# UFBmod_2V1.net
KiCad netlist of a schematic drawn in EAGLE
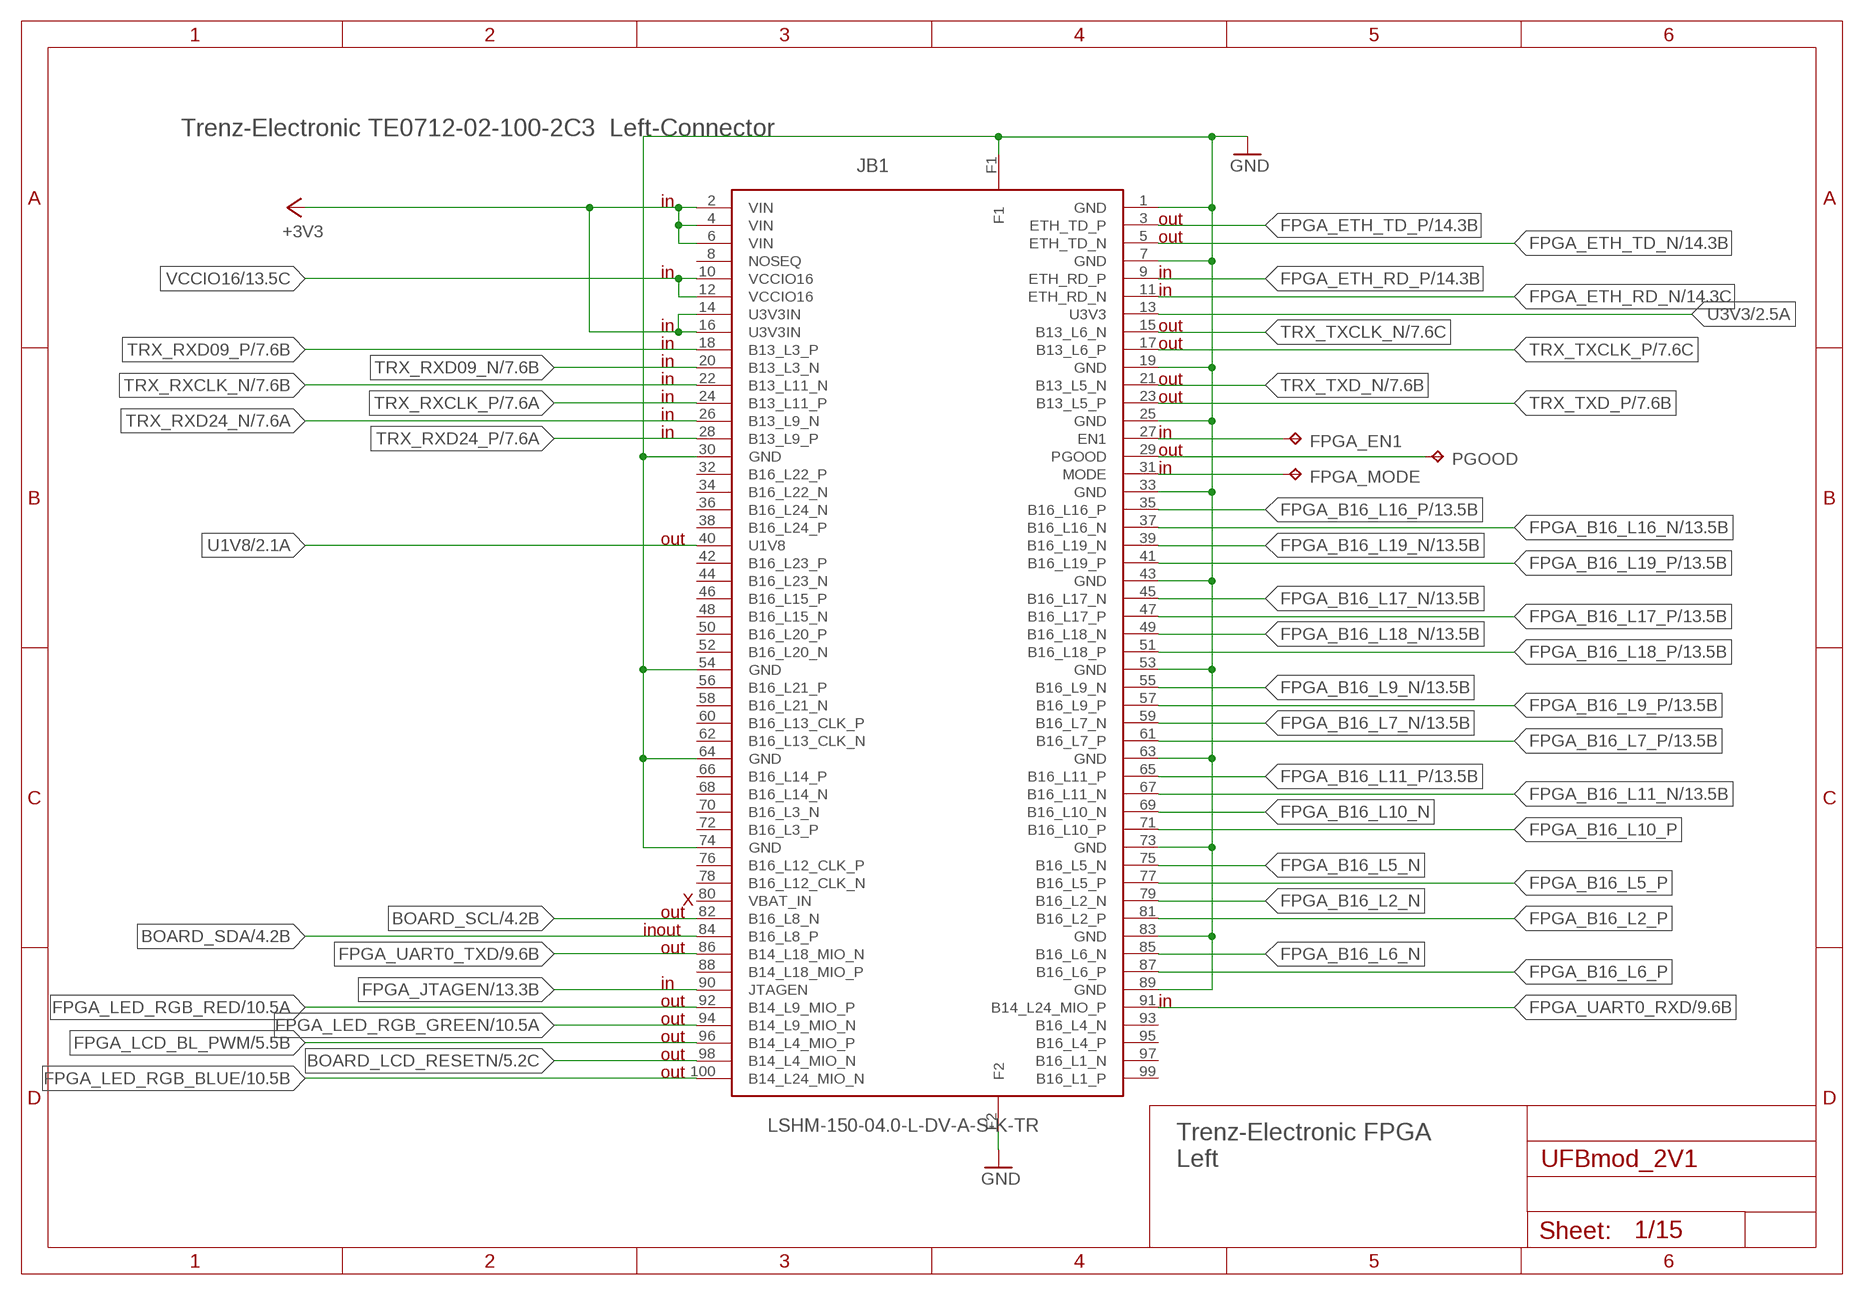
[diagram p0: schematic, sheet 1]
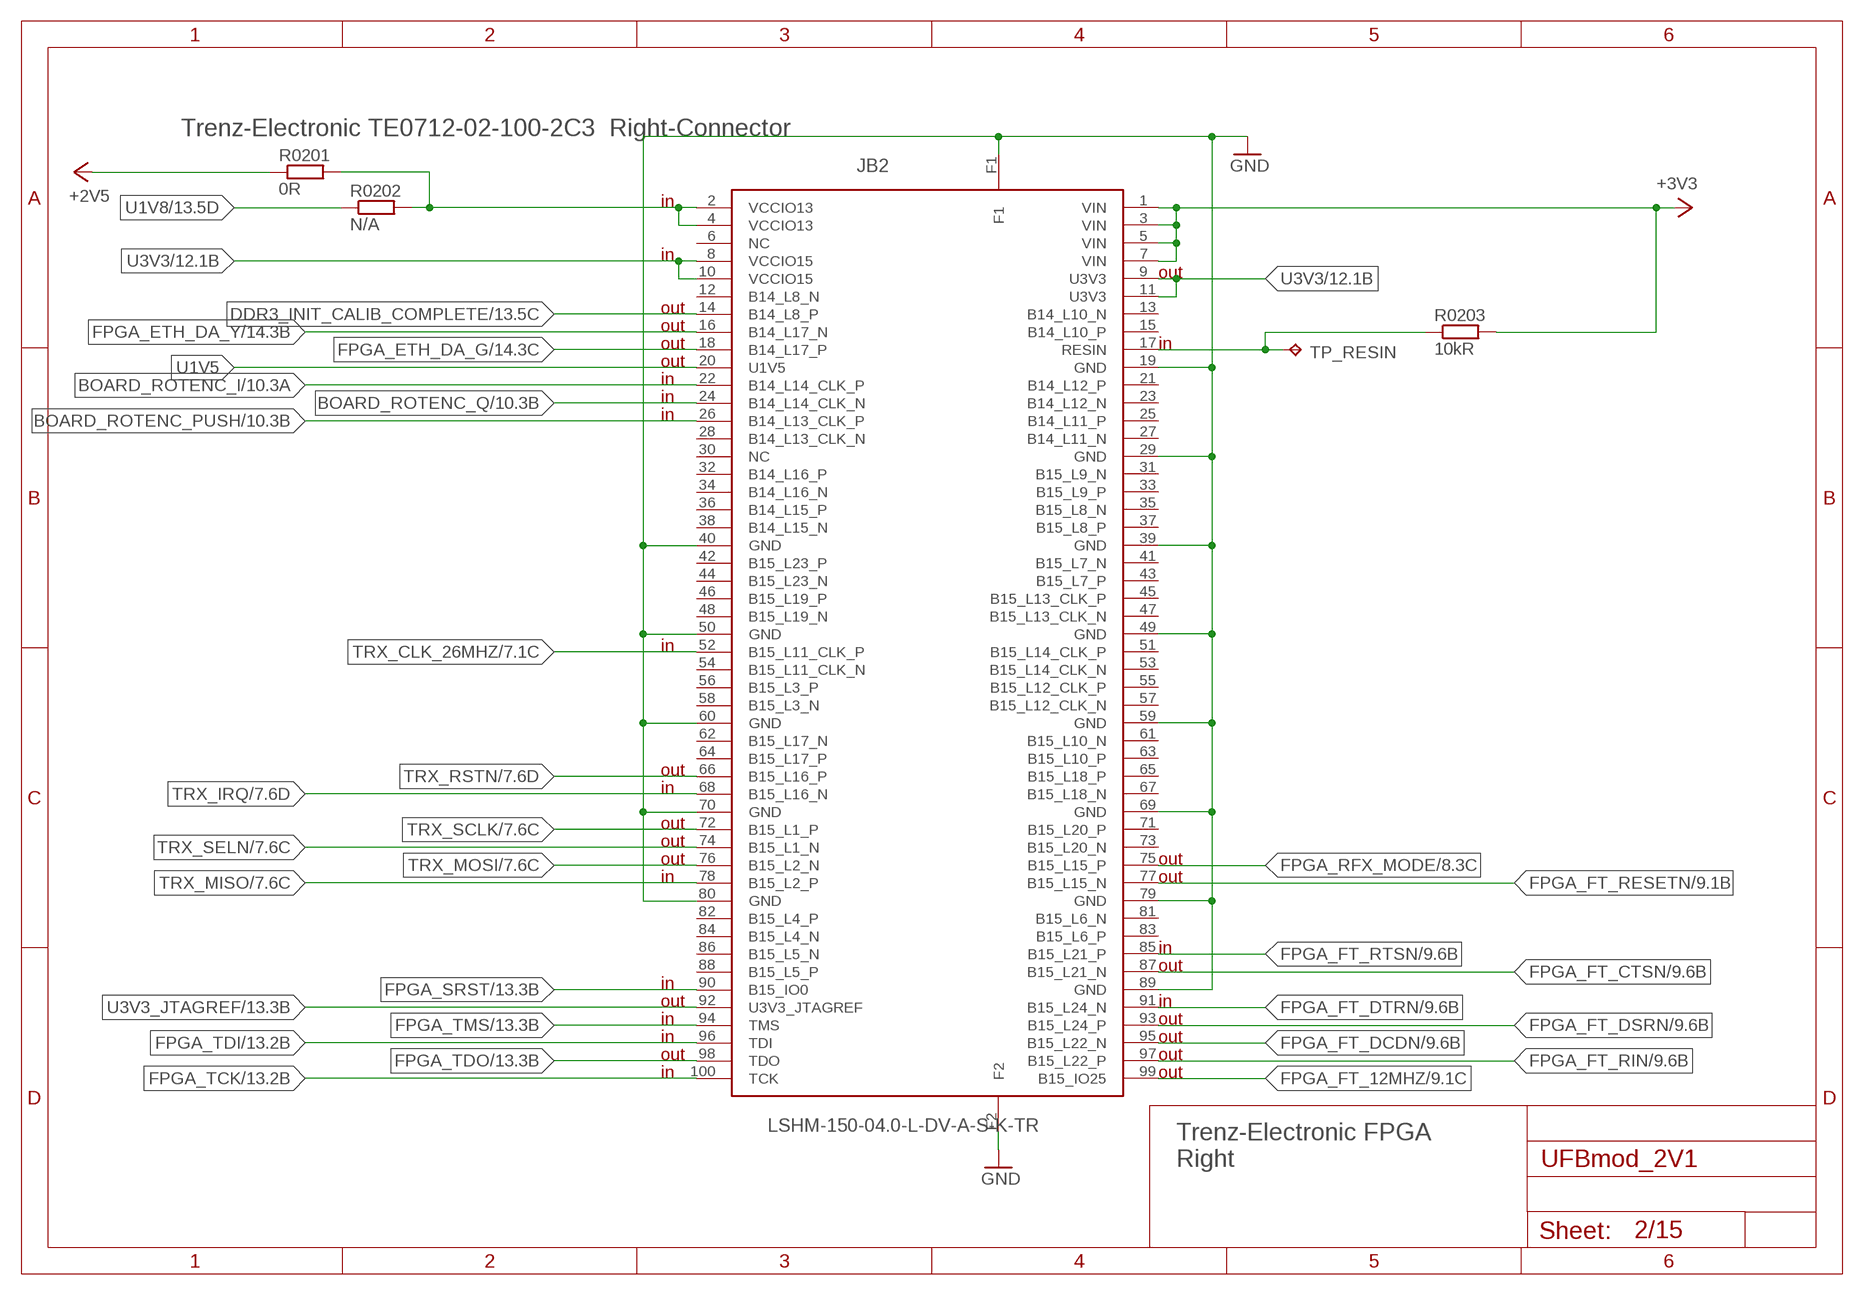
[diagram p1: schematic, sheet 2]
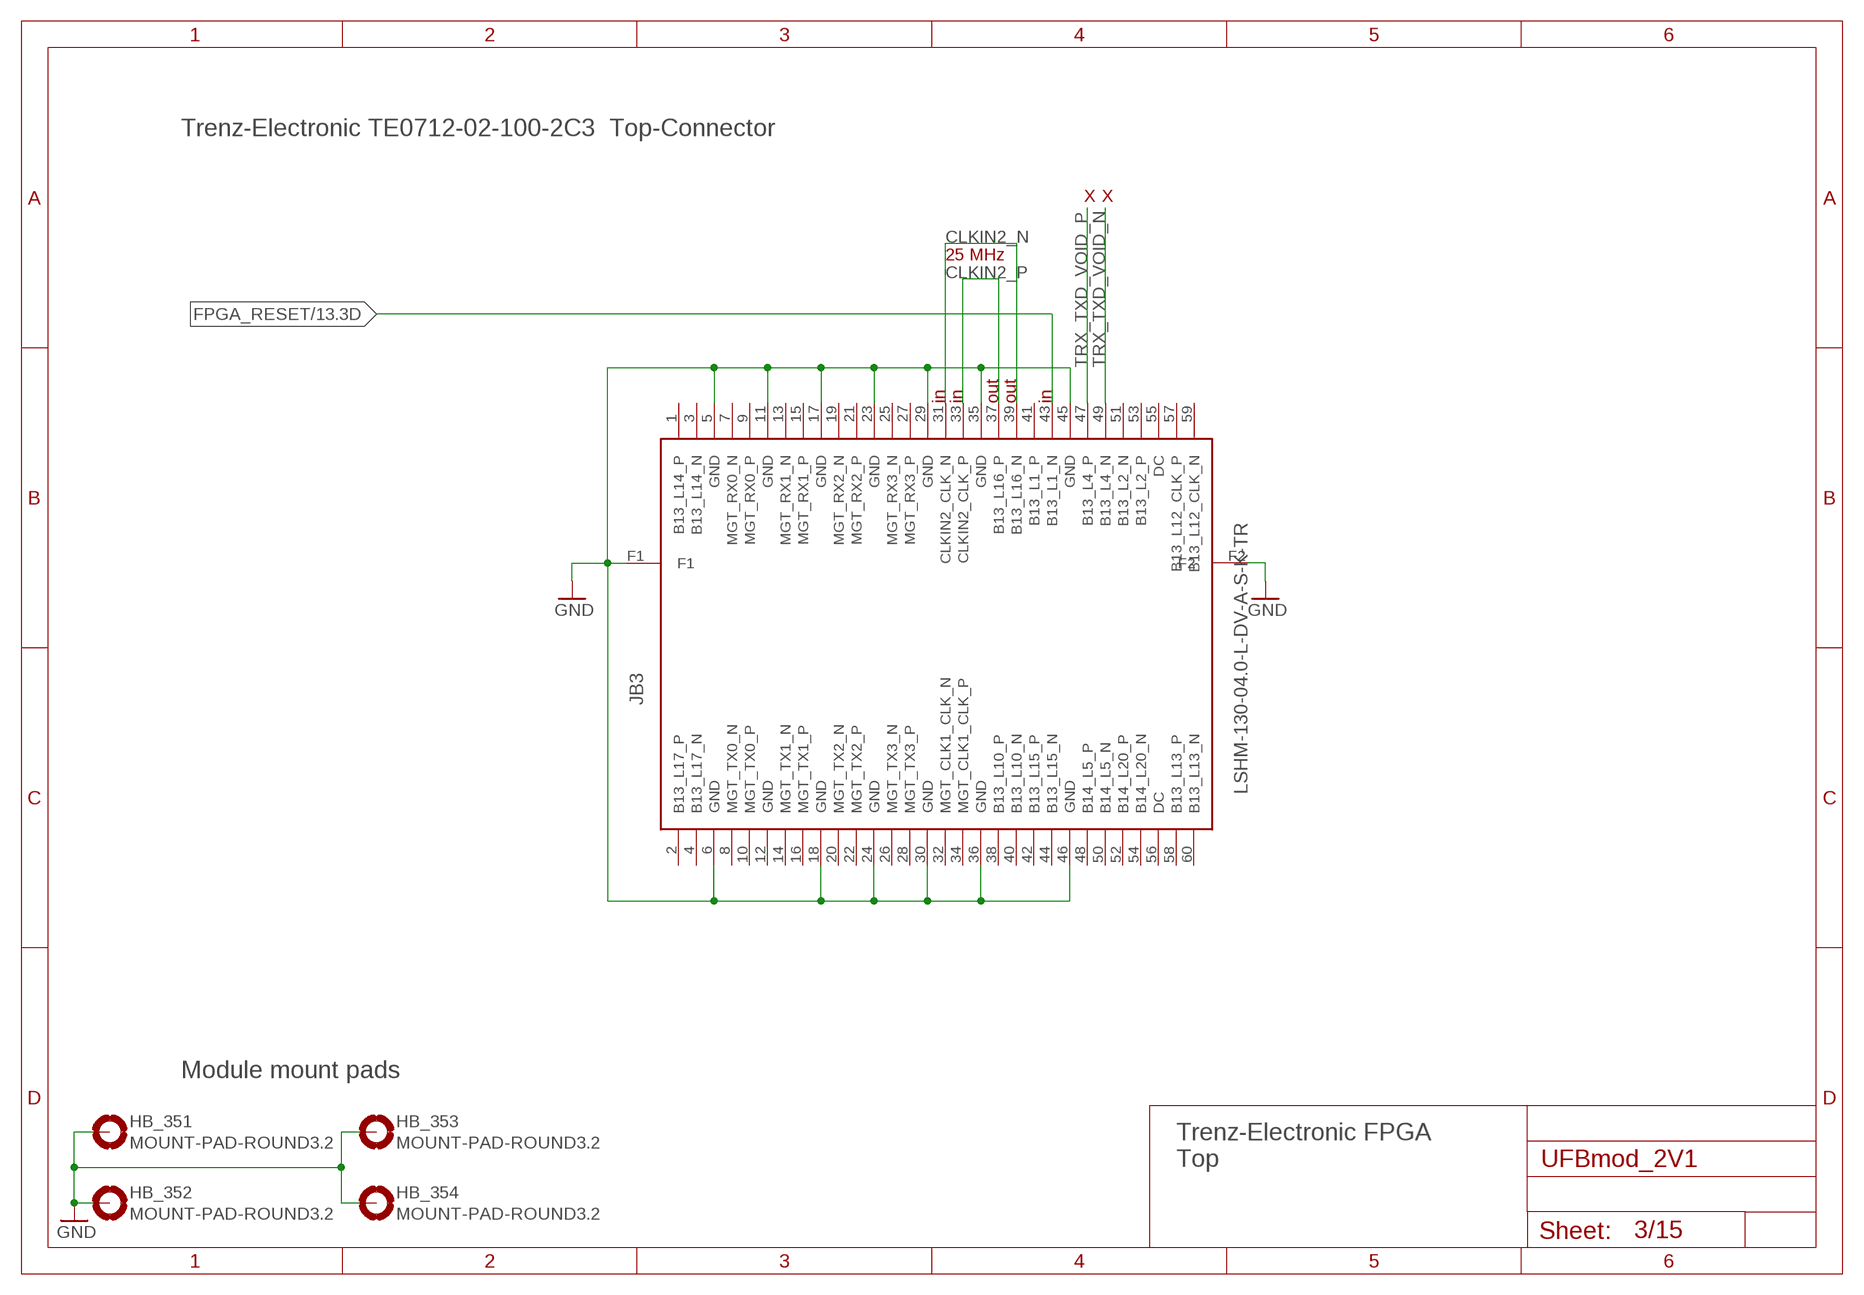
[diagram p2: schematic, sheet 3]
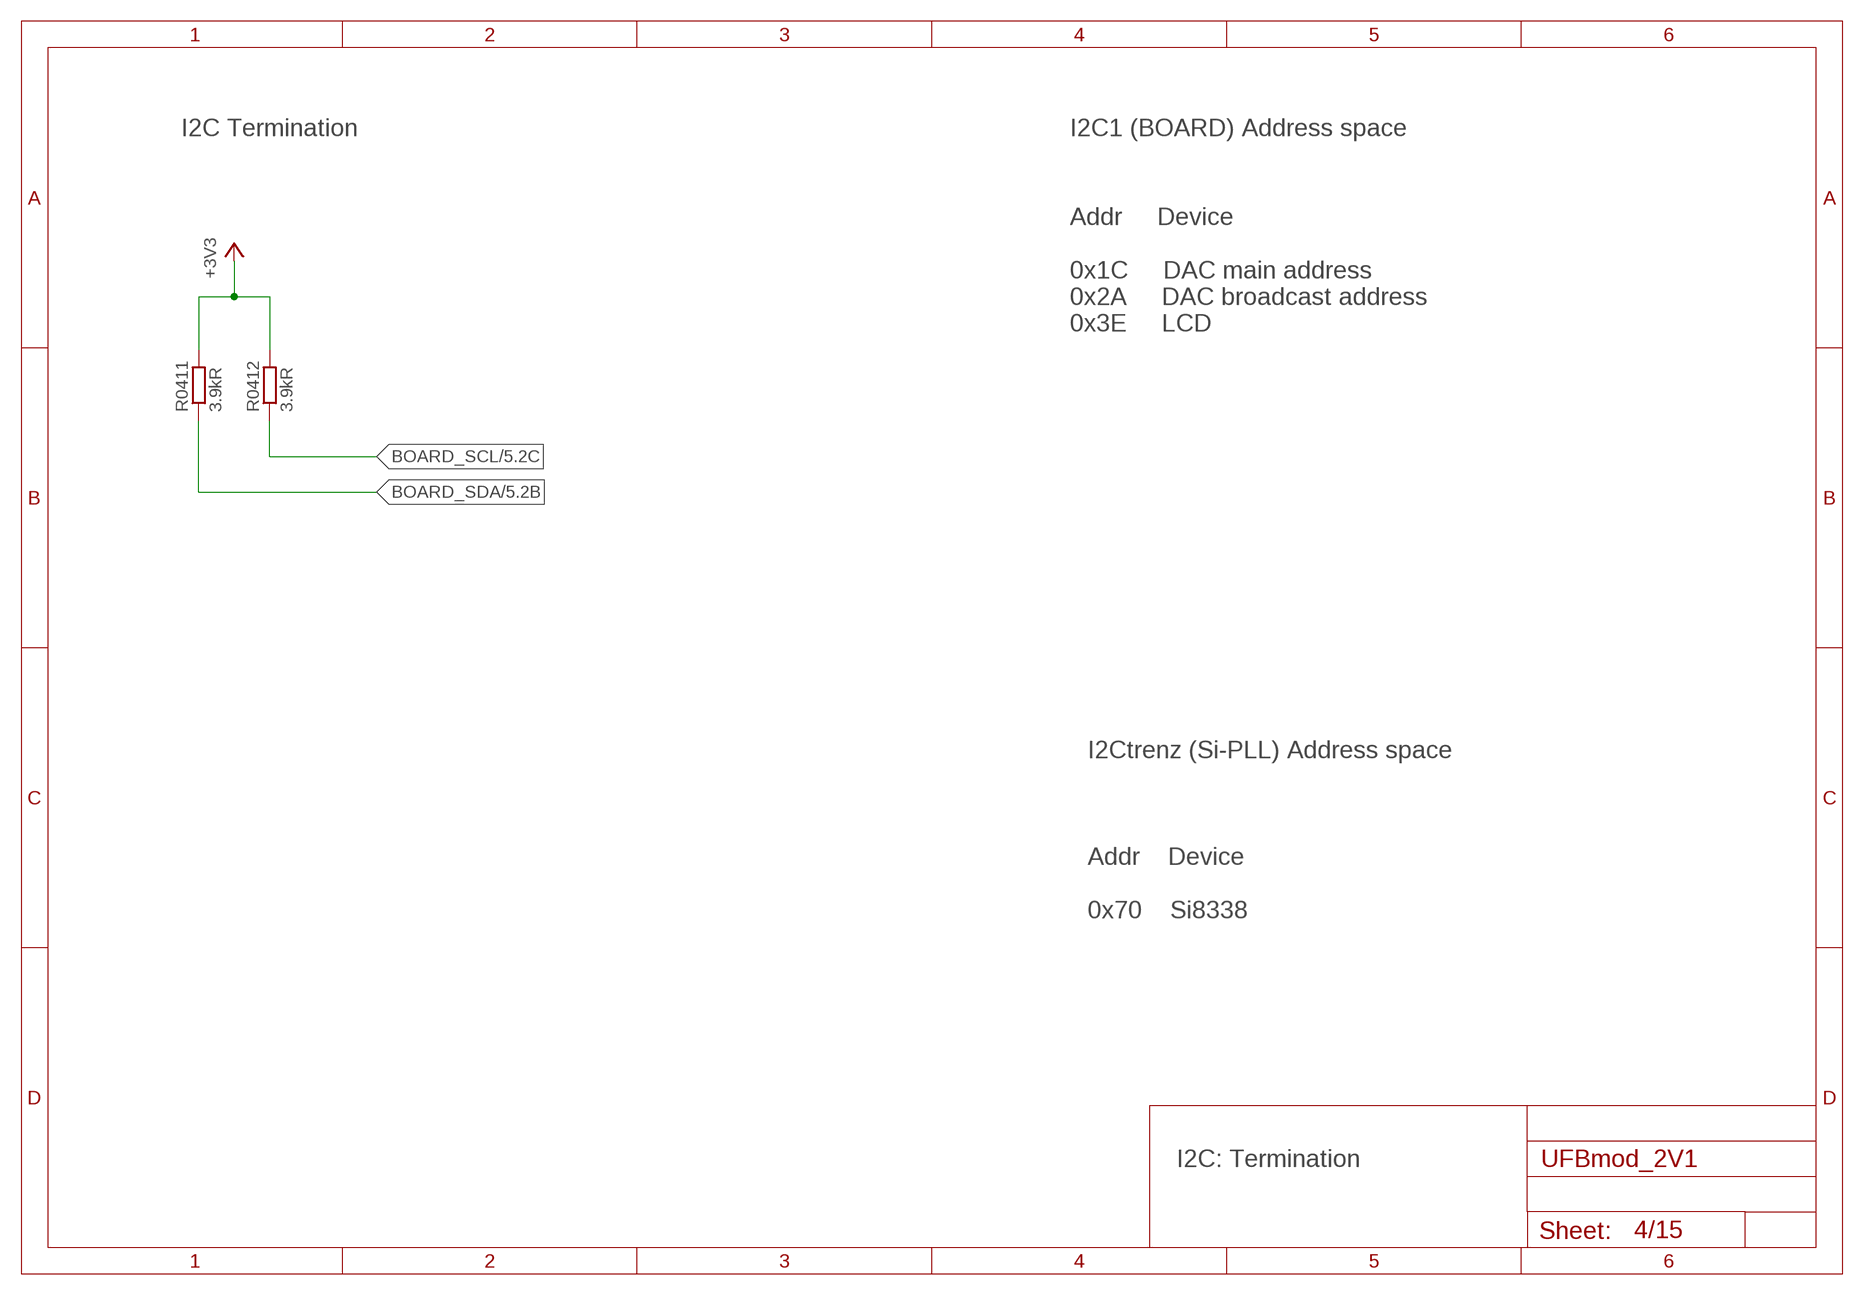
[diagram p3: schematic, sheet 4]
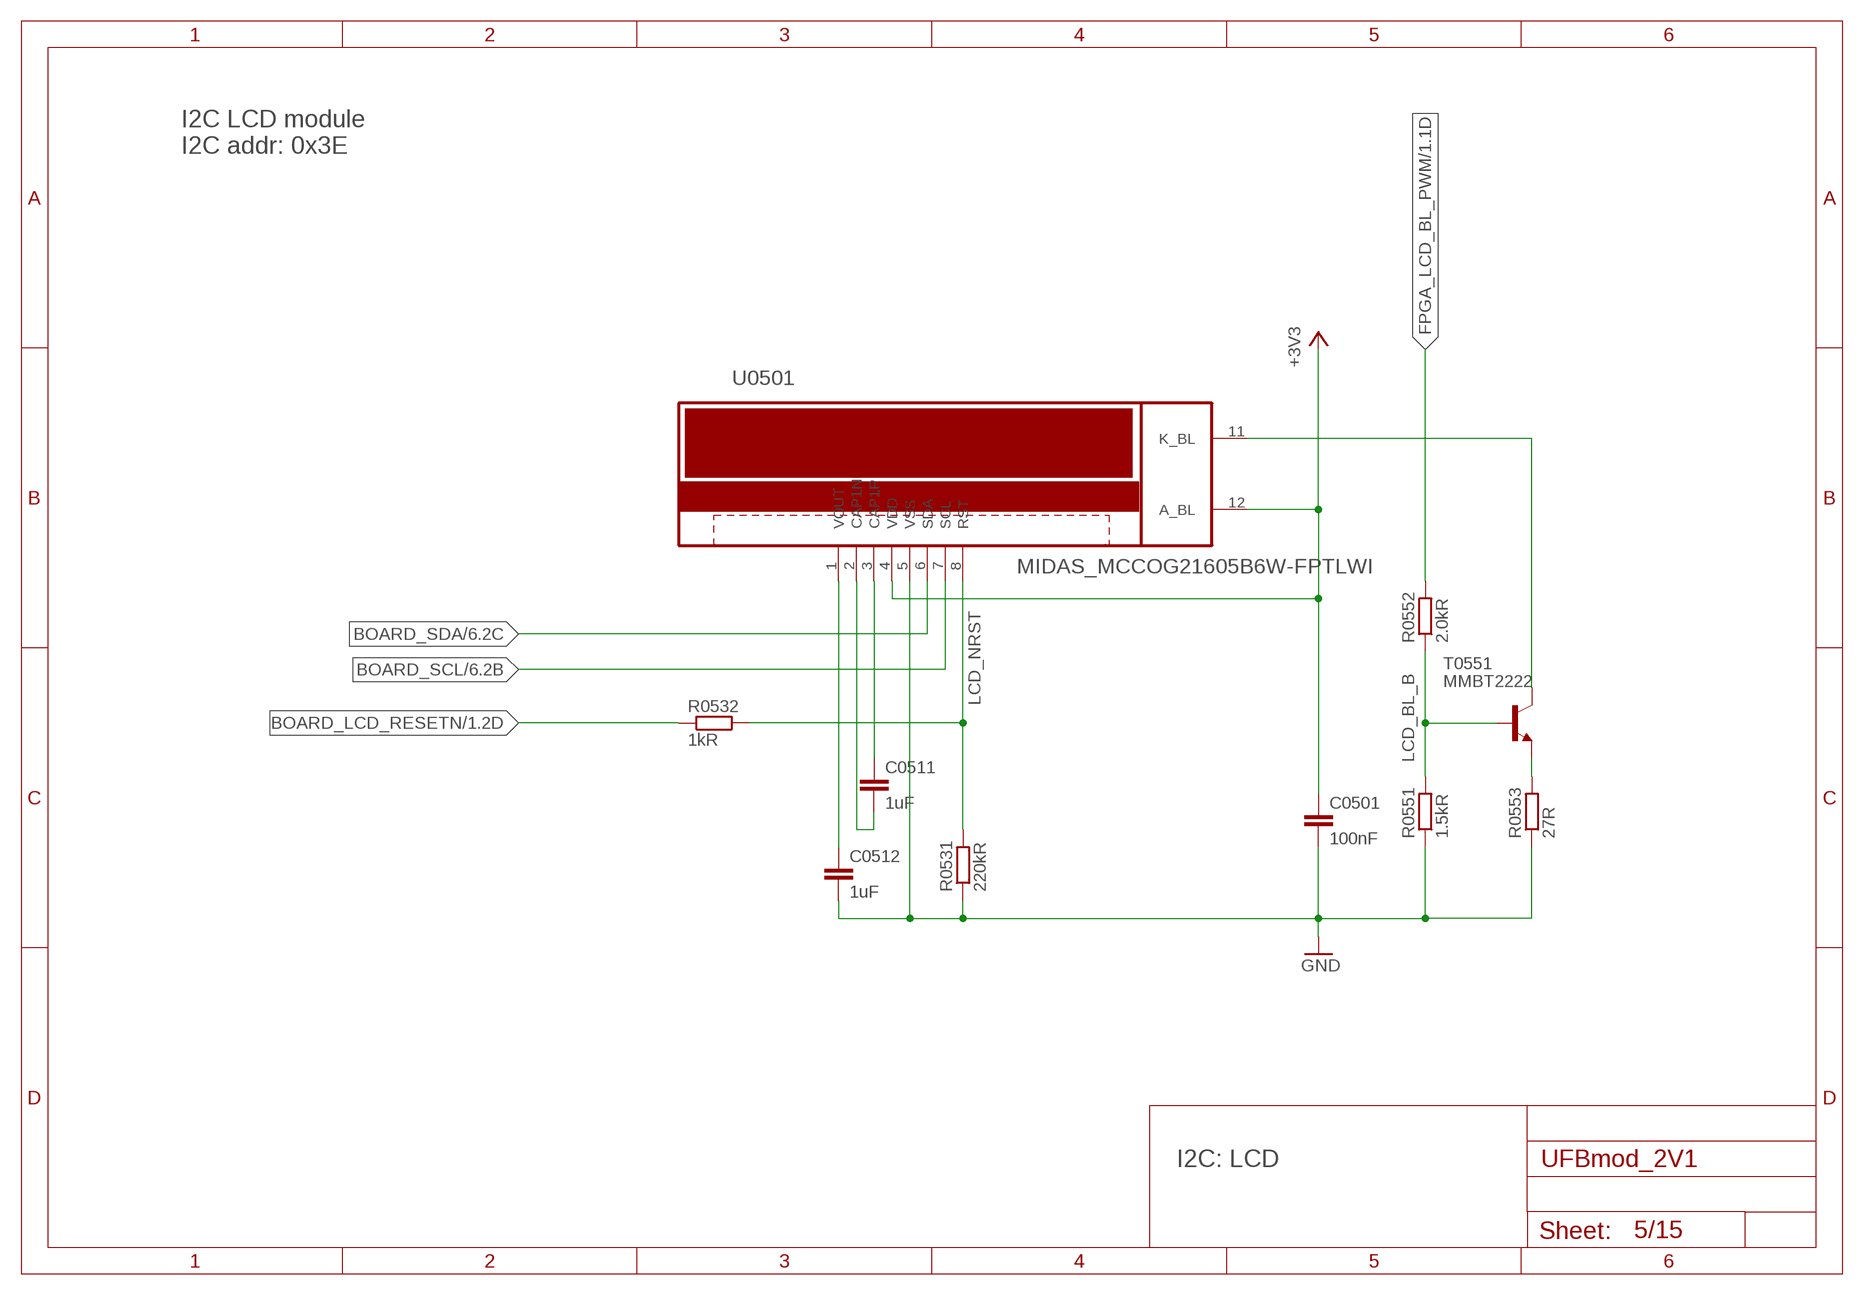
[diagram p4: schematic, sheet 5]
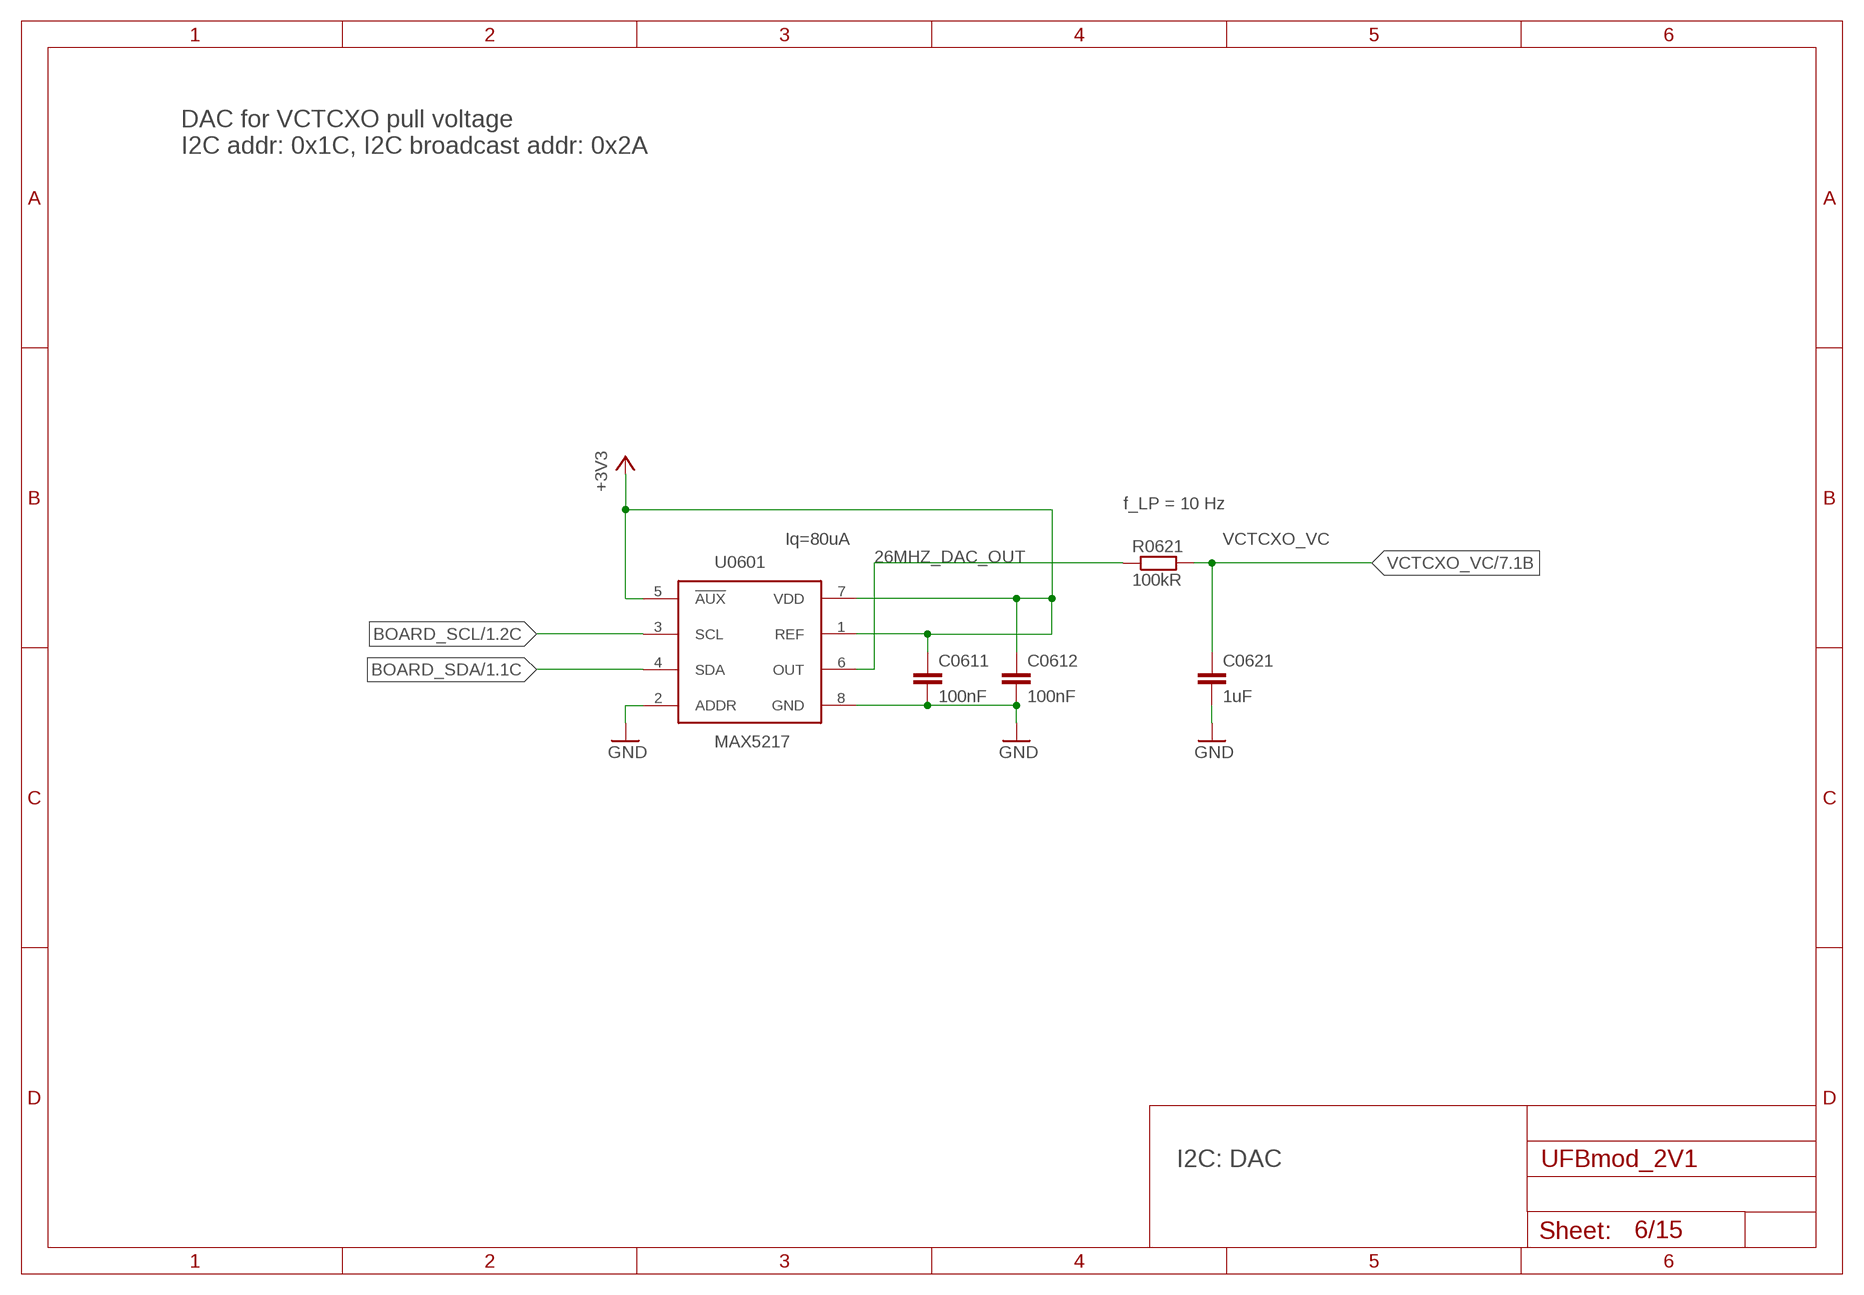
[diagram p5: schematic, sheet 6]
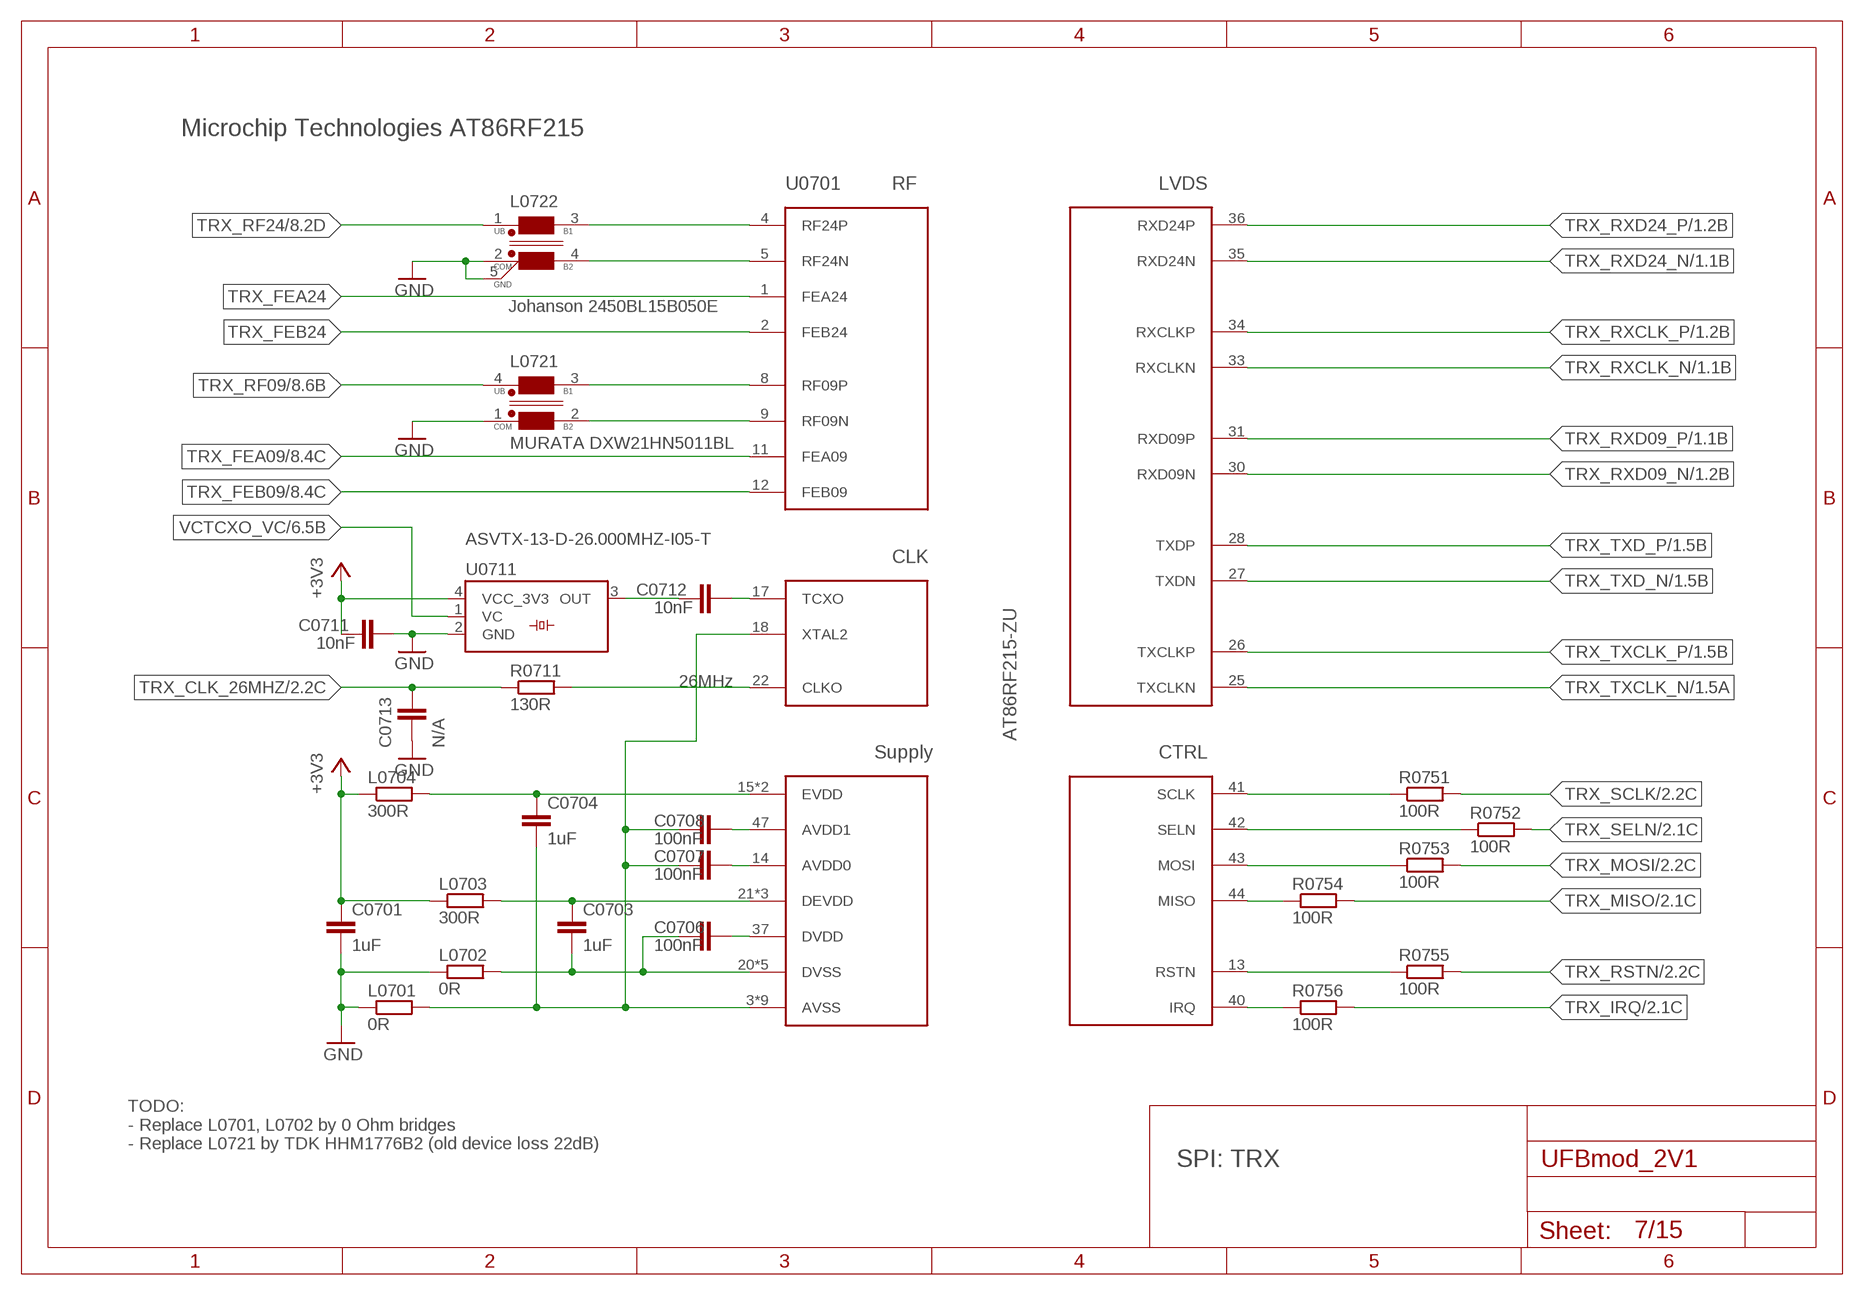
[diagram p6: schematic, sheet 7]
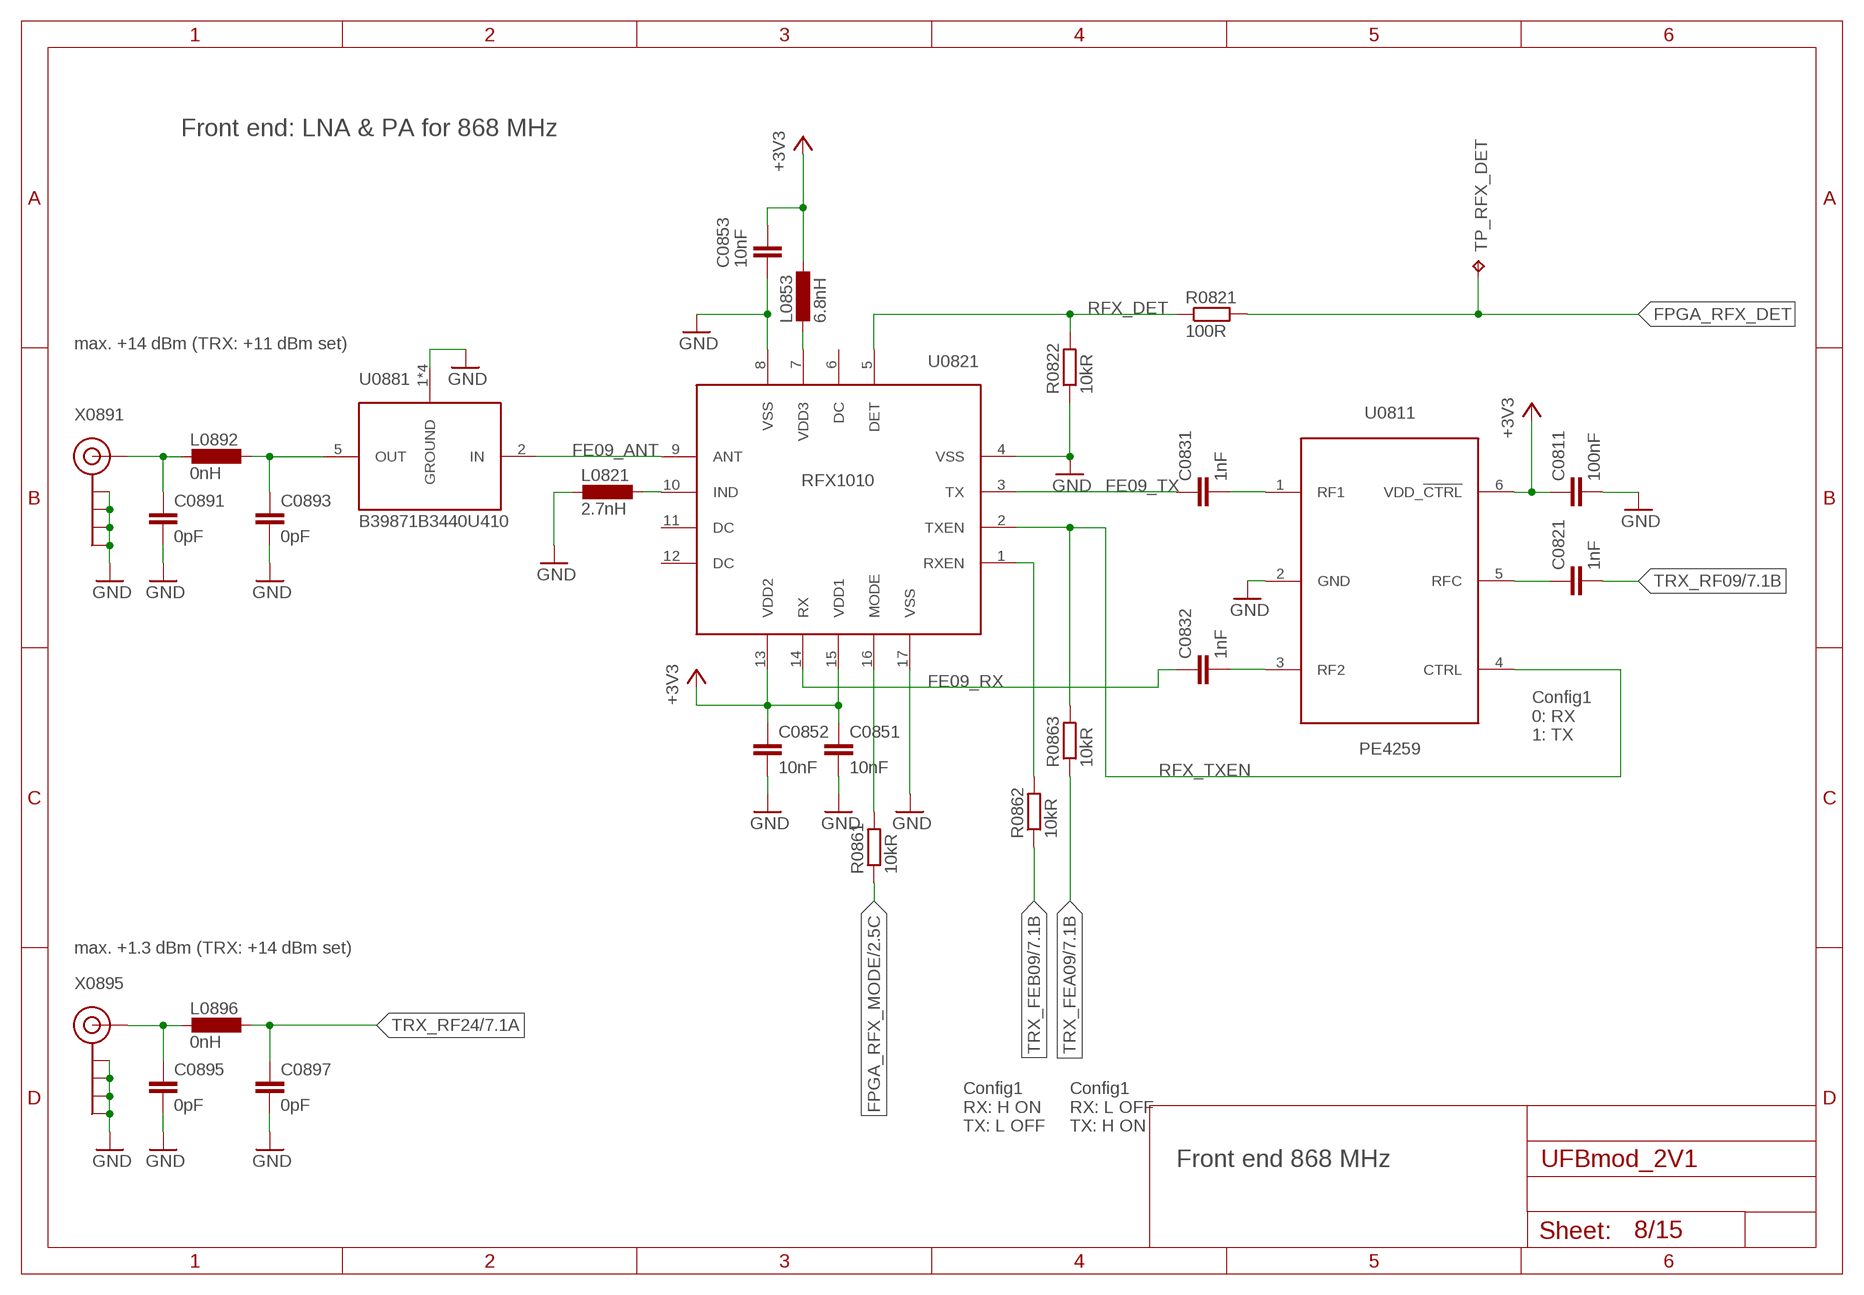
[diagram p7: schematic, sheet 8]
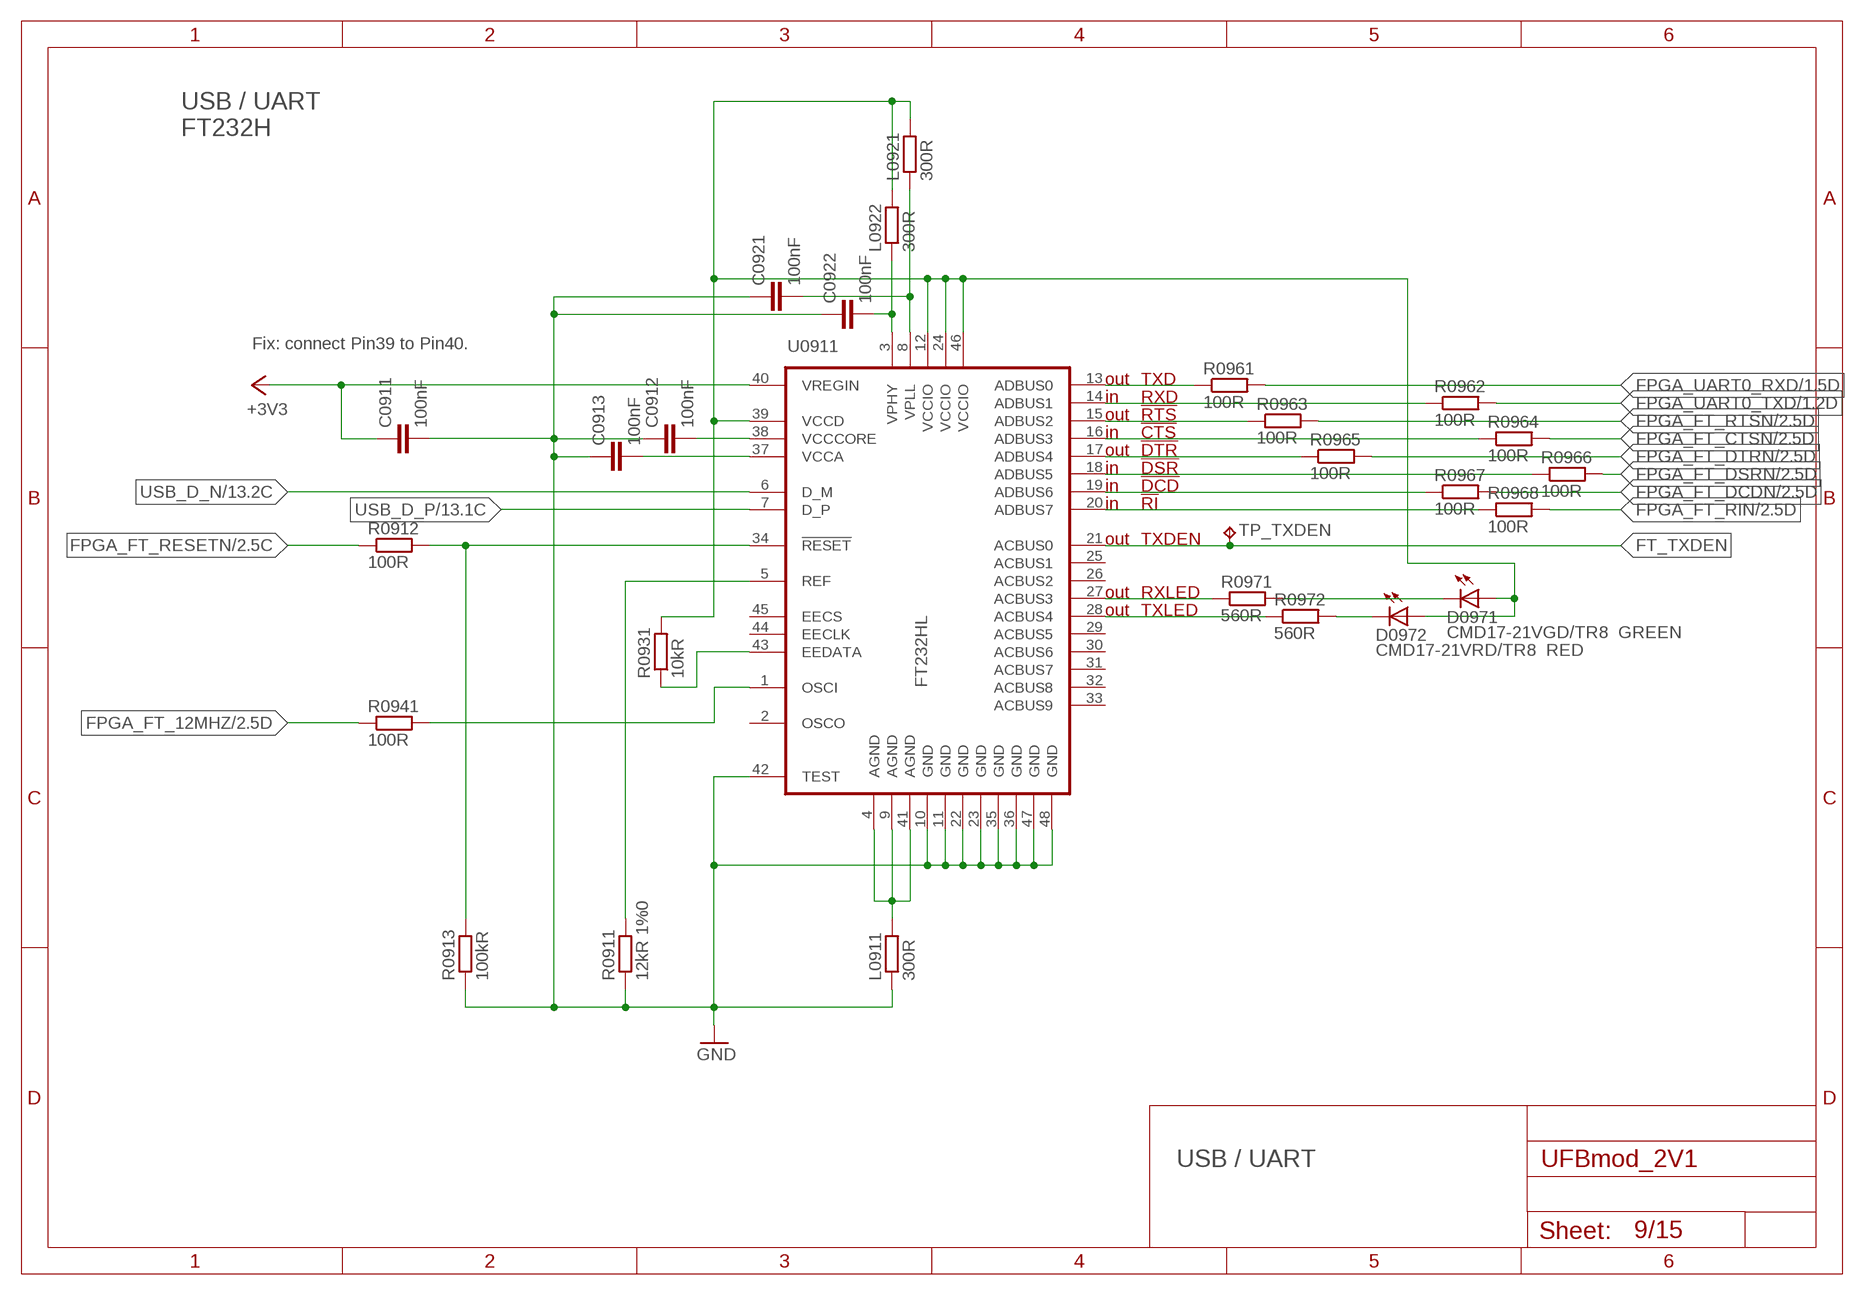
[diagram p8: schematic, sheet 9]
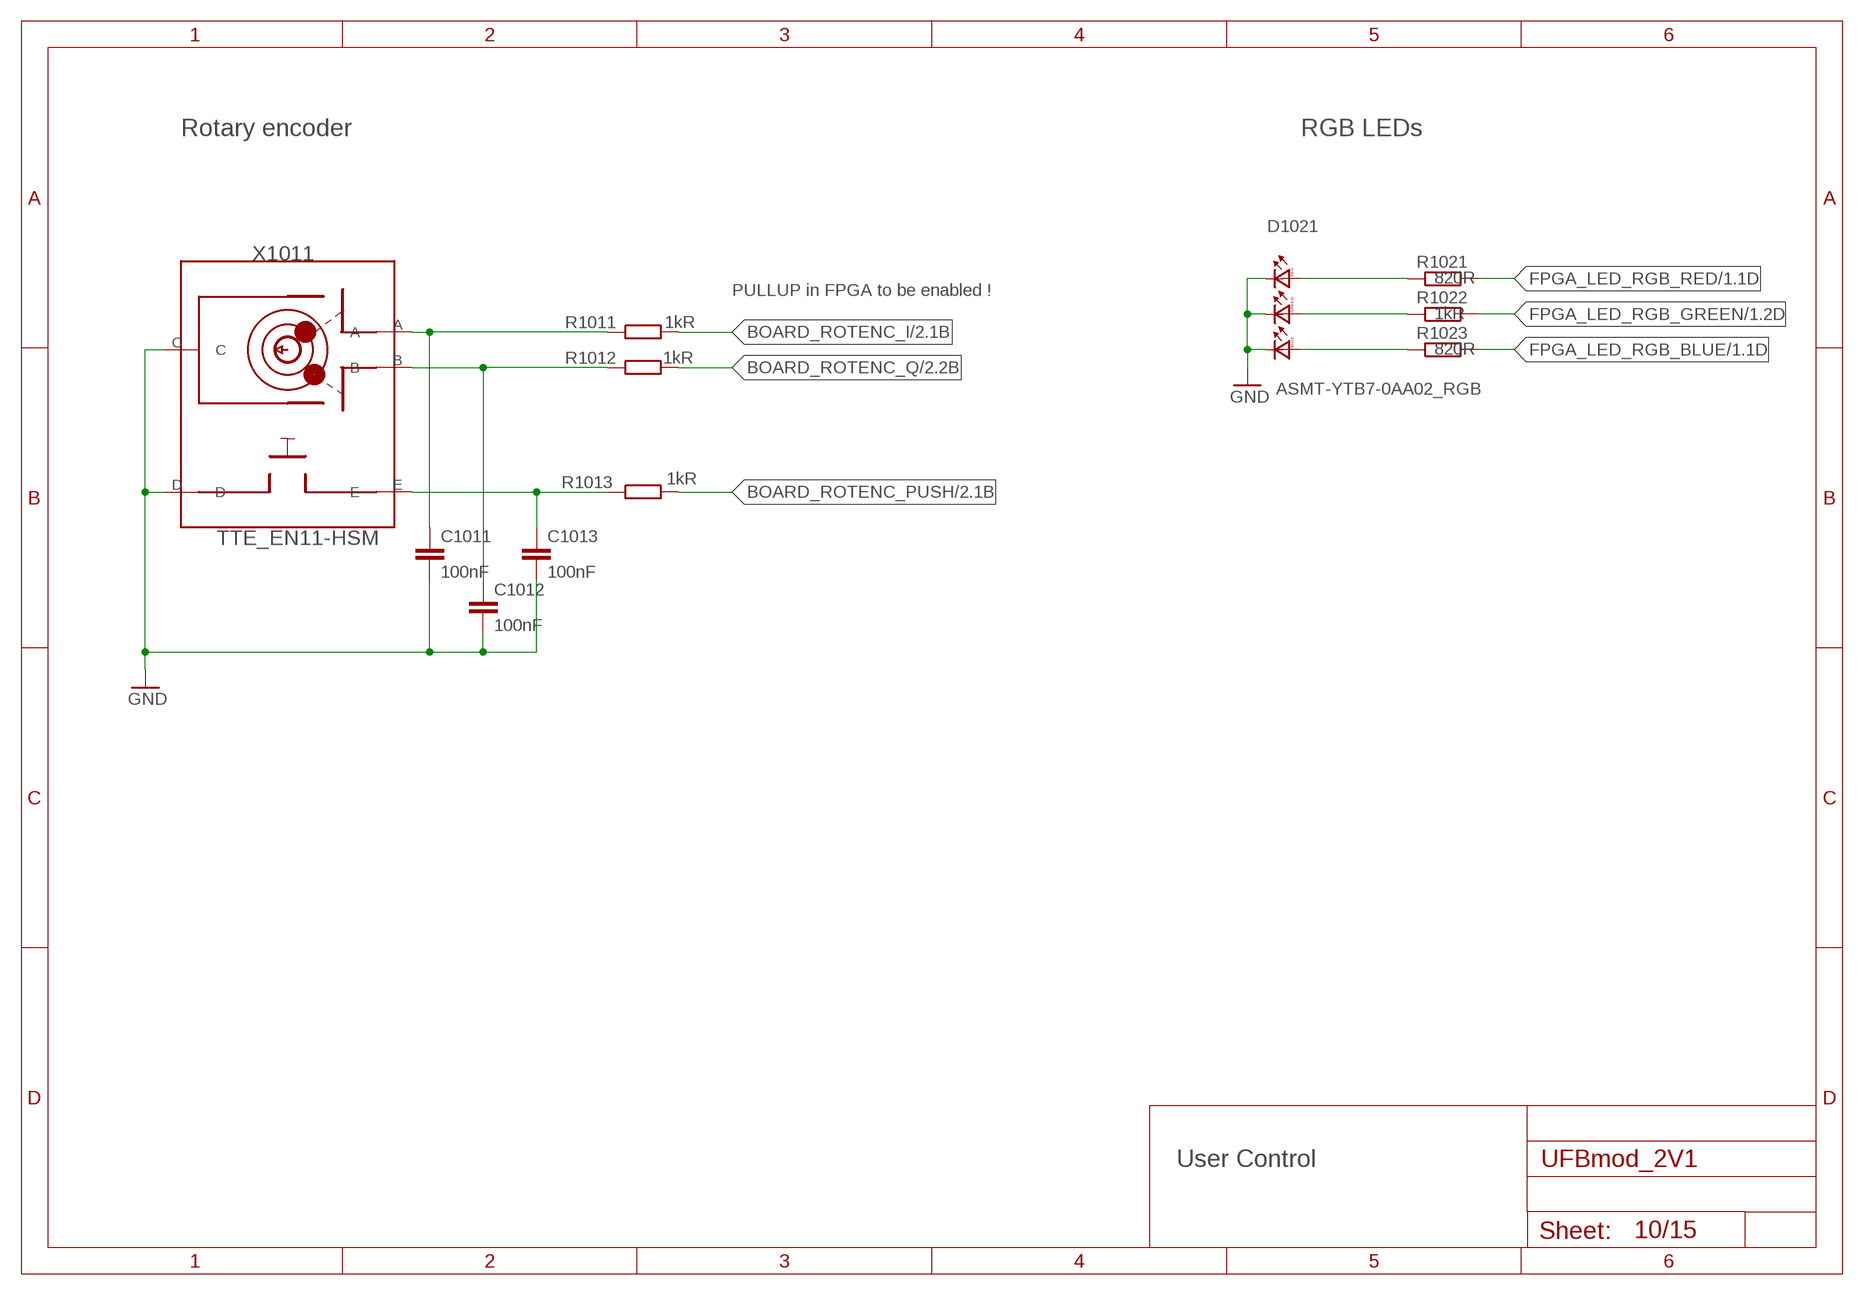
[diagram p9: schematic, sheet 10]
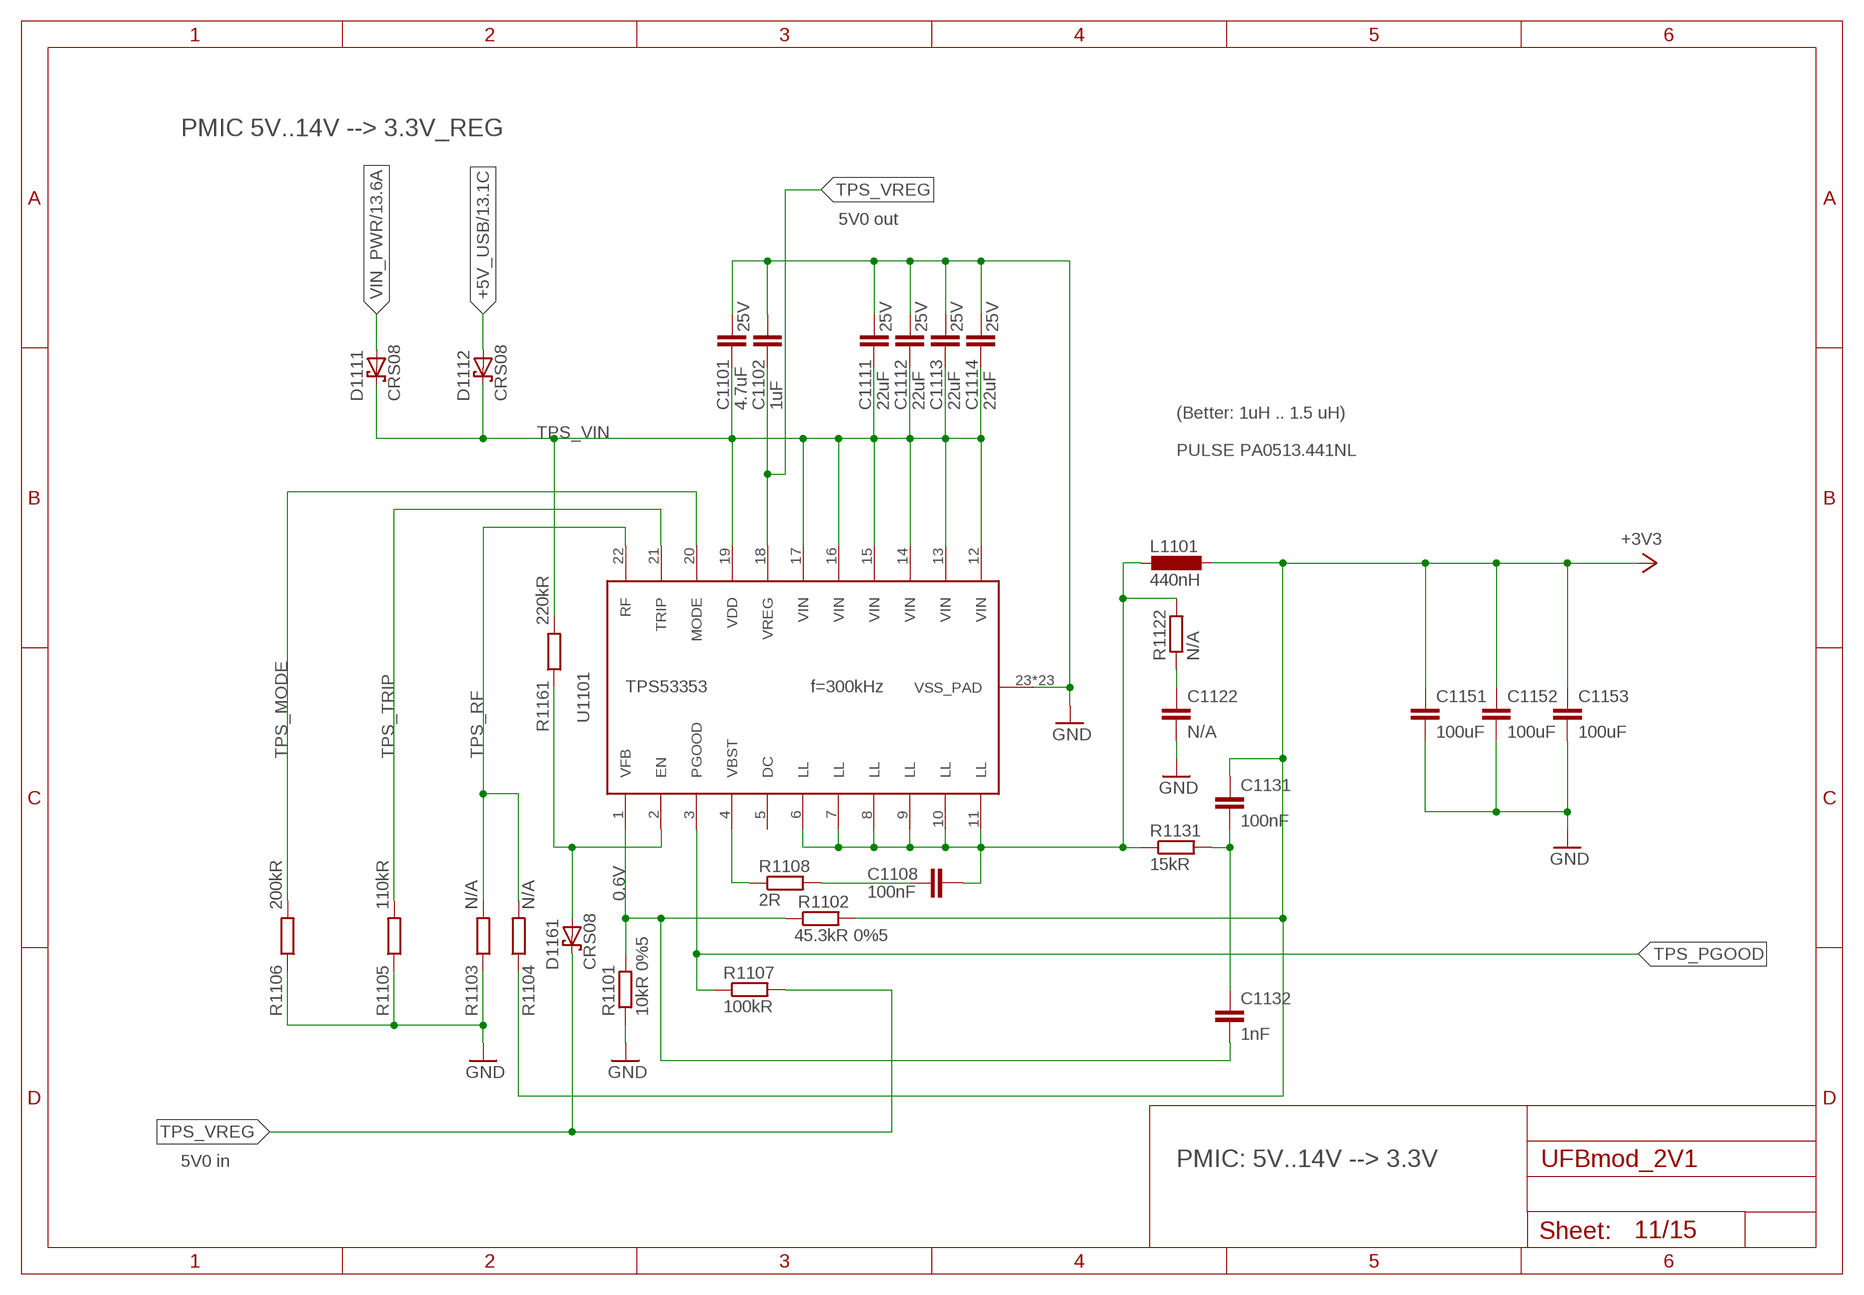
[diagram p10: schematic, sheet 11]
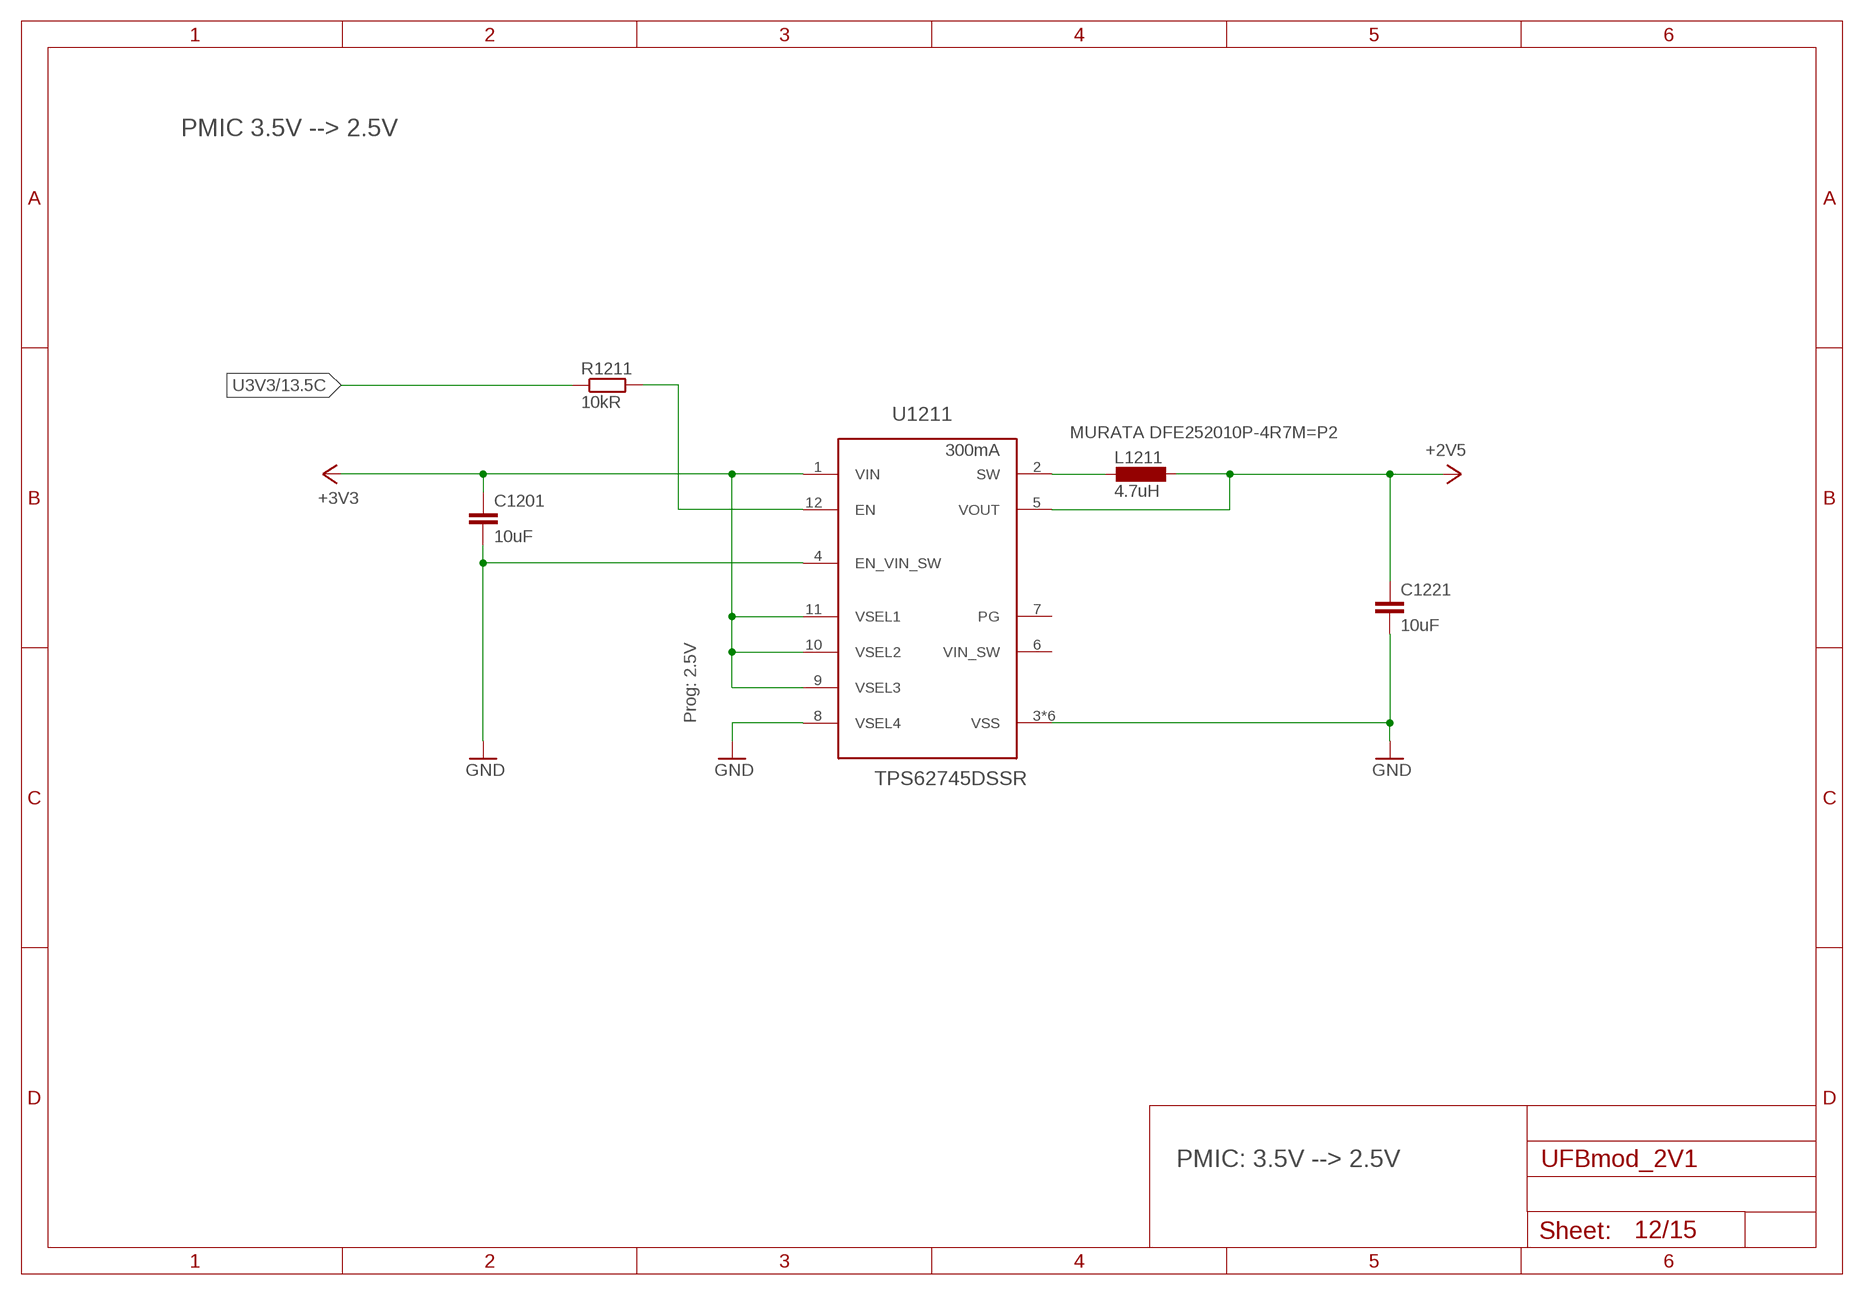
[diagram p11: schematic, sheet 12]
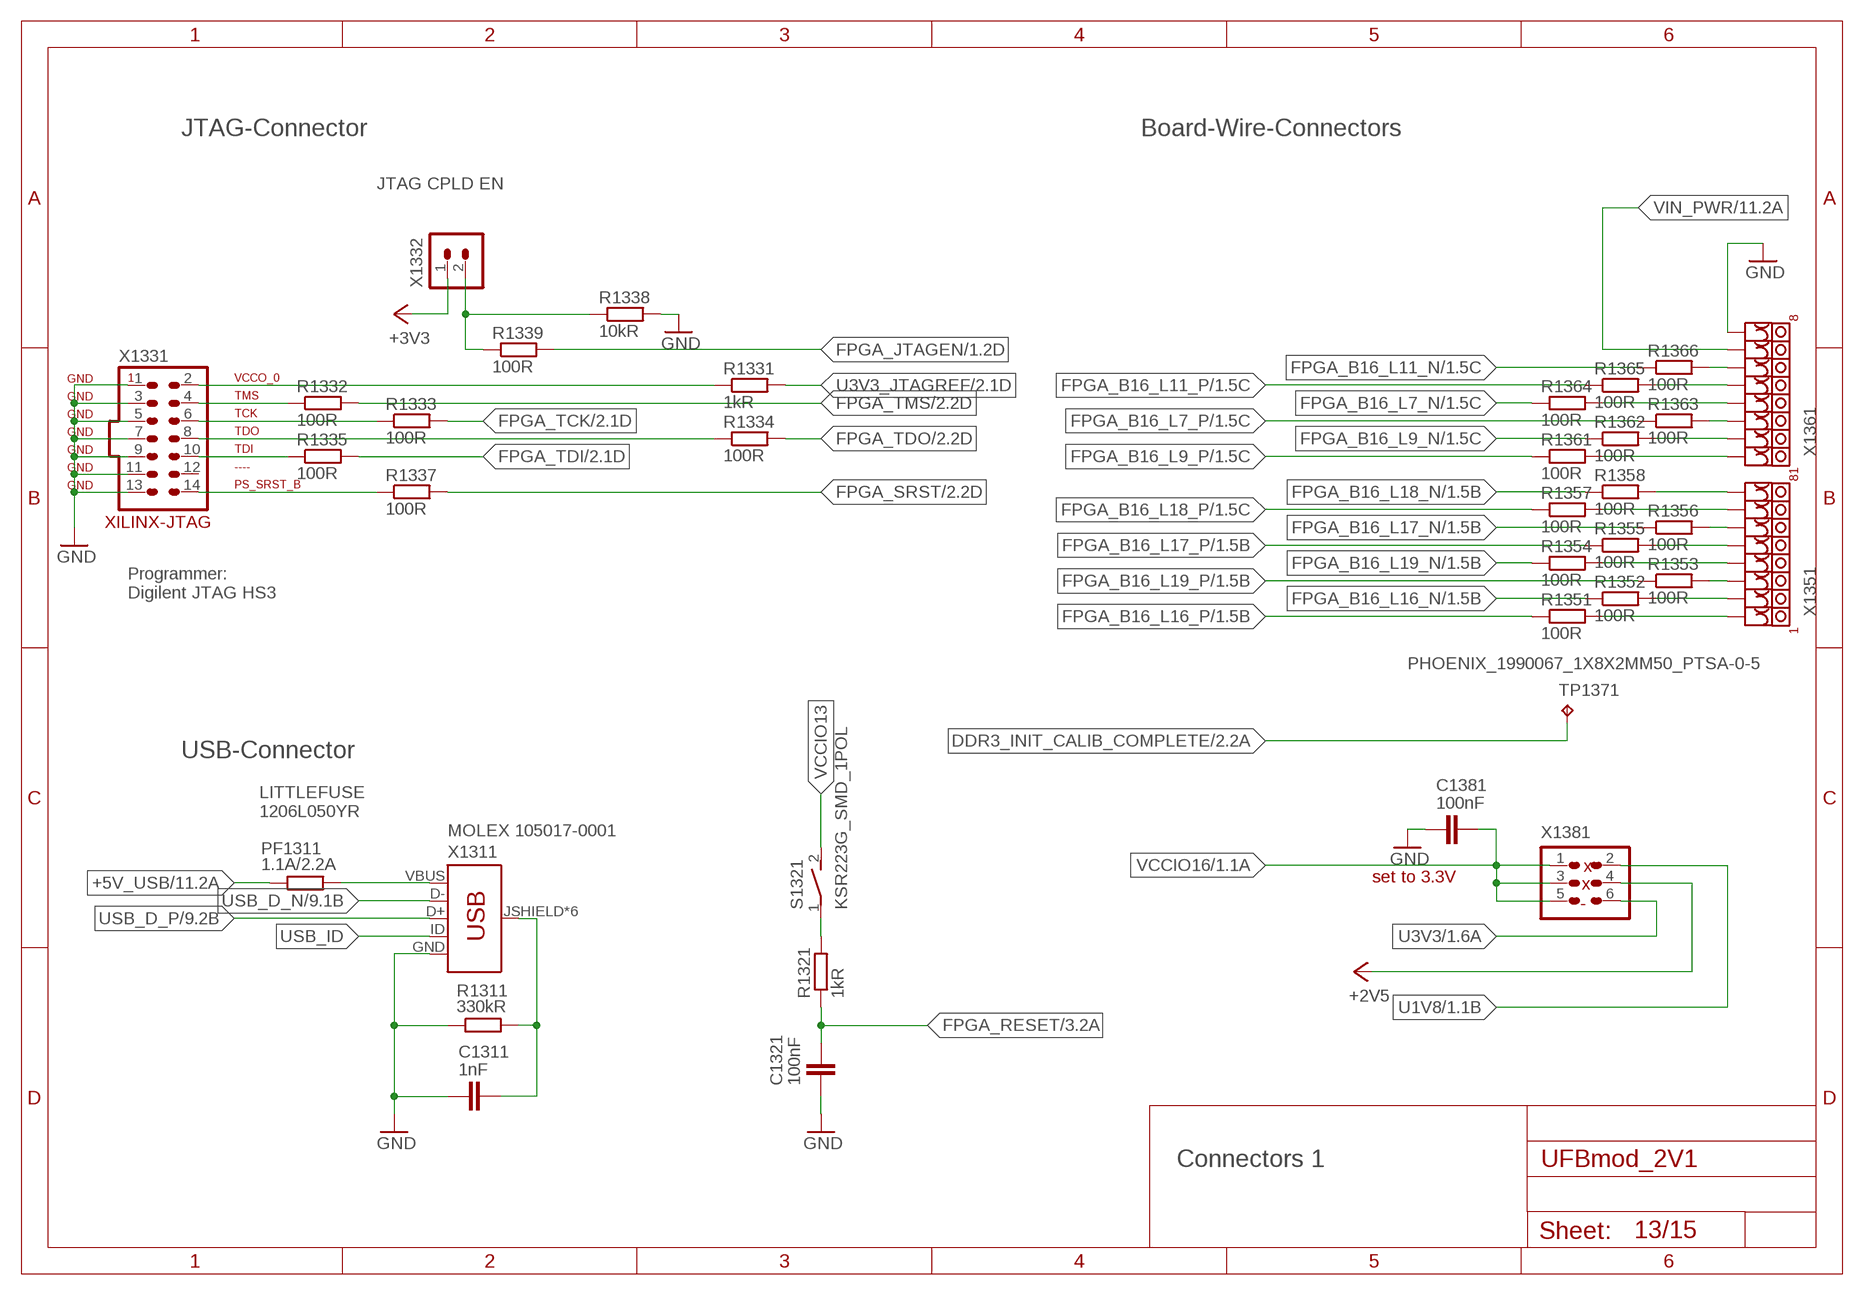
[diagram p12: schematic, sheet 13]
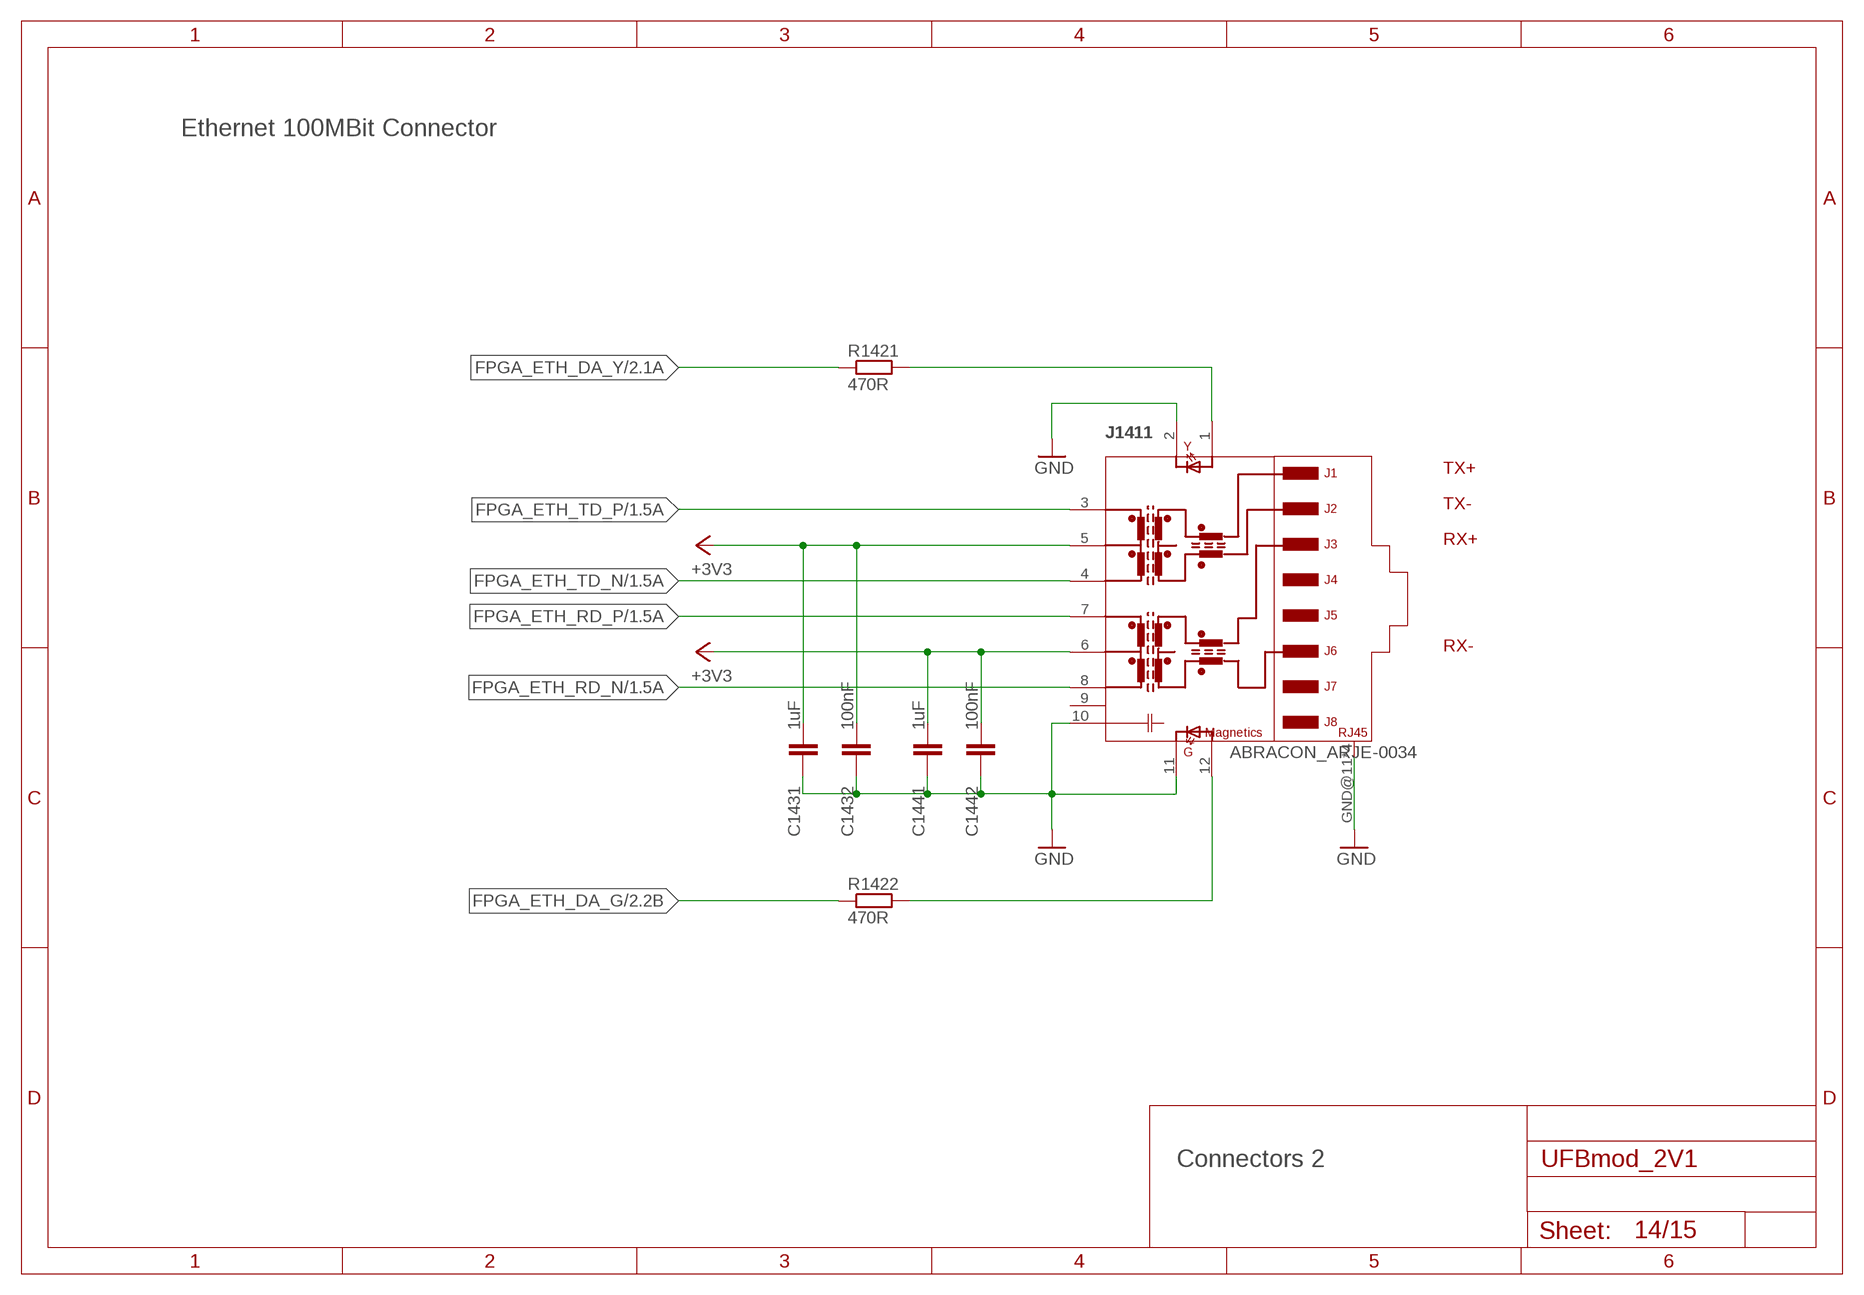
[diagram p13: schematic, sheet 14]
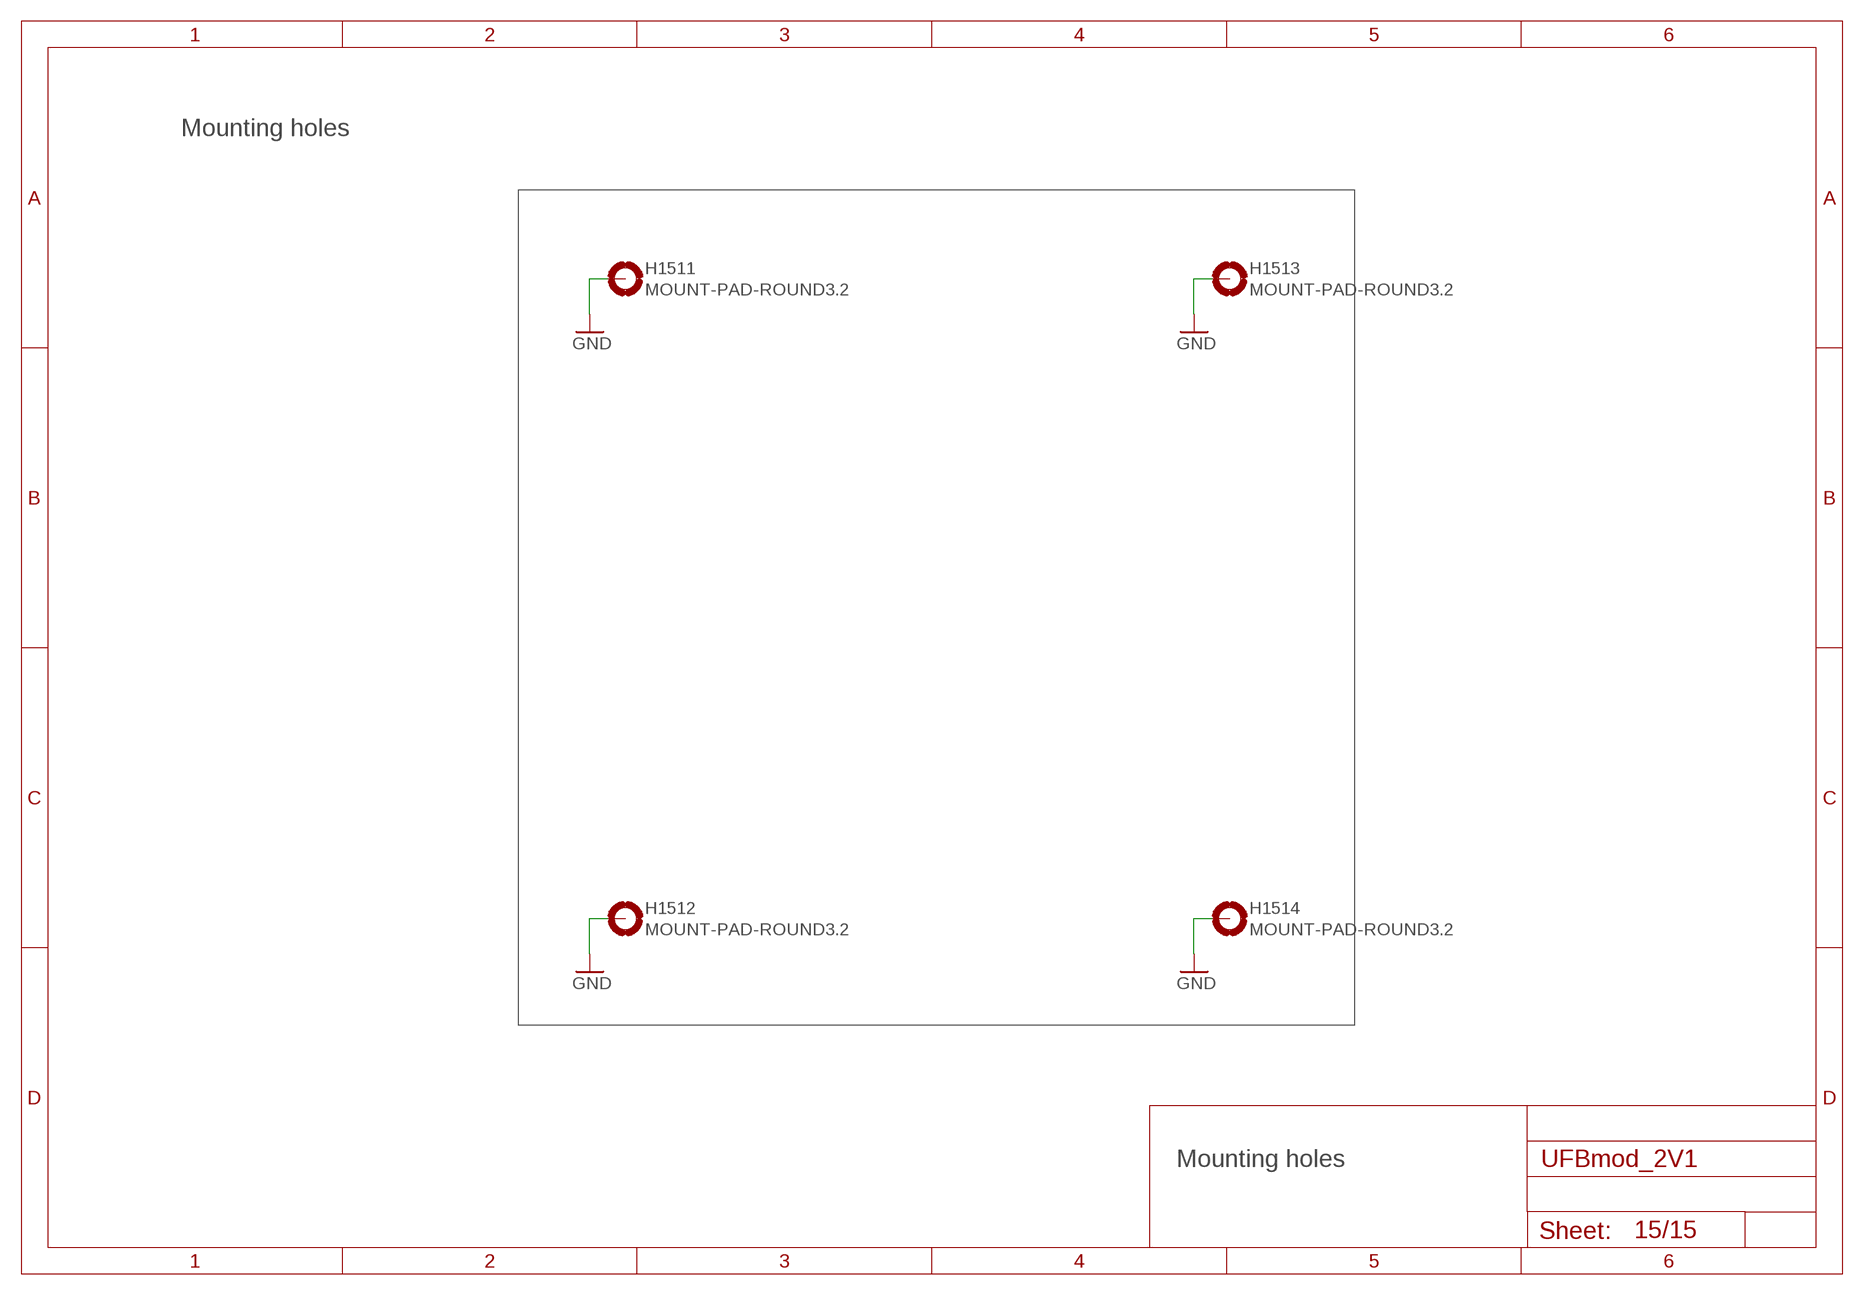
[diagram p14: schematic, sheet 15]

(export (version "E")
  (design (tool "Eeschema 10.0.6"))
  (components
    (comp (ref "JB2")
      (value "LSHM-150-04.0-L-DV-A-S-K-TR")
      (footprint "eagle-import:SAMTEC_LSHM-150-DV")
      (libsource (lib "eagle-import") (part "SAMTEC_LSHM-150-DV_JB2"))
    )
    (comp (ref "R0201")
      (value "0R")
      (footprint "eagle-import:R0402")
      (libsource (lib "eagle-import") (part "R-EU_R0402"))
    )
    (comp (ref "R0202")
      (value "N/A")
      (footprint "eagle-import:R0402")
      (libsource (lib "eagle-import") (part "R-EU_R0402"))
    )
    (comp (ref "R0203")
      (value "10kR")
      (footprint "eagle-import:R0402")
      (libsource (lib "eagle-import") (part "R-EU_R0402"))
    )
    (comp (ref "TP_RESIN")
      (value "TPB1,27")
      (footprint "eagle-import:B1,27")
      (libsource (lib "eagle-import") (part "TPB1,27"))
    )
    (comp (ref "H1511")
      (value "MOUNT-PAD-ROUND3.2")
      (footprint "eagle-import:3,2-PAD")
      (libsource (lib "eagle-import") (part "MOUNT-PAD-ROUND3.2"))
    )
    (comp (ref "H1512")
      (value "MOUNT-PAD-ROUND3.2")
      (footprint "eagle-import:3,2-PAD")
      (libsource (lib "eagle-import") (part "MOUNT-PAD-ROUND3.2"))
    )
    (comp (ref "H1513")
      (value "MOUNT-PAD-ROUND3.2")
      (footprint "eagle-import:3,2-PAD")
      (libsource (lib "eagle-import") (part "MOUNT-PAD-ROUND3.2"))
    )
    (comp (ref "H1514")
      (value "MOUNT-PAD-ROUND3.2")
      (footprint "eagle-import:3,2-PAD")
      (libsource (lib "eagle-import") (part "MOUNT-PAD-ROUND3.2"))
    )
    (comp (ref "R0411")
      (value "3.9kR")
      (footprint "eagle-import:R0402")
      (libsource (lib "eagle-import") (part "R-EU_R0402"))
    )
    (comp (ref "R0412")
      (value "3.9kR")
      (footprint "eagle-import:R0402")
      (libsource (lib "eagle-import") (part "R-EU_R0402"))
    )
    (comp (ref "C1311")
      (value "1nF")
      (footprint "eagle-import:C0402")
      (libsource (lib "eagle-import") (part "C-EUC0402"))
    )
    (comp (ref "C1321")
      (value "100nF")
      (footprint "eagle-import:C0402")
      (libsource (lib "eagle-import") (part "C-EUC0402"))
    )
    (comp (ref "C1381")
      (value "100nF")
      (footprint "eagle-import:C0402")
      (libsource (lib "eagle-import") (part "C-EUC0402"))
    )
    (comp (ref "PF1311")
      (value "1.1A/2.2A")
      (footprint "eagle-import:M1206")
      (libsource (lib "eagle-import") (part "rcl_R-EU_M1206"))
    )
    (comp (ref "R1311")
      (value "330kR")
      (footprint "eagle-import:R0402")
      (libsource (lib "eagle-import") (part "R-EU_R0402"))
    )
    (comp (ref "R1321")
      (value "1kR")
      (footprint "eagle-import:R0402")
      (libsource (lib "eagle-import") (part "R-EU_R0402"))
    )
    (comp (ref "R1331")
      (value "1kR")
      (footprint "eagle-import:R0402")
      (libsource (lib "eagle-import") (part "R-EU_R0402"))
    )
    (comp (ref "R1332")
      (value "100R")
      (footprint "eagle-import:R0402")
      (libsource (lib "eagle-import") (part "R-EU_R0402"))
    )
    (comp (ref "R1333")
      (value "100R")
      (footprint "eagle-import:R0402")
      (libsource (lib "eagle-import") (part "R-EU_R0402"))
    )
    (comp (ref "R1334")
      (value "100R")
      (footprint "eagle-import:R0402")
      (libsource (lib "eagle-import") (part "R-EU_R0402"))
    )
    (comp (ref "R1335")
      (value "100R")
      (footprint "eagle-import:R0402")
      (libsource (lib "eagle-import") (part "R-EU_R0402"))
    )
    (comp (ref "R1337")
      (value "100R")
      (footprint "eagle-import:R0402")
      (libsource (lib "eagle-import") (part "R-EU_R0402"))
    )
    (comp (ref "R1338")
      (value "10kR")
      (footprint "eagle-import:R0402")
      (libsource (lib "eagle-import") (part "R-EU_R0402"))
    )
    (comp (ref "R1339")
      (value "100R")
      (footprint "eagle-import:R0402")
      (libsource (lib "eagle-import") (part "R-EU_R0402"))
    )
    (comp (ref "R1351")
      (value "100R")
      (footprint "eagle-import:R0402")
      (libsource (lib "eagle-import") (part "R-EU_R0402"))
    )
    (comp (ref "R1352")
      (value "100R")
      (footprint "eagle-import:R0402")
      (libsource (lib "eagle-import") (part "R-EU_R0402"))
    )
    (comp (ref "R1353")
      (value "100R")
      (footprint "eagle-import:R0402")
      (libsource (lib "eagle-import") (part "R-EU_R0402"))
    )
    (comp (ref "R1354")
      (value "100R")
      (footprint "eagle-import:R0402")
      (libsource (lib "eagle-import") (part "R-EU_R0402"))
    )
    (comp (ref "R1355")
      (value "100R")
      (footprint "eagle-import:R0402")
      (libsource (lib "eagle-import") (part "R-EU_R0402"))
    )
    (comp (ref "R1356")
      (value "100R")
      (footprint "eagle-import:R0402")
      (libsource (lib "eagle-import") (part "R-EU_R0402"))
    )
    (comp (ref "R1357")
      (value "100R")
      (footprint "eagle-import:R0402")
      (libsource (lib "eagle-import") (part "R-EU_R0402"))
    )
    (comp (ref "R1358")
      (value "100R")
      (footprint "eagle-import:R0402")
      (libsource (lib "eagle-import") (part "R-EU_R0402"))
    )
    (comp (ref "R1361")
      (value "100R")
      (footprint "eagle-import:R0402")
      (libsource (lib "eagle-import") (part "R-EU_R0402"))
    )
    (comp (ref "R1362")
      (value "100R")
      (footprint "eagle-import:R0402")
      (libsource (lib "eagle-import") (part "R-EU_R0402"))
    )
    (comp (ref "R1363")
      (value "100R")
      (footprint "eagle-import:R0402")
      (libsource (lib "eagle-import") (part "R-EU_R0402"))
    )
    (comp (ref "R1364")
      (value "100R")
      (footprint "eagle-import:R0402")
      (libsource (lib "eagle-import") (part "R-EU_R0402"))
    )
    (comp (ref "R1365")
      (value "100R")
      (footprint "eagle-import:R0402")
      (libsource (lib "eagle-import") (part "R-EU_R0402"))
    )
    (comp (ref "R1366")
      (value "100R")
      (footprint "eagle-import:R0402")
      (libsource (lib "eagle-import") (part "R-EU_R0402"))
    )
    (comp (ref "S1321")
      (value "KSR223G_SMD_1POL")
      (footprint "eagle-import:KSR223G_SMD_1POL")
      (libsource (lib "eagle-import") (part "KSR223G_SMD_1POL"))
    )
    (comp (ref "TP1371")
      (value "TPB1,27")
      (footprint "eagle-import:B1,27")
      (libsource (lib "eagle-import") (part "TPB1,27"))
    )
    (comp (ref "X1311")
      (value "MOLEX 105017-0001")
      (footprint "eagle-import:USB-B-MICRO-SMD_MOLEX-105017-0001")
      (libsource (lib "eagle-import") (part "USB_MICRO-B_MOLEX"))
    )
    (comp (ref "X1331")
      (value "XILINX-JTAG-14")
      (footprint "eagle-import:2X07_2MM00_SHROUDED_XILINX_JTAG")
      (libsource (lib "eagle-import") (part "XILINX-JTAG-14"))
    )
    (comp (ref "X1332")
      (value "HEADER-1X2")
      (footprint "eagle-import:1X02")
      (libsource (lib "eagle-import") (part "HEADER-1X2"))
    )
    (comp (ref "X1351")
      (value "PHOENIX_1990067_1X8X2MM50_PTSA-0-5")
      (footprint "eagle-import:PHOENIX_1990067_1X8X2MM50_PTSA-0-5")
      (libsource (lib "eagle-import") (part "PHOENIX_1990067_1X8X2MM50_PTSA-0-5"))
    )
    (comp (ref "X1361")
      (value "PHOENIX_1990067_1X8X2MM50_PTSA-0-5")
      (footprint "eagle-import:PHOENIX_1990067_1X8X2MM50_PTSA-0-5")
      (libsource (lib "eagle-import") (part "PHOENIX_1990067_1X8X2MM50_PTSA-0-5"))
    )
    (comp (ref "X1381")
      (value "HEADER-2X3")
      (footprint "eagle-import:2X03")
      (libsource (lib "eagle-import") (part "HEADER-2X3"))
    )
    (comp (ref "C1101")
      (value "4.7uF")
      (footprint "eagle-import:C0805")
      (libsource (lib "eagle-import") (part "C-EUC0805"))
    )
    (comp (ref "C1102")
      (value "1uF")
      (footprint "eagle-import:C0402")
      (libsource (lib "eagle-import") (part "C-EUC0402"))
    )
    (comp (ref "C1108")
      (value "100nF")
      (footprint "eagle-import:C0805")
      (libsource (lib "eagle-import") (part "C-EUC0805"))
    )
    (comp (ref "C1111")
      (value "22uF")
      (footprint "eagle-import:C0805")
      (libsource (lib "eagle-import") (part "C-EUC0805"))
    )
    (comp (ref "C1112")
      (value "22uF")
      (footprint "eagle-import:C0805")
      (libsource (lib "eagle-import") (part "C-EUC0805"))
    )
    (comp (ref "C1113")
      (value "22uF")
      (footprint "eagle-import:C0805")
      (libsource (lib "eagle-import") (part "C-EUC0805"))
    )
    (comp (ref "C1114")
      (value "22uF")
      (footprint "eagle-import:C0805")
      (libsource (lib "eagle-import") (part "C-EUC0805"))
    )
    (comp (ref "C1122")
      (value "N/A")
      (footprint "eagle-import:C0805")
      (libsource (lib "eagle-import") (part "C-EUC0805"))
    )
    (comp (ref "C1131")
      (value "100nF")
      (footprint "eagle-import:C0402")
      (libsource (lib "eagle-import") (part "C-EUC0402"))
    )
    (comp (ref "C1132")
      (value "1nF")
      (footprint "eagle-import:C0402")
      (libsource (lib "eagle-import") (part "C-EUC0402"))
    )
    (comp (ref "C1151")
      (value "100uF")
      (footprint "eagle-import:C0805")
      (libsource (lib "eagle-import") (part "C-EUC0805"))
    )
    (comp (ref "C1152")
      (value "100uF")
      (footprint "eagle-import:C0805")
      (libsource (lib "eagle-import") (part "C-EUC0805"))
    )
    (comp (ref "C1153")
      (value "100uF")
      (footprint "eagle-import:C0805")
      (libsource (lib "eagle-import") (part "C-EUC0805"))
    )
    (comp (ref "D1111")
      (value "CRS08")
      (footprint "eagle-import:SOD80C")
      (libsource (lib "eagle-import") (part "CRS08"))
    )
    (comp (ref "D1112")
      (value "CRS08")
      (footprint "eagle-import:SOD80C")
      (libsource (lib "eagle-import") (part "CRS08"))
    )
    (comp (ref "D1161")
      (value "CRS08")
      (footprint "eagle-import:SOD80C")
      (libsource (lib "eagle-import") (part "CRS08"))
    )
    (comp (ref "L1101")
      (value "440nH")
      (footprint "eagle-import:L1812")
      (libsource (lib "eagle-import") (part "L-EUL1812"))
    )
    (comp (ref "R1101")
      (value "10kR 0%5")
      (footprint "eagle-import:R0402")
      (libsource (lib "eagle-import") (part "R-EU_R0402"))
    )
    (comp (ref "R1102")
      (value "45.3kR 0%5")
      (footprint "eagle-import:R0402")
      (libsource (lib "eagle-import") (part "R-EU_R0402"))
    )
    (comp (ref "R1103")
      (value "N/A")
      (footprint "eagle-import:R0402")
      (libsource (lib "eagle-import") (part "R-EU_R0402"))
    )
    (comp (ref "R1104")
      (value "N/A")
      (footprint "eagle-import:R0402")
      (libsource (lib "eagle-import") (part "R-EU_R0402"))
    )
    (comp (ref "R1105")
      (value "110kR")
      (footprint "eagle-import:R0402")
      (libsource (lib "eagle-import") (part "R-EU_R0402"))
    )
    (comp (ref "R1106")
      (value "200kR")
      (footprint "eagle-import:R0402")
      (libsource (lib "eagle-import") (part "R-EU_R0402"))
    )
    (comp (ref "R1107")
      (value "100kR")
      (footprint "eagle-import:R0402")
      (libsource (lib "eagle-import") (part "R-EU_R0402"))
    )
    (comp (ref "R1108")
      (value "2R")
      (footprint "eagle-import:R0805")
      (libsource (lib "eagle-import") (part "R-EU_R0805"))
    )
    (comp (ref "R1122")
      (value "N/A")
      (footprint "eagle-import:R0805")
      (libsource (lib "eagle-import") (part "R-EU_R0805"))
    )
    (comp (ref "R1131")
      (value "15kR")
      (footprint "eagle-import:R0402")
      (libsource (lib "eagle-import") (part "R-EU_R0402"))
    )
    (comp (ref "R1161")
      (value "220kR")
      (footprint "eagle-import:R0402")
      (libsource (lib "eagle-import") (part "R-EU_R0402"))
    )
    (comp (ref "U1101")
      (value "TPS53353")
      (footprint "eagle-import:DQP-22")
      (libsource (lib "eagle-import") (part "TPS53353"))
    )
    (comp (ref "C1011")
      (value "100nF")
      (footprint "eagle-import:C0402")
      (libsource (lib "eagle-import") (part "C-EUC0402"))
    )
    (comp (ref "C1012")
      (value "100nF")
      (footprint "eagle-import:C0402")
      (libsource (lib "eagle-import") (part "C-EUC0402"))
    )
    (comp (ref "C1013")
      (value "100nF")
      (footprint "eagle-import:C0402")
      (libsource (lib "eagle-import") (part "C-EUC0402"))
    )
    (comp (ref "D1021")
      (value "ASMT-YTB7-0AA02_RGB")
      (footprint "eagle-import:ASMT-YTB7_0AA02_RGB")
      (libsource (lib "eagle-import") (part "ASMT-YTB7-0AA02_RGB"))
    )
    (comp (ref "R1011")
      (value "1kR")
      (footprint "eagle-import:R0402")
      (libsource (lib "eagle-import") (part "R-EU_R0402"))
    )
    (comp (ref "R1012")
      (value "1kR")
      (footprint "eagle-import:R0402")
      (libsource (lib "eagle-import") (part "R-EU_R0402"))
    )
    (comp (ref "R1013")
      (value "1kR")
      (footprint "eagle-import:R0402")
      (libsource (lib "eagle-import") (part "R-EU_R0402"))
    )
    (comp (ref "R1021")
      (value "820R")
      (footprint "eagle-import:R0402")
      (libsource (lib "eagle-import") (part "R-EU_R0402"))
    )
    (comp (ref "R1022")
      (value "1kR")
      (footprint "eagle-import:R0402")
      (libsource (lib "eagle-import") (part "R-EU_R0402"))
    )
    (comp (ref "R1023")
      (value "820R")
      (footprint "eagle-import:R0402")
      (libsource (lib "eagle-import") (part "R-EU_R0402"))
    )
    (comp (ref "X1011")
      (value "TTE_EN11-HSM")
      (footprint "eagle-import:TTE_EN11-HSM")
      (libsource (lib "eagle-import") (part "TTE_EN11-HSM"))
    )
    (comp (ref "C0811")
      (value "100nF")
      (footprint "eagle-import:C0402")
      (libsource (lib "eagle-import") (part "C-EUC0402"))
    )
    (comp (ref "C0821")
      (value "1nF")
      (footprint "eagle-import:C0402")
      (libsource (lib "eagle-import") (part "C-EUC0402"))
    )
    (comp (ref "C0831")
      (value "1nF")
      (footprint "eagle-import:C0402")
      (libsource (lib "eagle-import") (part "C-EUC0402"))
    )
    (comp (ref "C0832")
      (value "1nF")
      (footprint "eagle-import:C0402")
      (libsource (lib "eagle-import") (part "C-EUC0402"))
    )
    (comp (ref "C0851")
      (value "10nF")
      (footprint "eagle-import:C0402")
      (libsource (lib "eagle-import") (part "C-EUC0402"))
    )
    (comp (ref "C0852")
      (value "10nF")
      (footprint "eagle-import:C0402")
      (libsource (lib "eagle-import") (part "C-EUC0402"))
    )
    (comp (ref "C0853")
      (value "10nF")
      (footprint "eagle-import:C0402")
      (libsource (lib "eagle-import") (part "C-EUC0402"))
    )
    (comp (ref "C0891")
      (value "0pF")
      (footprint "eagle-import:C0402")
      (libsource (lib "eagle-import") (part "C-EUC0402"))
    )
    (comp (ref "C0893")
      (value "0pF")
      (footprint "eagle-import:C0402")
      (libsource (lib "eagle-import") (part "C-EUC0402"))
    )
    (comp (ref "C0895")
      (value "0pF")
      (footprint "eagle-import:C0402")
      (libsource (lib "eagle-import") (part "C-EUC0402"))
    )
    (comp (ref "C0897")
      (value "0pF")
      (footprint "eagle-import:C0402")
      (libsource (lib "eagle-import") (part "C-EUC0402"))
    )
    (comp (ref "L0821")
      (value "2.7nH")
      (footprint "eagle-import:L0603")
      (libsource (lib "eagle-import") (part "L-EUL0603"))
    )
    (comp (ref "L0853")
      (value "6.8nH")
      (footprint "eagle-import:L0603")
      (libsource (lib "eagle-import") (part "L-EUL0603"))
    )
    (comp (ref "L0892")
      (value "0nH")
      (footprint "eagle-import:L0603")
      (libsource (lib "eagle-import") (part "L-EUL0603"))
    )
    (comp (ref "L0896")
      (value "0nH")
      (footprint "eagle-import:L0603")
      (libsource (lib "eagle-import") (part "L-EUL0603"))
    )
    (comp (ref "R0821")
      (value "100R")
      (footprint "eagle-import:R0402")
      (libsource (lib "eagle-import") (part "R-EU_R0402"))
    )
    (comp (ref "R0822")
      (value "10kR")
      (footprint "eagle-import:R0402")
      (libsource (lib "eagle-import") (part "R-EU_R0402"))
    )
    (comp (ref "R0861")
      (value "10kR")
      (footprint "eagle-import:R0402")
      (libsource (lib "eagle-import") (part "R-EU_R0402"))
    )
    (comp (ref "R0862")
      (value "10kR")
      (footprint "eagle-import:R0402")
      (libsource (lib "eagle-import") (part "R-EU_R0402"))
    )
    (comp (ref "R0863")
      (value "10kR")
      (footprint "eagle-import:R0402")
      (libsource (lib "eagle-import") (part "R-EU_R0402"))
    )
    (comp (ref "TP_RFX_DET")
      (value "TPB1,27")
      (footprint "eagle-import:B1,27")
      (libsource (lib "eagle-import") (part "TPB1,27"))
    )
    (comp (ref "U0811")
      (value "PE4259")
      (footprint "eagle-import:SC-70_6-LEAD_2X1MM25_0P65")
      (libsource (lib "eagle-import") (part "PE4259"))
    )
    (comp (ref "U0821")
      (value "RFX1010")
      (footprint "eagle-import:QFN16-3X3-0P5-PAD")
      (libsource (lib "eagle-import") (part "RFX1010"))
    )
    (comp (ref "U0881")
      (value "B39871B3440U410")
      (footprint "eagle-import:B3440_3MM-X-3MM")
      (libsource (lib "eagle-import") (part "B3440"))
    )
    (comp (ref "X0891")
      (value "ANTENNATINY")
      (footprint "eagle-import:SMA_UFL_PAD_TINY")
      (libsource (lib "eagle-import") (part "ANTENNATINY"))
    )
    (comp (ref "X0895")
      (value "ANTENNATINY")
      (footprint "eagle-import:SMA_UFL_PAD_TINY")
      (libsource (lib "eagle-import") (part "ANTENNATINY"))
    )
    (comp (ref "C1201")
      (value "10uF")
      (footprint "eagle-import:C0603")
      (libsource (lib "eagle-import") (part "C-EUC0603"))
    )
    (comp (ref "C1221")
      (value "10uF")
      (footprint "eagle-import:C0603")
      (libsource (lib "eagle-import") (part "C-EUC0603"))
    )
    (comp (ref "L1211")
      (value "4.7uH")
      (footprint "eagle-import:L2520")
      (libsource (lib "eagle-import") (part "L-EUL2520"))
    )
    (comp (ref "R1211")
      (value "10kR")
      (footprint "eagle-import:R0402")
      (libsource (lib "eagle-import") (part "R-EU_R0402"))
    )
    (comp (ref "U1211")
      (value "TPS62745DSSR")
      (footprint "eagle-import:WSON-12")
      (libsource (lib "eagle-import") (part "TPS62745"))
    )
    (comp (ref "C0611")
      (value "100nF")
      (footprint "eagle-import:C0402")
      (libsource (lib "eagle-import") (part "C-EUC0402"))
    )
    (comp (ref "C0612")
      (value "100nF")
      (footprint "eagle-import:C0402")
      (libsource (lib "eagle-import") (part "C-EUC0402"))
    )
    (comp (ref "C0621")
      (value "1uF")
      (footprint "eagle-import:C0402")
      (libsource (lib "eagle-import") (part "C-EUC0402"))
    )
    (comp (ref "R0621")
      (value "100kR")
      (footprint "eagle-import:R0402")
      (libsource (lib "eagle-import") (part "R-EU_R0402"))
    )
    (comp (ref "U0601")
      (value "MAX5217")
      (footprint "eagle-import:µMAX8")
      (libsource (lib "eagle-import") (part "MAX5217"))
    )
    (comp (ref "HB_351")
      (value "MOUNT-PAD-ROUND3.2")
      (footprint "eagle-import:3,2-PAD")
      (libsource (lib "eagle-import") (part "MOUNT-PAD-ROUND3.2"))
    )
    (comp (ref "HB_352")
      (value "MOUNT-PAD-ROUND3.2")
      (footprint "eagle-import:3,2-PAD")
      (libsource (lib "eagle-import") (part "MOUNT-PAD-ROUND3.2"))
    )
    (comp (ref "HB_353")
      (value "MOUNT-PAD-ROUND3.2")
      (footprint "eagle-import:3,2-PAD")
      (libsource (lib "eagle-import") (part "MOUNT-PAD-ROUND3.2"))
    )
    (comp (ref "HB_354")
      (value "MOUNT-PAD-ROUND3.2")
      (footprint "eagle-import:3,2-PAD")
      (libsource (lib "eagle-import") (part "MOUNT-PAD-ROUND3.2"))
    )
    (comp (ref "JB3")
      (value "LSHM-130-04.0-L-DV-A-S-K-TR")
      (footprint "eagle-import:SAMTEC_LSHM-130-DV")
      (libsource (lib "eagle-import") (part "SAMTEC_LSHM-130-DV_JB3"))
    )
    (comp (ref "C0701")
      (value "1uF")
      (footprint "eagle-import:C0402")
      (libsource (lib "eagle-import") (part "C-EUC0402"))
    )
    (comp (ref "C0703")
      (value "1uF")
      (footprint "eagle-import:C0402")
      (libsource (lib "eagle-import") (part "C-EUC0402"))
    )
    (comp (ref "C0704")
      (value "1uF")
      (footprint "eagle-import:C0402")
      (libsource (lib "eagle-import") (part "C-EUC0402"))
    )
    (comp (ref "C0706")
      (value "100nF")
      (footprint "eagle-import:C0402")
      (libsource (lib "eagle-import") (part "C-EUC0402"))
    )
    (comp (ref "C0707")
      (value "100nF")
      (footprint "eagle-import:C0402")
      (libsource (lib "eagle-import") (part "C-EUC0402"))
    )
    (comp (ref "C0708")
      (value "100nF")
      (footprint "eagle-import:C0402")
      (libsource (lib "eagle-import") (part "C-EUC0402"))
    )
    (comp (ref "C0711")
      (value "10nF")
      (footprint "eagle-import:C0402")
      (libsource (lib "eagle-import") (part "C-EUC0402"))
    )
    (comp (ref "C0712")
      (value "10nF")
      (footprint "eagle-import:C0402")
      (libsource (lib "eagle-import") (part "C-EUC0402"))
    )
    (comp (ref "C0713")
      (value "N/A")
      (footprint "eagle-import:C0402")
      (libsource (lib "eagle-import") (part "C-EUC0402"))
    )
    (comp (ref "L0701")
      (value "0R")
      (footprint "eagle-import:R1206")
      (libsource (lib "eagle-import") (part "R-EU_R1206"))
    )
    (comp (ref "L0702")
      (value "0R")
      (footprint "eagle-import:R1206")
      (libsource (lib "eagle-import") (part "R-EU_R1206"))
    )
    (comp (ref "L0703")
      (value "300R")
      (footprint "eagle-import:R1206")
      (libsource (lib "eagle-import") (part "R-EU_R1206"))
    )
    (comp (ref "L0704")
      (value "300R")
      (footprint "eagle-import:R1206")
      (libsource (lib "eagle-import") (part "R-EU_R1206"))
    )
    (comp (ref "L0721")
      (value "MURATA DXW21HN5011BL")
      (footprint "eagle-import:DXW21HN5011BL")
      (libsource (lib "eagle-import") (part "DXW21HN5011BL"))
    )
    (comp (ref "L0722")
      (value "Johanson 2450BL15B050E")
      (footprint "eagle-import:2450BL15B050")
      (libsource (lib "eagle-import") (part "2450BL15B050"))
    )
    (comp (ref "R0711")
      (value "130R")
      (footprint "eagle-import:R0402")
      (libsource (lib "eagle-import") (part "R-EU_R0402"))
    )
    (comp (ref "R0751")
      (value "100R")
      (footprint "eagle-import:R0402")
      (libsource (lib "eagle-import") (part "R-EU_R0402"))
    )
    (comp (ref "R0752")
      (value "100R")
      (footprint "eagle-import:R0402")
      (libsource (lib "eagle-import") (part "R-EU_R0402"))
    )
    (comp (ref "R0753")
      (value "100R")
      (footprint "eagle-import:R0402")
      (libsource (lib "eagle-import") (part "R-EU_R0402"))
    )
    (comp (ref "R0754")
      (value "100R")
      (footprint "eagle-import:R0402")
      (libsource (lib "eagle-import") (part "R-EU_R0402"))
    )
    (comp (ref "R0755")
      (value "100R")
      (footprint "eagle-import:R0402")
      (libsource (lib "eagle-import") (part "R-EU_R0402"))
    )
    (comp (ref "R0756")
      (value "100R")
      (footprint "eagle-import:R0402")
      (libsource (lib "eagle-import") (part "R-EU_R0402"))
    )
    (comp (ref "U0701")
      (value "AT86RF215-ZU")
      (footprint "eagle-import:QFN48_7X7-0P5-PAD")
      (libsource (lib "eagle-import") (part "AT86RF215"))
    )
    (comp (ref "U0711")
      (value "ASVTX-13-D-26.000MHZ-I05-T")
      (footprint "eagle-import:ASVTX-13")
      (libsource (lib "eagle-import") (part "ASVTX-13-D"))
    )
    (comp (ref "C0501")
      (value "100nF")
      (footprint "eagle-import:C0402")
      (libsource (lib "eagle-import") (part "C-EUC0402"))
    )
    (comp (ref "C0511")
      (value "1uF")
      (footprint "eagle-import:C0402")
      (libsource (lib "eagle-import") (part "C-EUC0402"))
    )
    (comp (ref "C0512")
      (value "1uF")
      (footprint "eagle-import:C0402")
      (libsource (lib "eagle-import") (part "C-EUC0402"))
    )
    (comp (ref "R0531")
      (value "220kR")
      (footprint "eagle-import:R0402")
      (libsource (lib "eagle-import") (part "R-EU_R0402"))
    )
    (comp (ref "R0532")
      (value "1kR")
      (footprint "eagle-import:R0402")
      (libsource (lib "eagle-import") (part "R-EU_R0402"))
    )
    (comp (ref "R0551")
      (value "1.5kR")
      (footprint "eagle-import:R0402")
      (libsource (lib "eagle-import") (part "R-EU_R0402"))
    )
    (comp (ref "R0552")
      (value "2.0kR")
      (footprint "eagle-import:R0402")
      (libsource (lib "eagle-import") (part "R-EU_R0402"))
    )
    (comp (ref "R0553")
      (value "27R")
      (footprint "eagle-import:R0603")
      (libsource (lib "eagle-import") (part "R-EU_R0603"))
    )
    (comp (ref "T0551")
      (value "MMBT2222")
      (footprint "eagle-import:SOT23")
      (libsource (lib "eagle-import") (part "BC846"))
    )
    (comp (ref "U0501")
      (value "MIDAS_MCCOG21605B6W-FPTLWI")
      (footprint "eagle-import:MIDAS_MCCOG21605B6W-FPTLWI")
      (libsource (lib "eagle-import") (part "MIDAS_MCCOG21605B6W-FPTLWI"))
    )
    (comp (ref "C0911")
      (value "100nF")
      (footprint "eagle-import:C0402")
      (libsource (lib "eagle-import") (part "C-EUC0402"))
    )
    (comp (ref "C0912")
      (value "100nF")
      (footprint "eagle-import:C0402")
      (libsource (lib "eagle-import") (part "C-EUC0402"))
    )
    (comp (ref "C0913")
      (value "100nF")
      (footprint "eagle-import:C0402")
      (libsource (lib "eagle-import") (part "C-EUC0402"))
    )
    (comp (ref "C0921")
      (value "100nF")
      (footprint "eagle-import:C0402")
      (libsource (lib "eagle-import") (part "C-EUC0402"))
    )
    (comp (ref "C0922")
      (value "100nF")
      (footprint "eagle-import:C0402")
      (libsource (lib "eagle-import") (part "C-EUC0402"))
    )
    (comp (ref "D0971")
      (value "CMD17-21VGD/TR8 GREEN")
      (footprint "eagle-import:CHIP-LED0805")
      (libsource (lib "eagle-import") (part "LEDCHIP-LED0805"))
    )
    (comp (ref "D0972")
      (value "CMD17-21VRD/TR8 RED")
      (footprint "eagle-import:CHIP-LED0805")
      (libsource (lib "eagle-import") (part "LEDCHIP-LED0805"))
    )
    (comp (ref "L0911")
      (value "300R")
      (footprint "eagle-import:R1206")
      (libsource (lib "eagle-import") (part "R-EU_R1206"))
    )
    (comp (ref "L0921")
      (value "300R")
      (footprint "eagle-import:R1206")
      (libsource (lib "eagle-import") (part "R-EU_R1206"))
    )
    (comp (ref "L0922")
      (value "300R")
      (footprint "eagle-import:R1206")
      (libsource (lib "eagle-import") (part "R-EU_R1206"))
    )
    (comp (ref "R0911")
      (value "12kR 1%0")
      (footprint "eagle-import:R0402")
      (libsource (lib "eagle-import") (part "R-EU_R0402"))
    )
    (comp (ref "R0912")
      (value "100R")
      (footprint "eagle-import:R0402")
      (libsource (lib "eagle-import") (part "R-EU_R0402"))
    )
    (comp (ref "R0913")
      (value "100kR")
      (footprint "eagle-import:R0402")
      (libsource (lib "eagle-import") (part "R-EU_R0402"))
    )
    (comp (ref "R0931")
      (value "10kR")
      (footprint "eagle-import:R0402")
      (libsource (lib "eagle-import") (part "R-EU_R0402"))
    )
    (comp (ref "R0941")
      (value "100R")
      (footprint "eagle-import:R0402")
      (libsource (lib "eagle-import") (part "R-EU_R0402"))
    )
    (comp (ref "R0961")
      (value "100R")
      (footprint "eagle-import:R0402")
      (libsource (lib "eagle-import") (part "R-EU_R0402"))
    )
    (comp (ref "R0962")
      (value "100R")
      (footprint "eagle-import:R0402")
      (libsource (lib "eagle-import") (part "R-EU_R0402"))
    )
    (comp (ref "R0963")
      (value "100R")
      (footprint "eagle-import:R0402")
      (libsource (lib "eagle-import") (part "R-EU_R0402"))
    )
    (comp (ref "R0964")
      (value "100R")
      (footprint "eagle-import:R0402")
      (libsource (lib "eagle-import") (part "R-EU_R0402"))
    )
    (comp (ref "R0965")
      (value "100R")
      (footprint "eagle-import:R0402")
      (libsource (lib "eagle-import") (part "R-EU_R0402"))
    )
    (comp (ref "R0966")
      (value "100R")
      (footprint "eagle-import:R0402")
      (libsource (lib "eagle-import") (part "R-EU_R0402"))
    )
    (comp (ref "R0967")
      (value "100R")
      (footprint "eagle-import:R0402")
      (libsource (lib "eagle-import") (part "R-EU_R0402"))
    )
    (comp (ref "R0968")
      (value "100R")
      (footprint "eagle-import:R0402")
      (libsource (lib "eagle-import") (part "R-EU_R0402"))
    )
    (comp (ref "R0971")
      (value "560R")
      (footprint "eagle-import:R0402")
      (libsource (lib "eagle-import") (part "R-EU_R0402"))
    )
    (comp (ref "R0972")
      (value "560R")
      (footprint "eagle-import:R0402")
      (libsource (lib "eagle-import") (part "R-EU_R0402"))
    )
    (comp (ref "TP_TXDEN")
      (value "TPB1,27")
      (footprint "eagle-import:B1,27")
      (libsource (lib "eagle-import") (part "TPB1,27"))
    )
    (comp (ref "U0911")
      (value "FT232HL")
      (footprint "eagle-import:LQFP48")
      (libsource (lib "eagle-import") (part "FTDI232HL"))
    )
    (comp (ref "FPGA_EN1")
      (value "TPB1,27")
      (footprint "eagle-import:B1,27")
      (libsource (lib "eagle-import") (part "TPB1,27"))
    )
    (comp (ref "FPGA_MODE")
      (value "TPB1,27")
      (footprint "eagle-import:B1,27")
      (libsource (lib "eagle-import") (part "TPB1,27"))
    )
    (comp (ref "JB1")
      (value "LSHM-150-04.0-L-DV-A-S-K-TR")
      (footprint "eagle-import:SAMTEC_LSHM-150-DV")
      (libsource (lib "eagle-import") (part "SAMTEC_LSHM-150-DV_JB1"))
    )
    (comp (ref "PGOOD")
      (value "TPB1,27")
      (footprint "eagle-import:B1,27")
      (libsource (lib "eagle-import") (part "TPB1,27"))
    )
    (comp (ref "C1431")
      (value "1uF")
      (footprint "eagle-import:C0402")
      (libsource (lib "eagle-import") (part "C-EUC0402"))
    )
    (comp (ref "C1432")
      (value "100nF")
      (footprint "eagle-import:C0402")
      (libsource (lib "eagle-import") (part "C-EUC0402"))
    )
    (comp (ref "C1441")
      (value "1uF")
      (footprint "eagle-import:C0402")
      (libsource (lib "eagle-import") (part "C-EUC0402"))
    )
    (comp (ref "C1442")
      (value "100nF")
      (footprint "eagle-import:C0402")
      (libsource (lib "eagle-import") (part "C-EUC0402"))
    )
    (comp (ref "J1411")
      (value "ABRACON_ARJE-0034")
      (footprint "eagle-import:ARJE-0034_RJ45_WITH_MAGNETICS")
      (libsource (lib "eagle-import") (part "ARJE-0034_RJ45_WITH_MAGNETICS"))
    )
    (comp (ref "R1421")
      (value "470R")
      (footprint "eagle-import:R0402")
      (libsource (lib "eagle-import") (part "R-EU_R0402"))
    )
    (comp (ref "R1422")
      (value "470R")
      (footprint "eagle-import:R0402")
      (libsource (lib "eagle-import") (part "R-EU_R0402"))
    )
  )
  (nets
    (net (code "1") (name "+2V5") (class "Default")
      (node (ref "C1221") (pin "1") (pinfunction "1_1") (pintype "passive"))
      (node (ref "L1211") (pin "1") (pinfunction "1_1") (pintype "passive"))
      (node (ref "R0201") (pin "1") (pinfunction "1_1") (pintype "passive"))
      (node (ref "U1211") (pin "5") (pinfunction "VOUT_5") (pintype "passive"))
      (node (ref "X1381") (pin "4") (pinfunction "4_4") (pintype "passive"))
    )
    (net (code "2") (name "+3V3") (class "Default")
      (node (ref "C0501") (pin "1") (pinfunction "1_1") (pintype "passive"))
      (node (ref "C0611") (pin "1") (pinfunction "1_1") (pintype "passive"))
      (node (ref "C0612") (pin "1") (pinfunction "1_1") (pintype "passive"))
      (node (ref "C0701") (pin "1") (pinfunction "1_1") (pintype "passive"))
      (node (ref "C0711") (pin "1") (pinfunction "1_1") (pintype "passive"))
      (node (ref "C0811") (pin "1") (pinfunction "1_1") (pintype "passive"))
      (node (ref "C0851") (pin "1") (pinfunction "1_1") (pintype "passive"))
      (node (ref "C0852") (pin "1") (pinfunction "1_1") (pintype "passive"))
      (node (ref "C0853") (pin "1") (pinfunction "1_1") (pintype "passive"))
      (node (ref "C0911") (pin "1") (pinfunction "1_1") (pintype "passive"))
      (node (ref "C1131") (pin "1") (pinfunction "1_1") (pintype "passive"))
      (node (ref "C1151") (pin "1") (pinfunction "1_1") (pintype "passive"))
      (node (ref "C1152") (pin "1") (pinfunction "1_1") (pintype "passive"))
      (node (ref "C1153") (pin "1") (pinfunction "1_1") (pintype "passive"))
      (node (ref "C1201") (pin "1") (pinfunction "1_1") (pintype "passive"))
      (node (ref "C1431") (pin "1") (pinfunction "1_1") (pintype "passive"))
      (node (ref "C1432") (pin "1") (pinfunction "1_1") (pintype "passive"))
      (node (ref "C1441") (pin "1") (pinfunction "1_1") (pintype "passive"))
      (node (ref "C1442") (pin "1") (pinfunction "1_1") (pintype "passive"))
      (node (ref "J1411") (pin "5") (pinfunction "5_5") (pintype "passive"))
      (node (ref "J1411") (pin "6") (pinfunction "6_6") (pintype "passive"))
      (node (ref "JB1") (pin "14") (pinfunction "U3V3IN_14") (pintype "power_in"))
      (node (ref "JB1") (pin "16") (pinfunction "U3V3IN_16") (pintype "power_in"))
      (node (ref "JB1") (pin "2") (pinfunction "VIN_2") (pintype "power_in"))
      (node (ref "JB1") (pin "4") (pinfunction "VIN_4") (pintype "power_in"))
      (node (ref "JB1") (pin "6") (pinfunction "VIN_6") (pintype "power_in"))
      (node (ref "JB2") (pin "1") (pinfunction "VIN_1") (pintype "power_in"))
      (node (ref "JB2") (pin "3") (pinfunction "VIN_3") (pintype "power_in"))
      (node (ref "JB2") (pin "5") (pinfunction "VIN_5") (pintype "power_in"))
      (node (ref "JB2") (pin "7") (pinfunction "VIN_7") (pintype "power_in"))
      (node (ref "L0703") (pin "1") (pinfunction "1_1") (pintype "passive"))
      (node (ref "L0704") (pin "1") (pinfunction "1_1") (pintype "passive"))
      (node (ref "L0853") (pin "1") (pinfunction "1_1") (pintype "passive"))
      (node (ref "L1101") (pin "1") (pinfunction "1_1") (pintype "passive"))
      (node (ref "R0203") (pin "2") (pinfunction "2_2") (pintype "passive"))
      (node (ref "R0411") (pin "2") (pinfunction "2_2") (pintype "passive"))
      (node (ref "R0412") (pin "2") (pinfunction "2_2") (pintype "passive"))
      (node (ref "R1102") (pin "2") (pinfunction "2_2") (pintype "passive"))
      (node (ref "R1104") (pin "1") (pinfunction "1_1") (pintype "passive"))
      (node (ref "U0501") (pin "12") (pinfunction "A_BL_12") (pintype "passive"))
      (node (ref "U0501") (pin "4") (pinfunction "VDD_4") (pintype "power_in"))
      (node (ref "U0601") (pin "1") (pinfunction "REF_1") (pintype "passive"))
      (node (ref "U0601") (pin "5") (pinfunction "~{AUX}_5") (pintype "input"))
      (node (ref "U0601") (pin "7") (pinfunction "VDD_7") (pintype "power_in"))
      (node (ref "U0711") (pin "4") (pinfunction "VCC_3V3_4") (pintype "power_in"))
      (node (ref "U0811") (pin "6") (pinfunction "VDD_~{CTRL}_6") (pintype "passive"))
      (node (ref "U0821") (pin "13") (pinfunction "VDD2_13") (pintype "power_in"))
      (node (ref "U0821") (pin "15") (pinfunction "VDD1_15") (pintype "power_in"))
      (node (ref "U0911") (pin "40") (pinfunction "VREGIN_40") (pintype "power_in"))
      (node (ref "U1211") (pin "1") (pinfunction "VIN_1") (pintype "power_in"))
      (node (ref "U1211") (pin "10") (pinfunction "VSEL2_10") (pintype "input"))
      (node (ref "U1211") (pin "11") (pinfunction "VSEL1_11") (pintype "input"))
      (node (ref "U1211") (pin "9") (pinfunction "VSEL3_9") (pintype "input"))
      (node (ref "X1332") (pin "1") (pinfunction "1_1") (pintype "passive"))
    )
    (net (code "3") (name "+5V_USB") (class "Default")
      (node (ref "D1112") (pin "A") (pinfunction "A_A") (pintype "passive"))
      (node (ref "PF1311") (pin "1") (pinfunction "1_1") (pintype "passive"))
    )
    (net (code "4") (name "26MHZ_DAC_OUT") (class "Default")
      (node (ref "R0621") (pin "1") (pinfunction "1_1") (pintype "passive"))
      (node (ref "U0601") (pin "6") (pinfunction "OUT_6") (pintype "passive"))
    )
    (net (code "5") (name "BOARD_LCD_RESETN") (class "Default")
      (node (ref "JB1") (pin "98") (pinfunction "B14_L4_MIO_N_98") (pintype "passive"))
      (node (ref "R0532") (pin "1") (pinfunction "1_1") (pintype "passive"))
    )
    (net (code "6") (name "BOARD_ROTENC_I") (class "Default")
      (node (ref "JB2") (pin "22") (pinfunction "B14_L14_CLK_P_22") (pintype "passive"))
      (node (ref "R1011") (pin "2") (pinfunction "2_2") (pintype "passive"))
    )
    (net (code "7") (name "BOARD_ROTENC_PUSH") (class "Default")
      (node (ref "JB2") (pin "26") (pinfunction "B14_L13_CLK_P_26") (pintype "passive"))
      (node (ref "R1013") (pin "2") (pinfunction "2_2") (pintype "passive"))
    )
    (net (code "8") (name "BOARD_ROTENC_Q") (class "Default")
      (node (ref "JB2") (pin "24") (pinfunction "B14_L14_CLK_N_24") (pintype "passive"))
      (node (ref "R1012") (pin "2") (pinfunction "2_2") (pintype "passive"))
    )
    (net (code "9") (name "BOARD_SCL") (class "Default")
      (node (ref "JB1") (pin "82") (pinfunction "B16_L8_N_82") (pintype "passive"))
      (node (ref "R0412") (pin "1") (pinfunction "1_1") (pintype "passive"))
      (node (ref "U0501") (pin "7") (pinfunction "SCL_7") (pintype "input"))
      (node (ref "U0601") (pin "3") (pinfunction "SCL_3") (pintype "input"))
    )
    (net (code "10") (name "BOARD_SDA") (class "Default")
      (node (ref "JB1") (pin "84") (pinfunction "B16_L8_P_84") (pintype "passive"))
      (node (ref "R0411") (pin "1") (pinfunction "1_1") (pintype "passive"))
      (node (ref "U0501") (pin "6") (pinfunction "SDA_6") (pintype "bidirectional"))
      (node (ref "U0601") (pin "4") (pinfunction "SDA_4") (pintype "tri_state"))
    )
    (net (code "11") (name "CLKIN2_N") (class "Default")
      (node (ref "JB3") (pin "31") (pinfunction "CLKIN2_CLK_N_31") (pintype "passive"))
      (node (ref "JB3") (pin "39") (pinfunction "B13_L16_N_39") (pintype "passive"))
    )
    (net (code "12") (name "CLKIN2_P") (class "Default")
      (node (ref "JB3") (pin "33") (pinfunction "CLKIN2_CLK_P_33") (pintype "passive"))
      (node (ref "JB3") (pin "37") (pinfunction "B13_L16_P_37") (pintype "passive"))
    )
    (net (code "13") (name "DDR3_INIT_CALIB_COMPLETE") (class "Default")
      (node (ref "JB2") (pin "14") (pinfunction "B14_L8_P_14") (pintype "passive"))
      (node (ref "TP1371") (pin "TP") (pinfunction "TP_TP") (pintype "input"))
    )
    (net (code "14") (name "FE09_ANT") (class "Default")
      (node (ref "U0821") (pin "9") (pinfunction "ANT_9") (pintype "bidirectional"))
      (node (ref "U0881") (pin "2") (pinfunction "IN_2") (pintype "passive"))
    )
    (net (code "15") (name "FE09_RX") (class "Default")
      (node (ref "C0832") (pin "1") (pinfunction "1_1") (pintype "passive"))
      (node (ref "U0821") (pin "14") (pinfunction "RX_14") (pintype "output"))
    )
    (net (code "16") (name "FE09_TX") (class "Default")
      (node (ref "C0831") (pin "1") (pinfunction "1_1") (pintype "passive"))
      (node (ref "U0821") (pin "3") (pinfunction "TX_3") (pintype "input"))
    )
    (net (code "17") (name "FPGA_B16_L2_N") (class "Default")
      (node (ref "JB1") (pin "79") (pinfunction "B16_L2_N_79") (pintype "passive"))
    )
    (net (code "18") (name "FPGA_B16_L2_P") (class "Default")
      (node (ref "JB1") (pin "81") (pinfunction "B16_L2_P_81") (pintype "passive"))
    )
    (net (code "19") (name "FPGA_B16_L5_N") (class "Default")
      (node (ref "JB1") (pin "75") (pinfunction "B16_L5_N_75") (pintype "passive"))
    )
    (net (code "20") (name "FPGA_B16_L5_P") (class "Default")
      (node (ref "JB1") (pin "77") (pinfunction "B16_L5_P_77") (pintype "passive"))
    )
    (net (code "21") (name "FPGA_B16_L6_N") (class "Default")
      (node (ref "JB1") (pin "85") (pinfunction "B16_L6_N_85") (pintype "passive"))
    )
    (net (code "22") (name "FPGA_B16_L6_P") (class "Default")
      (node (ref "JB1") (pin "87") (pinfunction "B16_L6_P_87") (pintype "passive"))
    )
    (net (code "23") (name "FPGA_B16_L7_N") (class "Default")
      (node (ref "JB1") (pin "59") (pinfunction "B16_L7_N_59") (pintype "passive"))
      (node (ref "R1364") (pin "1") (pinfunction "1_1") (pintype "passive"))
    )
    (net (code "24") (name "FPGA_B16_L7_P") (class "Default")
      (node (ref "JB1") (pin "61") (pinfunction "B16_L7_P_61") (pintype "passive"))
      (node (ref "R1363") (pin "1") (pinfunction "1_1") (pintype "passive"))
    )
    (net (code "25") (name "FPGA_B16_L9_N") (class "Default")
      (node (ref "JB1") (pin "55") (pinfunction "B16_L9_N_55") (pintype "passive"))
      (node (ref "R1362") (pin "1") (pinfunction "1_1") (pintype "passive"))
    )
    (net (code "26") (name "FPGA_B16_L9_P") (class "Default")
      (node (ref "JB1") (pin "57") (pinfunction "B16_L9_P_57") (pintype "passive"))
      (node (ref "R1361") (pin "1") (pinfunction "1_1") (pintype "passive"))
    )
    (net (code "27") (name "FPGA_B16_L10_N") (class "Default")
      (node (ref "JB1") (pin "69") (pinfunction "B16_L10_N_69") (pintype "passive"))
    )
    (net (code "28") (name "FPGA_B16_L10_P") (class "Default")
      (node (ref "JB1") (pin "71") (pinfunction "B16_L10_P_71") (pintype "passive"))
    )
    (net (code "29") (name "FPGA_B16_L11_N") (class "Default")
      (node (ref "JB1") (pin "67") (pinfunction "B16_L11_N_67") (pintype "passive"))
      (node (ref "R1366") (pin "1") (pinfunction "1_1") (pintype "passive"))
    )
    (net (code "30") (name "FPGA_B16_L11_P") (class "Default")
      (node (ref "JB1") (pin "65") (pinfunction "B16_L11_P_65") (pintype "passive"))
      (node (ref "R1365") (pin "1") (pinfunction "1_1") (pintype "passive"))
    )
    (net (code "31") (name "FPGA_B16_L16_N") (class "Default")
      (node (ref "JB1") (pin "37") (pinfunction "B16_L16_N_37") (pintype "passive"))
      (node (ref "R1352") (pin "1") (pinfunction "1_1") (pintype "passive"))
    )
    (net (code "32") (name "FPGA_B16_L16_P") (class "Default")
      (node (ref "JB1") (pin "35") (pinfunction "B16_L16_P_35") (pintype "passive"))
      (node (ref "R1351") (pin "1") (pinfunction "1_1") (pintype "passive"))
    )
    (net (code "33") (name "FPGA_B16_L17_N") (class "Default")
      (node (ref "JB1") (pin "45") (pinfunction "B16_L17_N_45") (pintype "passive"))
      (node (ref "R1356") (pin "1") (pinfunction "1_1") (pintype "passive"))
    )
    (net (code "34") (name "FPGA_B16_L17_P") (class "Default")
      (node (ref "JB1") (pin "47") (pinfunction "B16_L17_P_47") (pintype "passive"))
      (node (ref "R1355") (pin "1") (pinfunction "1_1") (pintype "passive"))
    )
    (net (code "35") (name "FPGA_B16_L18_N") (class "Default")
      (node (ref "JB1") (pin "49") (pinfunction "B16_L18_N_49") (pintype "passive"))
      (node (ref "R1358") (pin "1") (pinfunction "1_1") (pintype "passive"))
    )
    (net (code "36") (name "FPGA_B16_L18_P") (class "Default")
      (node (ref "JB1") (pin "51") (pinfunction "B16_L18_P_51") (pintype "passive"))
      (node (ref "R1357") (pin "1") (pinfunction "1_1") (pintype "passive"))
    )
    (net (code "37") (name "FPGA_B16_L19_N") (class "Default")
      (node (ref "JB1") (pin "39") (pinfunction "B16_L19_N_39") (pintype "passive"))
      (node (ref "R1354") (pin "1") (pinfunction "1_1") (pintype "passive"))
    )
    (net (code "38") (name "FPGA_B16_L19_P") (class "Default")
      (node (ref "JB1") (pin "41") (pinfunction "B16_L19_P_41") (pintype "passive"))
      (node (ref "R1353") (pin "1") (pinfunction "1_1") (pintype "passive"))
    )
    (net (code "39") (name "FPGA_ETH_DA_G") (class "Default")
      (node (ref "JB2") (pin "18") (pinfunction "B14_L17_P_18") (pintype "passive"))
      (node (ref "R1422") (pin "1") (pinfunction "1_1") (pintype "passive"))
    )
    (net (code "40") (name "FPGA_ETH_DA_Y") (class "Default")
      (node (ref "JB2") (pin "16") (pinfunction "B14_L17_N_16") (pintype "passive"))
      (node (ref "R1421") (pin "1") (pinfunction "1_1") (pintype "passive"))
    )
    (net (code "41") (name "FPGA_ETH_RD_N") (class "Default")
      (node (ref "J1411") (pin "8") (pinfunction "8_8") (pintype "passive"))
      (node (ref "JB1") (pin "11") (pinfunction "ETH_RD_N_11") (pintype "input"))
    )
    (net (code "42") (name "FPGA_ETH_RD_P") (class "Default")
      (node (ref "J1411") (pin "7") (pinfunction "7_7") (pintype "passive"))
      (node (ref "JB1") (pin "9") (pinfunction "ETH_RD_P_9") (pintype "input"))
    )
    (net (code "43") (name "FPGA_ETH_TD_N") (class "Default")
      (node (ref "J1411") (pin "4") (pinfunction "4_4") (pintype "passive"))
      (node (ref "JB1") (pin "5") (pinfunction "ETH_TD_N_5") (pintype "output"))
    )
    (net (code "44") (name "FPGA_ETH_TD_P") (class "Default")
      (node (ref "J1411") (pin "3") (pinfunction "3_3") (pintype "passive"))
      (node (ref "JB1") (pin "3") (pinfunction "ETH_TD_P_3") (pintype "output"))
    )
    (net (code "45") (name "FPGA_FT_12MHZ") (class "Default")
      (node (ref "JB2") (pin "99") (pinfunction "B15_IO25_99") (pintype "passive"))
      (node (ref "R0941") (pin "1") (pinfunction "1_1") (pintype "passive"))
    )
    (net (code "46") (name "FPGA_FT_CTSN") (class "Default")
      (node (ref "JB2") (pin "87") (pinfunction "B15_L21_N_87") (pintype "passive"))
      (node (ref "R0964") (pin "2") (pinfunction "2_2") (pintype "passive"))
    )
    (net (code "47") (name "FPGA_FT_DCDN") (class "Default")
      (node (ref "JB2") (pin "95") (pinfunction "B15_L22_N_95") (pintype "passive"))
      (node (ref "R0967") (pin "2") (pinfunction "2_2") (pintype "passive"))
    )
    (net (code "48") (name "FPGA_FT_DSRN") (class "Default")
      (node (ref "JB2") (pin "93") (pinfunction "B15_L24_P_93") (pintype "passive"))
      (node (ref "R0966") (pin "2") (pinfunction "2_2") (pintype "passive"))
    )
    (net (code "49") (name "FPGA_FT_DTRN") (class "Default")
      (node (ref "JB2") (pin "91") (pinfunction "B15_L24_N_91") (pintype "passive"))
      (node (ref "R0965") (pin "2") (pinfunction "2_2") (pintype "passive"))
    )
    (net (code "50") (name "FPGA_FT_RESETN") (class "Default")
      (node (ref "JB2") (pin "77") (pinfunction "B15_L15_N_77") (pintype "passive"))
      (node (ref "R0912") (pin "1") (pinfunction "1_1") (pintype "passive"))
    )
    (net (code "51") (name "FPGA_FT_RIN") (class "Default")
      (node (ref "JB2") (pin "97") (pinfunction "B15_L22_P_97") (pintype "passive"))
      (node (ref "R0968") (pin "2") (pinfunction "2_2") (pintype "passive"))
    )
    (net (code "52") (name "FPGA_FT_RTSN") (class "Default")
      (node (ref "JB2") (pin "85") (pinfunction "B15_L21_P_85") (pintype "passive"))
      (node (ref "R0963") (pin "2") (pinfunction "2_2") (pintype "passive"))
    )
    (net (code "53") (name "FPGA_JTAGEN") (class "Default")
      (node (ref "JB1") (pin "90") (pinfunction "JTAGEN_90") (pintype "input"))
      (node (ref "R1339") (pin "2") (pinfunction "2_2") (pintype "passive"))
    )
    (net (code "54") (name "FPGA_LCD_BL_PWM") (class "Default")
      (node (ref "JB1") (pin "96") (pinfunction "B14_L4_MIO_P_96") (pintype "passive"))
      (node (ref "R0552") (pin "2") (pinfunction "2_2") (pintype "passive"))
    )
    (net (code "55") (name "FPGA_LED_RGB_BLUE") (class "Default")
      (node (ref "JB1") (pin "100") (pinfunction "B14_L24_MIO_N_100") (pintype "passive"))
      (node (ref "R1023") (pin "2") (pinfunction "2_2") (pintype "passive"))
    )
    (net (code "56") (name "FPGA_LED_RGB_GREEN") (class "Default")
      (node (ref "JB1") (pin "94") (pinfunction "B14_L9_MIO_N_94") (pintype "passive"))
      (node (ref "R1022") (pin "2") (pinfunction "2_2") (pintype "passive"))
    )
    (net (code "57") (name "FPGA_LED_RGB_RED") (class "Default")
      (node (ref "JB1") (pin "92") (pinfunction "B14_L9_MIO_P_92") (pintype "passive"))
      (node (ref "R1021") (pin "2") (pinfunction "2_2") (pintype "passive"))
    )
    (net (code "58") (name "FPGA_RESET") (class "Default")
      (node (ref "C1321") (pin "2") (pinfunction "2_2") (pintype "passive"))
      (node (ref "JB3") (pin "43") (pinfunction "B13_L1_N_43") (pintype "passive"))
      (node (ref "R1321") (pin "1") (pinfunction "1_1") (pintype "passive"))
    )
    (net (code "59") (name "FPGA_RFX_DET") (class "Default")
      (node (ref "R0821") (pin "2") (pinfunction "2_2") (pintype "passive"))
      (node (ref "TP_RFX_DET") (pin "TP") (pinfunction "TP_TP") (pintype "input"))
    )
    (net (code "60") (name "FPGA_RFX_MODE") (class "Default")
      (node (ref "JB2") (pin "75") (pinfunction "B15_L15_P_75") (pintype "passive"))
      (node (ref "R0861") (pin "1") (pinfunction "1_1") (pintype "passive"))
    )
    (net (code "61") (name "FPGA_SRST") (class "Default")
      (node (ref "JB2") (pin "90") (pinfunction "B15_IO0_90") (pintype "passive"))
      (node (ref "R1337") (pin "2") (pinfunction "2_2") (pintype "passive"))
    )
    (net (code "62") (name "FPGA_TCK") (class "Default")
      (node (ref "JB2") (pin "100") (pinfunction "TCK_100") (pintype "input"))
      (node (ref "R1333") (pin "2") (pinfunction "2_2") (pintype "passive"))
    )
    (net (code "63") (name "FPGA_TDI") (class "Default")
      (node (ref "JB2") (pin "96") (pinfunction "TDI_96") (pintype "input"))
      (node (ref "R1335") (pin "2") (pinfunction "2_2") (pintype "passive"))
    )
    (net (code "64") (name "FPGA_TDO") (class "Default")
      (node (ref "JB2") (pin "98") (pinfunction "TDO_98") (pintype "output"))
      (node (ref "R1334") (pin "2") (pinfunction "2_2") (pintype "passive"))
    )
    (net (code "65") (name "FPGA_TMS") (class "Default")
      (node (ref "JB2") (pin "94") (pinfunction "TMS_94") (pintype "input"))
      (node (ref "R1332") (pin "2") (pinfunction "2_2") (pintype "passive"))
    )
    (net (code "66") (name "FPGA_UART0_RXD") (class "Default")
      (node (ref "JB1") (pin "91") (pinfunction "B14_L24_MIO_P_91") (pintype "passive"))
      (node (ref "R0961") (pin "2") (pinfunction "2_2") (pintype "passive"))
    )
    (net (code "67") (name "FPGA_UART0_TXD") (class "Default")
      (node (ref "JB1") (pin "86") (pinfunction "B14_L18_MIO_N_86") (pintype "passive"))
      (node (ref "R0962") (pin "2") (pinfunction "2_2") (pintype "passive"))
    )
    (net (code "68") (name "FT_TXDEN") (class "Default")
      (node (ref "TP_TXDEN") (pin "TP") (pinfunction "TP_TP") (pintype "input"))
      (node (ref "U0911") (pin "21") (pinfunction "ACBUS0_21") (pintype "output"))
    )
    (net (code "69") (name "GND") (class "Default")
      (node (ref "C0501") (pin "2") (pinfunction "2_2") (pintype "passive"))
      (node (ref "C0512") (pin "2") (pinfunction "2_2") (pintype "passive"))
      (node (ref "C0611") (pin "2") (pinfunction "2_2") (pintype "passive"))
      (node (ref "C0612") (pin "2") (pinfunction "2_2") (pintype "passive"))
      (node (ref "C0621") (pin "2") (pinfunction "2_2") (pintype "passive"))
      (node (ref "C0701") (pin "2") (pinfunction "2_2") (pintype "passive"))
      (node (ref "C0711") (pin "2") (pinfunction "2_2") (pintype "passive"))
      (node (ref "C0713") (pin "1") (pinfunction "1_1") (pintype "passive"))
      (node (ref "C0811") (pin "2") (pinfunction "2_2") (pintype "passive"))
      (node (ref "C0851") (pin "2") (pinfunction "2_2") (pintype "passive"))
      (node (ref "C0852") (pin "2") (pinfunction "2_2") (pintype "passive"))
      (node (ref "C0853") (pin "2") (pinfunction "2_2") (pintype "passive"))
      (node (ref "C0891") (pin "2") (pinfunction "2_2") (pintype "passive"))
      (node (ref "C0893") (pin "2") (pinfunction "2_2") (pintype "passive"))
      (node (ref "C0895") (pin "2") (pinfunction "2_2") (pintype "passive"))
      (node (ref "C0897") (pin "2") (pinfunction "2_2") (pintype "passive"))
      (node (ref "C0911") (pin "2") (pinfunction "2_2") (pintype "passive"))
      (node (ref "C0912") (pin "1") (pinfunction "1_1") (pintype "passive"))
      (node (ref "C0913") (pin "1") (pinfunction "1_1") (pintype "passive"))
      (node (ref "C0921") (pin "1") (pinfunction "1_1") (pintype "passive"))
      (node (ref "C0922") (pin "1") (pinfunction "1_1") (pintype "passive"))
      (node (ref "C1011") (pin "2") (pinfunction "2_2") (pintype "passive"))
      (node (ref "C1012") (pin "2") (pinfunction "2_2") (pintype "passive"))
      (node (ref "C1013") (pin "2") (pinfunction "2_2") (pintype "passive"))
      (node (ref "C1101") (pin "1") (pinfunction "1_1") (pintype "passive"))
      (node (ref "C1102") (pin "1") (pinfunction "1_1") (pintype "passive"))
      (node (ref "C1111") (pin "1") (pinfunction "1_1") (pintype "passive"))
      (node (ref "C1112") (pin "1") (pinfunction "1_1") (pintype "passive"))
      (node (ref "C1113") (pin "1") (pinfunction "1_1") (pintype "passive"))
      (node (ref "C1114") (pin "1") (pinfunction "1_1") (pintype "passive"))
      (node (ref "C1122") (pin "2") (pinfunction "2_2") (pintype "passive"))
      (node (ref "C1151") (pin "2") (pinfunction "2_2") (pintype "passive"))
      (node (ref "C1152") (pin "2") (pinfunction "2_2") (pintype "passive"))
      (node (ref "C1153") (pin "2") (pinfunction "2_2") (pintype "passive"))
      (node (ref "C1201") (pin "2") (pinfunction "2_2") (pintype "passive"))
      (node (ref "C1221") (pin "2") (pinfunction "2_2") (pintype "passive"))
      (node (ref "C1311") (pin "1") (pinfunction "1_1") (pintype "passive"))
      (node (ref "C1321") (pin "1") (pinfunction "1_1") (pintype "passive"))
      (node (ref "C1381") (pin "1") (pinfunction "1_1") (pintype "passive"))
      (node (ref "C1431") (pin "2") (pinfunction "2_2") (pintype "passive"))
      (node (ref "C1432") (pin "2") (pinfunction "2_2") (pintype "passive"))
      (node (ref "C1441") (pin "2") (pinfunction "2_2") (pintype "passive"))
      (node (ref "C1442") (pin "2") (pinfunction "2_2") (pintype "passive"))
      (node (ref "D1021") (pin "1") (pinfunction "BC_1") (pintype "passive"))
      (node (ref "D1021") (pin "2") (pinfunction "GC_2") (pintype "passive"))
      (node (ref "D1021") (pin "3") (pinfunction "RC_3") (pintype "passive"))
      (node (ref "H1511") (pin "B3,2") (pinfunction "MOUNT_B3,2") (pintype "passive"))
      (node (ref "H1512") (pin "B3,2") (pinfunction "MOUNT_B3,2") (pintype "passive"))
      (node (ref "H1513") (pin "B3,2") (pinfunction "MOUNT_B3,2") (pintype "passive"))
      (node (ref "H1514") (pin "B3,2") (pinfunction "MOUNT_B3,2") (pintype "passive"))
      (node (ref "HB_351") (pin "B3,2") (pinfunction "MOUNT_B3,2") (pintype "passive"))
      (node (ref "HB_352") (pin "B3,2") (pinfunction "MOUNT_B3,2") (pintype "passive"))
      (node (ref "HB_353") (pin "B3,2") (pinfunction "MOUNT_B3,2") (pintype "passive"))
      (node (ref "HB_354") (pin "B3,2") (pinfunction "MOUNT_B3,2") (pintype "passive"))
      (node (ref "J1411") (pin "10") (pinfunction "10_10") (pintype "passive"))
      (node (ref "J1411") (pin "11") (pinfunction "11_11") (pintype "passive"))
      (node (ref "J1411") (pin "2") (pinfunction "2_2") (pintype "passive"))
      (node (ref "J1411") (pin "GND@11") (pinfunction "13_GND@11") (pintype "passive"))
      (node (ref "J1411") (pin "GND@12") (pinfunction "13_GND@12") (pintype "passive"))
      (node (ref "J1411") (pin "GND@21") (pinfunction "13_GND@21") (pintype "passive"))
      (node (ref "J1411") (pin "GND@22") (pinfunction "13_GND@22") (pintype "passive"))
      (node (ref "JB1") (pin "1") (pinfunction "GND_1") (pintype "passive"))
      (node (ref "JB1") (pin "19") (pinfunction "GND_19") (pintype "passive"))
      (node (ref "JB1") (pin "25") (pinfunction "GND_25") (pintype "passive"))
      (node (ref "JB1") (pin "30") (pinfunction "GND_30") (pintype "passive"))
      (node (ref "JB1") (pin "33") (pinfunction "GND_33") (pintype "passive"))
      (node (ref "JB1") (pin "43") (pinfunction "GND_43") (pintype "passive"))
      (node (ref "JB1") (pin "53") (pinfunction "GND_53") (pintype "passive"))
      (node (ref "JB1") (pin "54") (pinfunction "GND_54") (pintype "passive"))
      (node (ref "JB1") (pin "63") (pinfunction "GND_63") (pintype "passive"))
      (node (ref "JB1") (pin "64") (pinfunction "GND_64") (pintype "passive"))
      (node (ref "JB1") (pin "7") (pinfunction "GND_7") (pintype "passive"))
      (node (ref "JB1") (pin "73") (pinfunction "GND_73") (pintype "passive"))
      (node (ref "JB1") (pin "74") (pinfunction "GND_74") (pintype "passive"))
      (node (ref "JB1") (pin "83") (pinfunction "GND_83") (pintype "passive"))
      (node (ref "JB1") (pin "89") (pinfunction "GND_89") (pintype "passive"))
      (node (ref "JB1") (pin "F1") (pinfunction "F1_F1") (pintype "passive"))
      (node (ref "JB1") (pin "F2") (pinfunction "F2_F2") (pintype "passive"))
      (node (ref "JB2") (pin "19") (pinfunction "GND_19") (pintype "passive"))
      (node (ref "JB2") (pin "29") (pinfunction "GND_29") (pintype "passive"))
      (node (ref "JB2") (pin "39") (pinfunction "GND_39") (pintype "passive"))
      (node (ref "JB2") (pin "40") (pinfunction "GND_40") (pintype "passive"))
      (node (ref "JB2") (pin "49") (pinfunction "GND_49") (pintype "passive"))
      (node (ref "JB2") (pin "50") (pinfunction "GND_50") (pintype "passive"))
      (node (ref "JB2") (pin "59") (pinfunction "GND_59") (pintype "passive"))
      (node (ref "JB2") (pin "60") (pinfunction "GND_60") (pintype "passive"))
      (node (ref "JB2") (pin "69") (pinfunction "GND_69") (pintype "passive"))
      (node (ref "JB2") (pin "70") (pinfunction "GND_70") (pintype "passive"))
      (node (ref "JB2") (pin "79") (pinfunction "GND_79") (pintype "passive"))
      (node (ref "JB2") (pin "80") (pinfunction "GND_80") (pintype "passive"))
      (node (ref "JB2") (pin "89") (pinfunction "GND_89") (pintype "passive"))
      (node (ref "JB2") (pin "F1") (pinfunction "F1_F1") (pintype "passive"))
      (node (ref "JB2") (pin "F2") (pinfunction "F2_F2") (pintype "passive"))
      (node (ref "JB3") (pin "11") (pinfunction "GND_11") (pintype "passive"))
      (node (ref "JB3") (pin "17") (pinfunction "GND_17") (pintype "passive"))
      (node (ref "JB3") (pin "18") (pinfunction "GND_18") (pintype "passive"))
      (node (ref "JB3") (pin "23") (pinfunction "GND_23") (pintype "passive"))
      (node (ref "JB3") (pin "24") (pinfunction "GND_24") (pintype "passive"))
      (node (ref "JB3") (pin "29") (pinfunction "GND_29") (pintype "passive"))
      (node (ref "JB3") (pin "30") (pinfunction "GND_30") (pintype "passive"))
      (node (ref "JB3") (pin "35") (pinfunction "GND_35") (pintype "passive"))
      (node (ref "JB3") (pin "36") (pinfunction "GND_36") (pintype "passive"))
      (node (ref "JB3") (pin "45") (pinfunction "GND_45") (pintype "passive"))
      (node (ref "JB3") (pin "46") (pinfunction "GND_46") (pintype "passive"))
      (node (ref "JB3") (pin "5") (pinfunction "GND_5") (pintype "passive"))
      (node (ref "JB3") (pin "6") (pinfunction "GND_6") (pintype "passive"))
      (node (ref "JB3") (pin "F1") (pinfunction "F1_F1") (pintype "passive"))
      (node (ref "JB3") (pin "F2") (pinfunction "F2_F2") (pintype "passive"))
      (node (ref "L0701") (pin "1") (pinfunction "1_1") (pintype "passive"))
      (node (ref "L0702") (pin "1") (pinfunction "1_1") (pintype "passive"))
      (node (ref "L0721") (pin "1") (pinfunction "COM_1") (pintype "passive"))
      (node (ref "L0722") (pin "2") (pinfunction "COM_2") (pintype "passive"))
      (node (ref "L0722") (pin "5") (pinfunction "G_N_D_5") (pintype "passive"))
      (node (ref "L0821") (pin "2") (pinfunction "2_2") (pintype "passive"))
      (node (ref "L0911") (pin "1") (pinfunction "1_1") (pintype "passive"))
      (node (ref "R0531") (pin "1") (pinfunction "1_1") (pintype "passive"))
      (node (ref "R0551") (pin "1") (pinfunction "1_1") (pintype "passive"))
      (node (ref "R0553") (pin "1") (pinfunction "1_1") (pintype "passive"))
      (node (ref "R0822") (pin "1") (pinfunction "1_1") (pintype "passive"))
      (node (ref "R0911") (pin "1") (pinfunction "1_1") (pintype "passive"))
      (node (ref "R0913") (pin "1") (pinfunction "1_1") (pintype "passive"))
      (node (ref "R1101") (pin "1") (pinfunction "1_1") (pintype "passive"))
      (node (ref "R1103") (pin "1") (pinfunction "1_1") (pintype "passive"))
      (node (ref "R1105") (pin "1") (pinfunction "1_1") (pintype "passive"))
      (node (ref "R1106") (pin "1") (pinfunction "1_1") (pintype "passive"))
      (node (ref "R1311") (pin "1") (pinfunction "1_1") (pintype "passive"))
      (node (ref "R1338") (pin "2") (pinfunction "2_2") (pintype "passive"))
      (node (ref "U0501") (pin "5") (pinfunction "VSS_5") (pintype "power_in"))
      (node (ref "U0601") (pin "2") (pinfunction "ADDR_2") (pintype "input"))
      (node (ref "U0601") (pin "8") (pinfunction "GND_8") (pintype "passive"))
      (node (ref "U0711") (pin "2") (pinfunction "GND_2") (pintype "power_in"))
      (node (ref "U0811") (pin "2") (pinfunction "GND_2") (pintype "power_in"))
      (node (ref "U0821") (pin "17") (pinfunction "VSS_17") (pintype "passive"))
      (node (ref "U0821") (pin "4") (pinfunction "VSS_4") (pintype "passive"))
      (node (ref "U0821") (pin "8") (pinfunction "VSS_8") (pintype "passive"))
      (node (ref "U0881") (pin "1") (pinfunction "GROUND_1") (pintype "passive"))
      (node (ref "U0881") (pin "3") (pinfunction "GROUND_3") (pintype "passive"))
      (node (ref "U0881") (pin "4") (pinfunction "GROUND_4") (pintype "passive"))
      (node (ref "U0881") (pin "6") (pinfunction "GROUND_6") (pintype "passive"))
      (node (ref "U0911") (pin "10") (pinfunction "GND_10") (pintype "passive"))
      (node (ref "U0911") (pin "11") (pinfunction "GND_11") (pintype "passive"))
      (node (ref "U0911") (pin "22") (pinfunction "GND_22") (pintype "passive"))
      (node (ref "U0911") (pin "23") (pinfunction "GND_23") (pintype "passive"))
      (node (ref "U0911") (pin "35") (pinfunction "GND_35") (pintype "passive"))
      (node (ref "U0911") (pin "36") (pinfunction "GND_36") (pintype "passive"))
      (node (ref "U0911") (pin "42") (pinfunction "TEST_42") (pintype "input"))
      (node (ref "U0911") (pin "47") (pinfunction "GND_47") (pintype "passive"))
      (node (ref "U0911") (pin "48") (pinfunction "GND_48") (pintype "passive"))
      (node (ref "U1101") (pin "23") (pinfunction "VSS_PAD_23") (pintype "passive"))
      (node (ref "U1101") (pin "24") (pinfunction "VSS_PAD_24") (pintype "passive"))
      (node (ref "U1101") (pin "P$1") (pinfunction "VSS_PAD_P$1") (pintype "passive"))
      (node (ref "U1101") (pin "P$10") (pinfunction "VSS_PAD_P$10") (pintype "passive"))
      (node (ref "U1101") (pin "P$11") (pinfunction "VSS_PAD_P$11") (pintype "passive"))
      (node (ref "U1101") (pin "P$12") (pinfunction "VSS_PAD_P$12") (pintype "passive"))
      (node (ref "U1101") (pin "P$13") (pinfunction "VSS_PAD_P$13") (pintype "passive"))
      (node (ref "U1101") (pin "P$14") (pinfunction "VSS_PAD_P$14") (pintype "passive"))
      (node (ref "U1101") (pin "P$15") (pinfunction "VSS_PAD_P$15") (pintype "passive"))
      (node (ref "U1101") (pin "P$16") (pinfunction "VSS_PAD_P$16") (pintype "passive"))
      (node (ref "U1101") (pin "P$17") (pinfunction "VSS_PAD_P$17") (pintype "passive"))
      (node (ref "U1101") (pin "P$18") (pinfunction "VSS_PAD_P$18") (pintype "passive"))
      (node (ref "U1101") (pin "P$19") (pinfunction "VSS_PAD_P$19") (pintype "passive"))
      (node (ref "U1101") (pin "P$2") (pinfunction "VSS_PAD_P$2") (pintype "passive"))
      (node (ref "U1101") (pin "P$20") (pinfunction "VSS_PAD_P$20") (pintype "passive"))
      (node (ref "U1101") (pin "P$21") (pinfunction "VSS_PAD_P$21") (pintype "passive"))
      (node (ref "U1101") (pin "P$3") (pinfunction "VSS_PAD_P$3") (pintype "passive"))
      (node (ref "U1101") (pin "P$4") (pinfunction "VSS_PAD_P$4") (pintype "passive"))
      (node (ref "U1101") (pin "P$5") (pinfunction "VSS_PAD_P$5") (pintype "passive"))
      (node (ref "U1101") (pin "P$6") (pinfunction "VSS_PAD_P$6") (pintype "passive"))
      (node (ref "U1101") (pin "P$7") (pinfunction "VSS_PAD_P$7") (pintype "passive"))
      (node (ref "U1101") (pin "P$8") (pinfunction "VSS_PAD_P$8") (pintype "passive"))
      (node (ref "U1101") (pin "P$9") (pinfunction "VSS_PAD_P$9") (pintype "passive"))
      (node (ref "U1211") (pin "13") (pinfunction "VSS_13") (pintype "passive"))
      (node (ref "U1211") (pin "14") (pinfunction "VSS_14") (pintype "passive"))
      (node (ref "U1211") (pin "3") (pinfunction "VSS_3") (pintype "passive"))
      (node (ref "U1211") (pin "4") (pinfunction "EN_VIN_SW_4") (pintype "input"))
      (node (ref "U1211") (pin "8") (pinfunction "VSEL4_8") (pintype "input"))
      (node (ref "U1211") (pin "G1") (pinfunction "VSS_G1") (pintype "passive"))
      (node (ref "U1211") (pin "G2") (pinfunction "VSS_G2") (pintype "passive"))
      (node (ref "U1211") (pin "G3") (pinfunction "VSS_G3") (pintype "passive"))
      (node (ref "X0891") (pin "GND1") (pinfunction "GND_GND1") (pintype "bidirectional"))
      (node (ref "X0891") (pin "GND2") (pinfunction "GND_GND2") (pintype "bidirectional"))
      (node (ref "X0891") (pin "GND3") (pinfunction "GND_GND3") (pintype "bidirectional"))
      (node (ref "X0891") (pin "GND4") (pinfunction "GND_GND4") (pintype "bidirectional"))
      (node (ref "X0895") (pin "GND1") (pinfunction "GND_GND1") (pintype "bidirectional"))
      (node (ref "X0895") (pin "GND2") (pinfunction "GND_GND2") (pintype "bidirectional"))
      (node (ref "X0895") (pin "GND3") (pinfunction "GND_GND3") (pintype "bidirectional"))
      (node (ref "X0895") (pin "GND4") (pinfunction "GND_GND4") (pintype "bidirectional"))
      (node (ref "X1011") (pin "C") (pinfunction "C_C") (pintype "passive"))
      (node (ref "X1011") (pin "D") (pinfunction "D_D") (pintype "passive"))
      (node (ref "X1311") (pin "GND") (pinfunction "GND_GND") (pintype "passive"))
      (node (ref "X1331") (pin "1") (pinfunction "1_1") (pintype "passive"))
      (node (ref "X1331") (pin "11") (pinfunction "11_11") (pintype "passive"))
      (node (ref "X1331") (pin "13") (pinfunction "13_13") (pintype "passive"))
      (node (ref "X1331") (pin "3") (pinfunction "3_3") (pintype "passive"))
      (node (ref "X1331") (pin "5") (pinfunction "5_5") (pintype "passive"))
      (node (ref "X1331") (pin "7") (pinfunction "7_7") (pintype "passive"))
      (node (ref "X1331") (pin "9") (pinfunction "9_9") (pintype "passive"))
      (node (ref "X1361") (pin "8") (pinfunction "8_8") (pintype "passive"))
    )
    (net (code "70") (name "LCD_BL_B") (class "Default")
      (node (ref "R0551") (pin "2") (pinfunction "2_2") (pintype "passive"))
      (node (ref "R0552") (pin "1") (pinfunction "1_1") (pintype "passive"))
      (node (ref "T0551") (pin "1") (pinfunction "B_1") (pintype "passive"))
    )
    (net (code "71") (name "LCD_NRST") (class "Default")
      (node (ref "R0531") (pin "2") (pinfunction "2_2") (pintype "passive"))
      (node (ref "R0532") (pin "2") (pinfunction "2_2") (pintype "passive"))
      (node (ref "U0501") (pin "8") (pinfunction "RST_8") (pintype "input"))
    )
    (net (code "72") (name "Net-(C0703-Pad1)") (class "Default")
      (node (ref "C0703") (pin "1") (pinfunction "1_1") (pintype "passive"))
      (node (ref "L0703") (pin "2") (pinfunction "2_2") (pintype "passive"))
      (node (ref "U0701") (pin "21") (pinfunction "DEVDD_21") (pintype "power_in"))
      (node (ref "U0701") (pin "29") (pinfunction "DEVDD_29") (pintype "power_in"))
      (node (ref "U0701") (pin "39") (pinfunction "DEVDD_39") (pintype "power_in"))
    )
    (net (code "73") (name "Net-(C0703-Pad2)") (class "Default")
      (node (ref "C0703") (pin "2") (pinfunction "2_2") (pintype "passive"))
      (node (ref "C0706") (pin "1") (pinfunction "1_1") (pintype "passive"))
      (node (ref "L0702") (pin "2") (pinfunction "2_2") (pintype "passive"))
      (node (ref "U0701") (pin "20") (pinfunction "DVSS_20") (pintype "passive"))
      (node (ref "U0701") (pin "23") (pinfunction "DVSS_23") (pintype "passive"))
      (node (ref "U0701") (pin "24") (pinfunction "DVSS_24") (pintype "passive"))
      (node (ref "U0701") (pin "32") (pinfunction "DVSS_32") (pintype "passive"))
      (node (ref "U0701") (pin "38") (pinfunction "DVSS_38") (pintype "passive"))
    )
    (net (code "74") (name "Net-(C0704-Pad1)") (class "Default")
      (node (ref "C0704") (pin "1") (pinfunction "1_1") (pintype "passive"))
      (node (ref "L0704") (pin "2") (pinfunction "2_2") (pintype "passive"))
      (node (ref "U0701") (pin "15") (pinfunction "EVDD_15") (pintype "power_in"))
      (node (ref "U0701") (pin "46") (pinfunction "EVDD_46") (pintype "power_in"))
    )
    (net (code "75") (name "Net-(C0891-Pad1)") (class "Default")
      (node (ref "C0891") (pin "1") (pinfunction "1_1") (pintype "passive"))
      (node (ref "L0892") (pin "2") (pinfunction "2_2") (pintype "passive"))
      (node (ref "X0891") (pin "ANT1") (pinfunction "SIGNAL_ANT1") (pintype "bidirectional"))
      (node (ref "X0891") (pin "ANT2") (pinfunction "SIGNAL_ANT2") (pintype "bidirectional"))
      (node (ref "X0891") (pin "ANT3") (pinfunction "SIGNAL_ANT3") (pintype "bidirectional"))
    )
    (net (code "76") (name "Net-(C0895-Pad1)") (class "Default")
      (node (ref "C0895") (pin "1") (pinfunction "1_1") (pintype "passive"))
      (node (ref "L0896") (pin "2") (pinfunction "2_2") (pintype "passive"))
      (node (ref "X0895") (pin "ANT1") (pinfunction "SIGNAL_ANT1") (pintype "bidirectional"))
      (node (ref "X0895") (pin "ANT2") (pinfunction "SIGNAL_ANT2") (pintype "bidirectional"))
      (node (ref "X0895") (pin "ANT3") (pinfunction "SIGNAL_ANT3") (pintype "bidirectional"))
    )
    (net (code "77") (name "Net-(C1011-Pad1)") (class "Default")
      (node (ref "C1011") (pin "1") (pinfunction "1_1") (pintype "passive"))
      (node (ref "R1011") (pin "1") (pinfunction "1_1") (pintype "passive"))
      (node (ref "X1011") (pin "A") (pinfunction "A_A") (pintype "passive"))
    )
    (net (code "78") (name "Net-(C1012-Pad1)") (class "Default")
      (node (ref "C1012") (pin "1") (pinfunction "1_1") (pintype "passive"))
      (node (ref "R1012") (pin "1") (pinfunction "1_1") (pintype "passive"))
      (node (ref "X1011") (pin "B") (pinfunction "B_B") (pintype "passive"))
    )
    (net (code "79") (name "Net-(C1013-Pad1)") (class "Default")
      (node (ref "C1013") (pin "1") (pinfunction "1_1") (pintype "passive"))
      (node (ref "R1013") (pin "1") (pinfunction "1_1") (pintype "passive"))
      (node (ref "X1011") (pin "E") (pinfunction "E_E") (pintype "passive"))
    )
    (net (code "80") (name "Net-(C1108-Pad1)") (class "Default")
      (node (ref "C1108") (pin "1") (pinfunction "1_1") (pintype "passive"))
      (node (ref "L1101") (pin "2") (pinfunction "2_2") (pintype "passive"))
      (node (ref "R1122") (pin "2") (pinfunction "2_2") (pintype "passive"))
      (node (ref "R1131") (pin "1") (pinfunction "1_1") (pintype "passive"))
      (node (ref "U1101") (pin "10") (pinfunction "LL_10") (pintype "passive"))
      (node (ref "U1101") (pin "11") (pinfunction "LL_11") (pintype "passive"))
      (node (ref "U1101") (pin "6") (pinfunction "LL_6") (pintype "passive"))
      (node (ref "U1101") (pin "7") (pinfunction "LL_7") (pintype "passive"))
      (node (ref "U1101") (pin "8") (pinfunction "LL_8") (pintype "passive"))
      (node (ref "U1101") (pin "9") (pinfunction "LL_9") (pintype "passive"))
    )
    (net (code "81") (name "Net-(C1108-Pad2)") (class "Default")
      (node (ref "C1108") (pin "2") (pinfunction "2_2") (pintype "passive"))
      (node (ref "R1108") (pin "2") (pinfunction "2_2") (pintype "passive"))
    )
    (net (code "82") (name "Net-(C1122-Pad1)") (class "Default")
      (node (ref "C1122") (pin "1") (pinfunction "1_1") (pintype "passive"))
      (node (ref "R1122") (pin "1") (pinfunction "1_1") (pintype "passive"))
    )
    (net (code "83") (name "Net-(C1131-Pad2)") (class "Default")
      (node (ref "C1131") (pin "2") (pinfunction "2_2") (pintype "passive"))
      (node (ref "C1132") (pin "1") (pinfunction "1_1") (pintype "passive"))
      (node (ref "R1131") (pin "2") (pinfunction "2_2") (pintype "passive"))
    )
    (net (code "84") (name "Net-(C1311-Pad2)") (class "Default")
      (node (ref "C1311") (pin "2") (pinfunction "2_2") (pintype "passive"))
      (node (ref "R1311") (pin "2") (pinfunction "2_2") (pintype "passive"))
      (node (ref "X1311") (pin "JSHIELD") (pinfunction "SHIELD_JSHIELD") (pintype "passive"))
      (node (ref "X1311") (pin "JSHIELD@2") (pinfunction "SHIELD_JSHIELD@2") (pintype "passive"))
      (node (ref "X1311") (pin "JSHIELD@3") (pinfunction "SHIELD_JSHIELD@3") (pintype "passive"))
      (node (ref "X1311") (pin "JSHIELD@4") (pinfunction "SHIELD_JSHIELD@4") (pintype "passive"))
      (node (ref "X1311") (pin "JSHIELD@5") (pinfunction "SHIELD_JSHIELD@5") (pintype "passive"))
      (node (ref "X1311") (pin "JSHIELD@6") (pinfunction "SHIELD_JSHIELD@6") (pintype "passive"))
    )
    (net (code "85") (name "Net-(D0971-PadC)") (class "Default")
      (node (ref "D0971") (pin "C") (pinfunction "C_C") (pintype "passive"))
      (node (ref "R0971") (pin "2") (pinfunction "2_2") (pintype "passive"))
    )
    (net (code "86") (name "Net-(D0972-PadC)") (class "Default")
      (node (ref "D0972") (pin "C") (pinfunction "C_C") (pintype "passive"))
      (node (ref "R0972") (pin "2") (pinfunction "2_2") (pintype "passive"))
    )
    (net (code "87") (name "Net-(D1021-BA)") (class "Default")
      (node (ref "D1021") (pin "6") (pinfunction "BA_6") (pintype "passive"))
      (node (ref "R1023") (pin "1") (pinfunction "1_1") (pintype "passive"))
    )
    (net (code "88") (name "Net-(D1021-GA)") (class "Default")
      (node (ref "D1021") (pin "5") (pinfunction "GA_5") (pintype "passive"))
      (node (ref "R1022") (pin "1") (pinfunction "1_1") (pintype "passive"))
    )
    (net (code "89") (name "Net-(D1021-RA)") (class "Default")
      (node (ref "D1021") (pin "4") (pinfunction "RA_4") (pintype "passive"))
      (node (ref "R1021") (pin "1") (pinfunction "1_1") (pintype "passive"))
    )
    (net (code "90") (name "Net-(J1411-Pad1)") (class "Default")
      (node (ref "J1411") (pin "1") (pinfunction "1_1") (pintype "passive"))
      (node (ref "R1421") (pin "2") (pinfunction "2_2") (pintype "passive"))
    )
    (net (code "91") (name "Net-(J1411-Pad12)") (class "Default")
      (node (ref "J1411") (pin "12") (pinfunction "12_12") (pintype "passive"))
      (node (ref "R1422") (pin "2") (pinfunction "2_2") (pintype "passive"))
    )
    (net (code "92") (name "Net-(JB1-EN1)") (class "Default")
      (node (ref "FPGA_EN1") (pin "TP") (pinfunction "TP_TP") (pintype "input"))
      (node (ref "JB1") (pin "27") (pinfunction "EN1_27") (pintype "input"))
    )
    (net (code "93") (name "Net-(JB1-MODE)") (class "Default")
      (node (ref "FPGA_MODE") (pin "TP") (pinfunction "TP_TP") (pintype "input"))
      (node (ref "JB1") (pin "31") (pinfunction "MODE_31") (pintype "input"))
    )
    (net (code "94") (name "Net-(JB1-PGOOD)") (class "Default")
      (node (ref "JB1") (pin "29") (pinfunction "PGOOD_29") (pintype "output"))
      (node (ref "PGOOD") (pin "TP") (pinfunction "TP_TP") (pintype "input"))
    )
    (net (code "95") (name "Net-(JB2-RESIN)") (class "Default")
      (node (ref "JB2") (pin "17") (pinfunction "RESIN_17") (pintype "input"))
      (node (ref "R0203") (pin "1") (pinfunction "1_1") (pintype "passive"))
      (node (ref "TP_RESIN") (pin "TP") (pinfunction "TP_TP") (pintype "input"))
    )
    (net (code "96") (name "Net-(L0721-B1)") (class "Default")
      (node (ref "L0721") (pin "3") (pinfunction "B1_3") (pintype "passive"))
      (node (ref "U0701") (pin "8") (pinfunction "RF09P_8") (pintype "passive"))
    )
    (net (code "97") (name "Net-(L0721-B2)") (class "Default")
      (node (ref "L0721") (pin "2") (pinfunction "B2_2") (pintype "passive"))
      (node (ref "U0701") (pin "9") (pinfunction "RF09N_9") (pintype "passive"))
    )
    (net (code "98") (name "Net-(L0722-B1)") (class "Default")
      (node (ref "L0722") (pin "3") (pinfunction "B1_3") (pintype "passive"))
      (node (ref "U0701") (pin "4") (pinfunction "RF24P_4") (pintype "passive"))
    )
    (net (code "99") (name "Net-(L0722-B2)") (class "Default")
      (node (ref "L0722") (pin "4") (pinfunction "B2_4") (pintype "passive"))
      (node (ref "U0701") (pin "5") (pinfunction "RF24N_5") (pintype "passive"))
    )
    (net (code "100") (name "Net-(L0911-Pad2)") (class "Default")
      (node (ref "L0911") (pin "2") (pinfunction "2_2") (pintype "passive"))
      (node (ref "U0911") (pin "4") (pinfunction "AGND_4") (pintype "passive"))
      (node (ref "U0911") (pin "41") (pinfunction "AGND_41") (pintype "passive"))
      (node (ref "U0911") (pin "9") (pinfunction "AGND_9") (pintype "passive"))
    )
    (net (code "101") (name "Net-(R1331-Pad1)") (class "Default")
      (node (ref "R1331") (pin "1") (pinfunction "1_1") (pintype "passive"))
      (node (ref "X1331") (pin "2") (pinfunction "2_2") (pintype "passive"))
    )
    (net (code "102") (name "Net-(R1332-Pad1)") (class "Default")
      (node (ref "R1332") (pin "1") (pinfunction "1_1") (pintype "passive"))
      (node (ref "X1331") (pin "4") (pinfunction "4_4") (pintype "passive"))
    )
    (net (code "103") (name "Net-(R1333-Pad1)") (class "Default")
      (node (ref "R1333") (pin "1") (pinfunction "1_1") (pintype "passive"))
      (node (ref "X1331") (pin "6") (pinfunction "6_6") (pintype "passive"))
    )
    (net (code "104") (name "Net-(R1334-Pad1)") (class "Default")
      (node (ref "R1334") (pin "1") (pinfunction "1_1") (pintype "passive"))
      (node (ref "X1331") (pin "8") (pinfunction "8_8") (pintype "passive"))
    )
    (net (code "105") (name "Net-(R1335-Pad1)") (class "Default")
      (node (ref "R1335") (pin "1") (pinfunction "1_1") (pintype "passive"))
      (node (ref "X1331") (pin "10") (pinfunction "10_10") (pintype "passive"))
    )
    (net (code "106") (name "Net-(R1337-Pad1)") (class "Default")
      (node (ref "R1337") (pin "1") (pinfunction "1_1") (pintype "passive"))
      (node (ref "X1331") (pin "14") (pinfunction "14_14") (pintype "passive"))
    )
    (net (code "107") (name "Net-(R1338-Pad1)") (class "Default")
      (node (ref "R1338") (pin "1") (pinfunction "1_1") (pintype "passive"))
      (node (ref "R1339") (pin "1") (pinfunction "1_1") (pintype "passive"))
      (node (ref "X1332") (pin "2") (pinfunction "2_2") (pintype "passive"))
    )
    (net (code "108") (name "Net-(R1351-Pad2)") (class "Default")
      (node (ref "R1351") (pin "2") (pinfunction "2_2") (pintype "passive"))
      (node (ref "X1351") (pin "1") (pinfunction "1_1") (pintype "passive"))
    )
    (net (code "109") (name "Net-(R1352-Pad2)") (class "Default")
      (node (ref "R1352") (pin "2") (pinfunction "2_2") (pintype "passive"))
      (node (ref "X1351") (pin "2") (pinfunction "2_2") (pintype "passive"))
    )
    (net (code "110") (name "Net-(R1353-Pad2)") (class "Default")
      (node (ref "R1353") (pin "2") (pinfunction "2_2") (pintype "passive"))
      (node (ref "X1351") (pin "3") (pinfunction "3_3") (pintype "passive"))
    )
    (net (code "111") (name "Net-(R1354-Pad2)") (class "Default")
      (node (ref "R1354") (pin "2") (pinfunction "2_2") (pintype "passive"))
      (node (ref "X1351") (pin "4") (pinfunction "4_4") (pintype "passive"))
    )
    (net (code "112") (name "Net-(R1355-Pad2)") (class "Default")
      (node (ref "R1355") (pin "2") (pinfunction "2_2") (pintype "passive"))
      (node (ref "X1351") (pin "5") (pinfunction "5_5") (pintype "passive"))
    )
    (net (code "113") (name "Net-(R1356-Pad2)") (class "Default")
      (node (ref "R1356") (pin "2") (pinfunction "2_2") (pintype "passive"))
      (node (ref "X1351") (pin "6") (pinfunction "6_6") (pintype "passive"))
    )
    (net (code "114") (name "Net-(R1357-Pad2)") (class "Default")
      (node (ref "R1357") (pin "2") (pinfunction "2_2") (pintype "passive"))
      (node (ref "X1351") (pin "7") (pinfunction "7_7") (pintype "passive"))
    )
    (net (code "115") (name "Net-(R1358-Pad2)") (class "Default")
      (node (ref "R1358") (pin "2") (pinfunction "2_2") (pintype "passive"))
      (node (ref "X1351") (pin "8") (pinfunction "8_8") (pintype "passive"))
    )
    (net (code "116") (name "Net-(R1361-Pad2)") (class "Default")
      (node (ref "R1361") (pin "2") (pinfunction "2_2") (pintype "passive"))
      (node (ref "X1361") (pin "1") (pinfunction "1_1") (pintype "passive"))
    )
    (net (code "117") (name "Net-(R1362-Pad2)") (class "Default")
      (node (ref "R1362") (pin "2") (pinfunction "2_2") (pintype "passive"))
      (node (ref "X1361") (pin "2") (pinfunction "2_2") (pintype "passive"))
    )
    (net (code "118") (name "Net-(R1363-Pad2)") (class "Default")
      (node (ref "R1363") (pin "2") (pinfunction "2_2") (pintype "passive"))
      (node (ref "X1361") (pin "3") (pinfunction "3_3") (pintype "passive"))
    )
    (net (code "119") (name "Net-(R1364-Pad2)") (class "Default")
      (node (ref "R1364") (pin "2") (pinfunction "2_2") (pintype "passive"))
      (node (ref "X1361") (pin "4") (pinfunction "4_4") (pintype "passive"))
    )
    (net (code "120") (name "Net-(R1365-Pad2)") (class "Default")
      (node (ref "R1365") (pin "2") (pinfunction "2_2") (pintype "passive"))
      (node (ref "X1361") (pin "5") (pinfunction "5_5") (pintype "passive"))
    )
    (net (code "121") (name "Net-(R1366-Pad2)") (class "Default")
      (node (ref "R1366") (pin "2") (pinfunction "2_2") (pintype "passive"))
      (node (ref "X1361") (pin "6") (pinfunction "6_6") (pintype "passive"))
    )
    (net (code "122") (name "Net-(S1321-P)") (class "Default")
      (node (ref "R1321") (pin "2") (pinfunction "2_2") (pintype "passive"))
      (node (ref "S1321") (pin "1") (pinfunction "P_1") (pintype "passive"))
    )
    (net (code "123") (name "Net-(T0551-C)") (class "Default")
      (node (ref "T0551") (pin "3") (pinfunction "C_3") (pintype "passive"))
      (node (ref "U0501") (pin "11") (pinfunction "K_BL_11") (pintype "passive"))
    )
    (net (code "124") (name "Net-(T0551-E)") (class "Default")
      (node (ref "R0553") (pin "2") (pinfunction "2_2") (pintype "passive"))
      (node (ref "T0551") (pin "2") (pinfunction "E_2") (pintype "passive"))
    )
    (net (code "125") (name "Net-(U0501-CAP1N)") (class "Default")
      (node (ref "C0511") (pin "2") (pinfunction "2_2") (pintype "passive"))
      (node (ref "U0501") (pin "2") (pinfunction "CAP1N_2") (pintype "passive"))
    )
    (net (code "126") (name "Net-(U0501-CAP1P)") (class "Default")
      (node (ref "C0511") (pin "1") (pinfunction "1_1") (pintype "passive"))
      (node (ref "U0501") (pin "3") (pinfunction "CAP1P_3") (pintype "passive"))
    )
    (net (code "127") (name "Net-(U0501-VOUT)") (class "Default")
      (node (ref "C0512") (pin "1") (pinfunction "1_1") (pintype "passive"))
      (node (ref "U0501") (pin "1") (pinfunction "VOUT_1") (pintype "passive"))
    )
    (net (code "128") (name "Net-(U0701-AVDD0)") (class "Default")
      (node (ref "C0707") (pin "2") (pinfunction "2_2") (pintype "passive"))
      (node (ref "U0701") (pin "14") (pinfunction "AVDD0_14") (pintype "passive"))
    )
    (net (code "129") (name "Net-(U0701-AVDD1)") (class "Default")
      (node (ref "C0708") (pin "2") (pinfunction "2_2") (pintype "passive"))
      (node (ref "U0701") (pin "47") (pinfunction "AVDD1_47") (pintype "passive"))
    )
    (net (code "130") (name "Net-(U0701-CLKO)") (class "Default")
      (node (ref "R0711") (pin "2") (pinfunction "2_2") (pintype "passive"))
      (node (ref "U0701") (pin "22") (pinfunction "CLKO_22") (pintype "output"))
    )
    (net (code "131") (name "Net-(U0701-DVDD)") (class "Default")
      (node (ref "C0706") (pin "2") (pinfunction "2_2") (pintype "passive"))
      (node (ref "U0701") (pin "37") (pinfunction "DVDD_37") (pintype "passive"))
    )
    (net (code "132") (name "Net-(U0701-IRQ)") (class "Default")
      (node (ref "R0756") (pin "1") (pinfunction "1_1") (pintype "passive"))
      (node (ref "U0701") (pin "40") (pinfunction "IRQ_40") (pintype "output"))
    )
    (net (code "133") (name "Net-(U0701-MISO)") (class "Default")
      (node (ref "R0754") (pin "1") (pinfunction "1_1") (pintype "passive"))
      (node (ref "U0701") (pin "44") (pinfunction "MISO_44") (pintype "output"))
    )
    (net (code "134") (name "Net-(U0701-MOSI)") (class "Default")
      (node (ref "R0753") (pin "1") (pinfunction "1_1") (pintype "passive"))
      (node (ref "U0701") (pin "43") (pinfunction "MOSI_43") (pintype "input"))
    )
    (net (code "135") (name "Net-(U0701-RSTN)") (class "Default")
      (node (ref "R0755") (pin "1") (pinfunction "1_1") (pintype "passive"))
      (node (ref "U0701") (pin "13") (pinfunction "RSTN_13") (pintype "input"))
    )
    (net (code "136") (name "Net-(U0701-SCLK)") (class "Default")
      (node (ref "R0751") (pin "1") (pinfunction "1_1") (pintype "passive"))
      (node (ref "U0701") (pin "41") (pinfunction "SCLK_41") (pintype "input"))
    )
    (net (code "137") (name "Net-(U0701-SELN)") (class "Default")
      (node (ref "R0752") (pin "1") (pinfunction "1_1") (pintype "passive"))
      (node (ref "U0701") (pin "42") (pinfunction "SELN_42") (pintype "input"))
    )
    (net (code "138") (name "Net-(U0701-TCXO)") (class "Default")
      (node (ref "C0712") (pin "2") (pinfunction "2_2") (pintype "passive"))
      (node (ref "U0701") (pin "17") (pinfunction "TCXO_17") (pintype "input"))
    )
    (net (code "139") (name "Net-(U0701-XTAL2)") (class "Default")
      (node (ref "C0704") (pin "2") (pinfunction "2_2") (pintype "passive"))
      (node (ref "C0707") (pin "1") (pinfunction "1_1") (pintype "passive"))
      (node (ref "C0708") (pin "1") (pinfunction "1_1") (pintype "passive"))
      (node (ref "L0701") (pin "2") (pinfunction "2_2") (pintype "passive"))
      (node (ref "U0701") (pin "10") (pinfunction "AVSS_10") (pintype "passive"))
      (node (ref "U0701") (pin "16") (pinfunction "AVSS_16") (pintype "passive"))
      (node (ref "U0701") (pin "18") (pinfunction "XTAL2_18") (pintype "passive"))
      (node (ref "U0701") (pin "19") (pinfunction "AVSS_19") (pintype "passive"))
      (node (ref "U0701") (pin "3") (pinfunction "AVSS_3") (pintype "passive"))
      (node (ref "U0701") (pin "45") (pinfunction "AVSS_45") (pintype "passive"))
      (node (ref "U0701") (pin "48") (pinfunction "AVSS_48") (pintype "passive"))
      (node (ref "U0701") (pin "49") (pinfunction "AVSS_49") (pintype "passive"))
      (node (ref "U0701") (pin "6") (pinfunction "AVSS_6") (pintype "passive"))
      (node (ref "U0701") (pin "7") (pinfunction "AVSS_7") (pintype "passive"))
    )
    (net (code "140") (name "Net-(U0711-OUT)") (class "Default")
      (node (ref "C0712") (pin "1") (pinfunction "1_1") (pintype "passive"))
      (node (ref "U0711") (pin "3") (pinfunction "OUT_3") (pintype "output"))
    )
    (net (code "141") (name "Net-(U0811-RF1)") (class "Default")
      (node (ref "C0831") (pin "2") (pinfunction "2_2") (pintype "passive"))
      (node (ref "U0811") (pin "1") (pinfunction "RF1_1") (pintype "passive"))
    )
    (net (code "142") (name "Net-(U0811-RF2)") (class "Default")
      (node (ref "C0832") (pin "2") (pinfunction "2_2") (pintype "passive"))
      (node (ref "U0811") (pin "3") (pinfunction "RF2_3") (pintype "passive"))
    )
    (net (code "143") (name "Net-(U0811-RFC)") (class "Default")
      (node (ref "C0821") (pin "1") (pinfunction "1_1") (pintype "passive"))
      (node (ref "U0811") (pin "5") (pinfunction "RFC_5") (pintype "passive"))
    )
    (net (code "144") (name "Net-(U0821-IND)") (class "Default")
      (node (ref "L0821") (pin "1") (pinfunction "1_1") (pintype "passive"))
      (node (ref "U0821") (pin "10") (pinfunction "IND_10") (pintype "passive"))
    )
    (net (code "145") (name "Net-(U0821-MODE)") (class "Default")
      (node (ref "R0861") (pin "2") (pinfunction "2_2") (pintype "passive"))
      (node (ref "U0821") (pin "16") (pinfunction "MODE_16") (pintype "input"))
    )
    (net (code "146") (name "Net-(U0821-RXEN)") (class "Default")
      (node (ref "R0862") (pin "2") (pinfunction "2_2") (pintype "passive"))
      (node (ref "U0821") (pin "1") (pinfunction "RXEN_1") (pintype "input"))
    )
    (net (code "147") (name "Net-(U0821-VDD3)") (class "Default")
      (node (ref "L0853") (pin "2") (pinfunction "2_2") (pintype "passive"))
      (node (ref "U0821") (pin "7") (pinfunction "VDD3_7") (pintype "power_in"))
    )
    (net (code "148") (name "Net-(U0881-OUT)") (class "Default")
      (node (ref "C0893") (pin "1") (pinfunction "1_1") (pintype "passive"))
      (node (ref "L0892") (pin "1") (pinfunction "1_1") (pintype "passive"))
      (node (ref "U0881") (pin "5") (pinfunction "OUT_5") (pintype "passive"))
    )
    (net (code "149") (name "Net-(U0911-ACBUS3)") (class "Default")
      (node (ref "R0971") (pin "1") (pinfunction "1_1") (pintype "passive"))
      (node (ref "U0911") (pin "27") (pinfunction "ACBUS3_27") (pintype "output"))
    )
    (net (code "150") (name "Net-(U0911-ACBUS4)") (class "Default")
      (node (ref "R0972") (pin "1") (pinfunction "1_1") (pintype "passive"))
      (node (ref "U0911") (pin "28") (pinfunction "ACBUS4_28") (pintype "output"))
    )
    (net (code "151") (name "Net-(U0911-ADBUS0)") (class "Default")
      (node (ref "R0961") (pin "1") (pinfunction "1_1") (pintype "passive"))
      (node (ref "U0911") (pin "13") (pinfunction "ADBUS0_13") (pintype "output"))
    )
    (net (code "152") (name "Net-(U0911-ADBUS1)") (class "Default")
      (node (ref "R0962") (pin "1") (pinfunction "1_1") (pintype "passive"))
      (node (ref "U0911") (pin "14") (pinfunction "ADBUS1_14") (pintype "input"))
    )
    (net (code "153") (name "Net-(U0911-ADBUS2)") (class "Default")
      (node (ref "R0963") (pin "1") (pinfunction "1_1") (pintype "passive"))
      (node (ref "U0911") (pin "15") (pinfunction "ADBUS2_15") (pintype "output"))
    )
    (net (code "154") (name "Net-(U0911-ADBUS3)") (class "Default")
      (node (ref "R0964") (pin "1") (pinfunction "1_1") (pintype "passive"))
      (node (ref "U0911") (pin "16") (pinfunction "ADBUS3_16") (pintype "input"))
    )
    (net (code "155") (name "Net-(U0911-ADBUS4)") (class "Default")
      (node (ref "R0965") (pin "1") (pinfunction "1_1") (pintype "passive"))
      (node (ref "U0911") (pin "17") (pinfunction "ADBUS4_17") (pintype "output"))
    )
    (net (code "156") (name "Net-(U0911-ADBUS5)") (class "Default")
      (node (ref "R0966") (pin "1") (pinfunction "1_1") (pintype "passive"))
      (node (ref "U0911") (pin "18") (pinfunction "ADBUS5_18") (pintype "input"))
    )
    (net (code "157") (name "Net-(U0911-ADBUS6)") (class "Default")
      (node (ref "R0967") (pin "1") (pinfunction "1_1") (pintype "passive"))
      (node (ref "U0911") (pin "19") (pinfunction "ADBUS6_19") (pintype "input"))
    )
    (net (code "158") (name "Net-(U0911-ADBUS7)") (class "Default")
      (node (ref "R0968") (pin "1") (pinfunction "1_1") (pintype "passive"))
      (node (ref "U0911") (pin "20") (pinfunction "ADBUS7_20") (pintype "input"))
    )
    (net (code "159") (name "Net-(U0911-EEDATA)") (class "Default")
      (node (ref "R0931") (pin "1") (pinfunction "1_1") (pintype "passive"))
      (node (ref "U0911") (pin "43") (pinfunction "EEDATA_43") (pintype "bidirectional"))
    )
    (net (code "160") (name "Net-(U0911-OSCI)") (class "Default")
      (node (ref "R0941") (pin "2") (pinfunction "2_2") (pintype "passive"))
      (node (ref "U0911") (pin "1") (pinfunction "OSCI_1") (pintype "passive"))
    )
    (net (code "161") (name "Net-(U0911-REF)") (class "Default")
      (node (ref "R0911") (pin "2") (pinfunction "2_2") (pintype "passive"))
      (node (ref "U0911") (pin "5") (pinfunction "REF_5") (pintype "passive"))
    )
    (net (code "162") (name "Net-(U0911-VCCA)") (class "Default")
      (node (ref "C0913") (pin "2") (pinfunction "2_2") (pintype "passive"))
      (node (ref "U0911") (pin "37") (pinfunction "VCCA_37") (pintype "passive"))
    )
    (net (code "163") (name "Net-(U0911-VCCCORE)") (class "Default")
      (node (ref "C0912") (pin "2") (pinfunction "2_2") (pintype "passive"))
      (node (ref "U0911") (pin "38") (pinfunction "VCCCORE_38") (pintype "passive"))
    )
    (net (code "164") (name "Net-(U0911-VCCD)") (class "Default")
      (node (ref "D0971") (pin "A") (pinfunction "A_A") (pintype "passive"))
      (node (ref "D0972") (pin "A") (pinfunction "A_A") (pintype "passive"))
      (node (ref "L0921") (pin "2") (pinfunction "2_2") (pintype "passive"))
      (node (ref "L0922") (pin "2") (pinfunction "2_2") (pintype "passive"))
      (node (ref "R0931") (pin "2") (pinfunction "2_2") (pintype "passive"))
      (node (ref "U0911") (pin "12") (pinfunction "VCCIO_12") (pintype "power_in"))
      (node (ref "U0911") (pin "24") (pinfunction "VCCIO_24") (pintype "power_in"))
      (node (ref "U0911") (pin "39") (pinfunction "VCCD_39") (pintype "power_in"))
      (node (ref "U0911") (pin "46") (pinfunction "VCCIO_46") (pintype "power_in"))
    )
    (net (code "165") (name "Net-(U0911-VPHY)") (class "Default")
      (node (ref "C0922") (pin "2") (pinfunction "2_2") (pintype "passive"))
      (node (ref "L0922") (pin "1") (pinfunction "1_1") (pintype "passive"))
      (node (ref "U0911") (pin "3") (pinfunction "VPHY_3") (pintype "power_in"))
    )
    (net (code "166") (name "Net-(U0911-VPLL)") (class "Default")
      (node (ref "C0921") (pin "2") (pinfunction "2_2") (pintype "passive"))
      (node (ref "L0921") (pin "1") (pinfunction "1_1") (pintype "passive"))
      (node (ref "U0911") (pin "8") (pinfunction "VPLL_8") (pintype "power_in"))
    )
    (net (code "167") (name "Net-(U0911-~{RESET})") (class "Default")
      (node (ref "R0912") (pin "2") (pinfunction "2_2") (pintype "passive"))
      (node (ref "R0913") (pin "2") (pinfunction "2_2") (pintype "passive"))
      (node (ref "U0911") (pin "34") (pinfunction "~{RESET}_34") (pintype "input"))
    )
    (net (code "168") (name "Net-(U1101-EN)") (class "Default")
      (node (ref "D1161") (pin "A") (pinfunction "A_A") (pintype "passive"))
      (node (ref "R1161") (pin "1") (pinfunction "1_1") (pintype "passive"))
      (node (ref "U1101") (pin "2") (pinfunction "EN_2") (pintype "input"))
    )
    (net (code "169") (name "Net-(U1101-VBST)") (class "Default")
      (node (ref "R1108") (pin "1") (pinfunction "1_1") (pintype "passive"))
      (node (ref "U1101") (pin "4") (pinfunction "VBST_4") (pintype "passive"))
    )
    (net (code "170") (name "Net-(U1101-VFB)") (class "Default")
      (node (ref "C1132") (pin "2") (pinfunction "2_2") (pintype "passive"))
      (node (ref "R1101") (pin "2") (pinfunction "2_2") (pintype "passive"))
      (node (ref "R1102") (pin "1") (pinfunction "1_1") (pintype "passive"))
      (node (ref "U1101") (pin "1") (pinfunction "VFB_1") (pintype "passive"))
    )
    (net (code "171") (name "Net-(U1211-EN)") (class "Default")
      (node (ref "R1211") (pin "2") (pinfunction "2_2") (pintype "passive"))
      (node (ref "U1211") (pin "12") (pinfunction "EN_12") (pintype "input"))
    )
    (net (code "172") (name "Net-(U1211-SW)") (class "Default")
      (node (ref "L1211") (pin "2") (pinfunction "2_2") (pintype "passive"))
      (node (ref "U1211") (pin "2") (pinfunction "SW_2") (pintype "passive"))
    )
    (net (code "173") (name "Net-(X1311-J_VUSB)") (class "Default")
      (node (ref "PF1311") (pin "2") (pinfunction "2_2") (pintype "passive"))
      (node (ref "X1311") (pin "VBUS") (pinfunction "J_VUSB_VBUS") (pintype "power_in"))
    )
    (net (code "174") (name "RFX_DET") (class "Default")
      (node (ref "R0821") (pin "1") (pinfunction "1_1") (pintype "passive"))
      (node (ref "R0822") (pin "2") (pinfunction "2_2") (pintype "passive"))
      (node (ref "U0821") (pin "5") (pinfunction "DET_5") (pintype "output"))
    )
    (net (code "175") (name "RFX_TXEN") (class "Default")
      (node (ref "R0863") (pin "2") (pinfunction "2_2") (pintype "passive"))
      (node (ref "U0811") (pin "4") (pinfunction "CTRL_4") (pintype "input"))
      (node (ref "U0821") (pin "2") (pinfunction "TXEN_2") (pintype "input"))
    )
    (net (code "176") (name "TPS_MODE") (class "Default")
      (node (ref "R1106") (pin "2") (pinfunction "2_2") (pintype "passive"))
      (node (ref "U1101") (pin "20") (pinfunction "MODE_20") (pintype "passive"))
    )
    (net (code "177") (name "TPS_PGOOD") (class "Default")
      (node (ref "R1107") (pin "1") (pinfunction "1_1") (pintype "passive"))
      (node (ref "U1101") (pin "3") (pinfunction "PGOOD_3") (pintype "open_collector"))
    )
    (net (code "178") (name "TPS_RF") (class "Default")
      (node (ref "R1103") (pin "2") (pinfunction "2_2") (pintype "passive"))
      (node (ref "R1104") (pin "2") (pinfunction "2_2") (pintype "passive"))
      (node (ref "U1101") (pin "22") (pinfunction "RF_22") (pintype "passive"))
    )
    (net (code "179") (name "TPS_TRIP") (class "Default")
      (node (ref "R1105") (pin "2") (pinfunction "2_2") (pintype "passive"))
      (node (ref "U1101") (pin "21") (pinfunction "TRIP_21") (pintype "passive"))
    )
    (net (code "180") (name "TPS_VIN") (class "Default")
      (node (ref "C1101") (pin "2") (pinfunction "2_2") (pintype "passive"))
      (node (ref "C1111") (pin "2") (pinfunction "2_2") (pintype "passive"))
      (node (ref "C1112") (pin "2") (pinfunction "2_2") (pintype "passive"))
      (node (ref "C1113") (pin "2") (pinfunction "2_2") (pintype "passive"))
      (node (ref "C1114") (pin "2") (pinfunction "2_2") (pintype "passive"))
      (node (ref "D1111") (pin "C") (pinfunction "C_C") (pintype "passive"))
      (node (ref "D1112") (pin "C") (pinfunction "C_C") (pintype "passive"))
      (node (ref "R1161") (pin "2") (pinfunction "2_2") (pintype "passive"))
      (node (ref "U1101") (pin "12") (pinfunction "VIN_12") (pintype "power_in"))
      (node (ref "U1101") (pin "13") (pinfunction "VIN_13") (pintype "power_in"))
      (node (ref "U1101") (pin "14") (pinfunction "VIN_14") (pintype "power_in"))
      (node (ref "U1101") (pin "15") (pinfunction "VIN_15") (pintype "power_in"))
      (node (ref "U1101") (pin "16") (pinfunction "VIN_16") (pintype "power_in"))
      (node (ref "U1101") (pin "17") (pinfunction "VIN_17") (pintype "power_in"))
      (node (ref "U1101") (pin "19") (pinfunction "VDD_19") (pintype "power_in"))
    )
    (net (code "181") (name "TPS_VREG") (class "Default")
      (node (ref "C1102") (pin "2") (pinfunction "2_2") (pintype "passive"))
      (node (ref "D1161") (pin "C") (pinfunction "C_C") (pintype "passive"))
      (node (ref "R1107") (pin "2") (pinfunction "2_2") (pintype "passive"))
      (node (ref "U1101") (pin "18") (pinfunction "VREG_18") (pintype "power_in"))
    )
    (net (code "182") (name "TRX_CLK_26MHZ") (class "Default")
      (node (ref "C0713") (pin "2") (pinfunction "2_2") (pintype "passive"))
      (node (ref "JB2") (pin "52") (pinfunction "B15_L11_CLK_P_52") (pintype "passive"))
      (node (ref "R0711") (pin "1") (pinfunction "1_1") (pintype "passive"))
    )
    (net (code "183") (name "TRX_FEA09") (class "Default")
      (node (ref "R0863") (pin "1") (pinfunction "1_1") (pintype "passive"))
      (node (ref "U0701") (pin "11") (pinfunction "FEA09_11") (pintype "output"))
    )
    (net (code "184") (name "TRX_FEA24") (class "Default")
      (node (ref "U0701") (pin "1") (pinfunction "FEA24_1") (pintype "output"))
    )
    (net (code "185") (name "TRX_FEB09") (class "Default")
      (node (ref "R0862") (pin "1") (pinfunction "1_1") (pintype "passive"))
      (node (ref "U0701") (pin "12") (pinfunction "FEB09_12") (pintype "output"))
    )
    (net (code "186") (name "TRX_FEB24") (class "Default")
      (node (ref "U0701") (pin "2") (pinfunction "FEB24_2") (pintype "output"))
    )
    (net (code "187") (name "TRX_IRQ") (class "Default")
      (node (ref "JB2") (pin "68") (pinfunction "B15_L16_N_68") (pintype "passive"))
      (node (ref "R0756") (pin "2") (pinfunction "2_2") (pintype "passive"))
    )
    (net (code "188") (name "TRX_MISO") (class "Default")
      (node (ref "JB2") (pin "78") (pinfunction "B15_L2_P_78") (pintype "passive"))
      (node (ref "R0754") (pin "2") (pinfunction "2_2") (pintype "passive"))
    )
    (net (code "189") (name "TRX_MOSI") (class "Default")
      (node (ref "JB2") (pin "76") (pinfunction "B15_L2_N_76") (pintype "passive"))
      (node (ref "R0753") (pin "2") (pinfunction "2_2") (pintype "passive"))
    )
    (net (code "190") (name "TRX_RF09") (class "Default")
      (node (ref "C0821") (pin "2") (pinfunction "2_2") (pintype "passive"))
      (node (ref "L0721") (pin "4") (pinfunction "UB_4") (pintype "passive"))
    )
    (net (code "191") (name "TRX_RF24") (class "Default")
      (node (ref "C0897") (pin "1") (pinfunction "1_1") (pintype "passive"))
      (node (ref "L0722") (pin "1") (pinfunction "UB_1") (pintype "passive"))
      (node (ref "L0896") (pin "1") (pinfunction "1_1") (pintype "passive"))
    )
    (net (code "192") (name "TRX_RSTN") (class "Default")
      (node (ref "JB2") (pin "66") (pinfunction "B15_L16_P_66") (pintype "passive"))
      (node (ref "R0755") (pin "2") (pinfunction "2_2") (pintype "passive"))
    )
    (net (code "193") (name "TRX_RXCLK_N") (class "Default")
      (node (ref "JB1") (pin "22") (pinfunction "B13_L11_N_22") (pintype "passive"))
      (node (ref "U0701") (pin "33") (pinfunction "RXCLKN_33") (pintype "output"))
    )
    (net (code "194") (name "TRX_RXCLK_P") (class "Default")
      (node (ref "JB1") (pin "24") (pinfunction "B13_L11_P_24") (pintype "passive"))
      (node (ref "U0701") (pin "34") (pinfunction "RXCLKP_34") (pintype "output"))
    )
    (net (code "195") (name "TRX_RXD09_N") (class "Default")
      (node (ref "JB1") (pin "20") (pinfunction "B13_L3_N_20") (pintype "passive"))
      (node (ref "U0701") (pin "30") (pinfunction "RXD09N_30") (pintype "output"))
    )
    (net (code "196") (name "TRX_RXD09_P") (class "Default")
      (node (ref "JB1") (pin "18") (pinfunction "B13_L3_P_18") (pintype "passive"))
      (node (ref "U0701") (pin "31") (pinfunction "RXD09P_31") (pintype "output"))
    )
    (net (code "197") (name "TRX_RXD24_N") (class "Default")
      (node (ref "JB1") (pin "26") (pinfunction "B13_L9_N_26") (pintype "passive"))
      (node (ref "U0701") (pin "35") (pinfunction "RXD24N_35") (pintype "output"))
    )
    (net (code "198") (name "TRX_RXD24_P") (class "Default")
      (node (ref "JB1") (pin "28") (pinfunction "B13_L9_P_28") (pintype "passive"))
      (node (ref "U0701") (pin "36") (pinfunction "RXD24P_36") (pintype "output"))
    )
    (net (code "199") (name "TRX_SCLK") (class "Default")
      (node (ref "JB2") (pin "72") (pinfunction "B15_L1_P_72") (pintype "passive"))
      (node (ref "R0751") (pin "2") (pinfunction "2_2") (pintype "passive"))
    )
    (net (code "200") (name "TRX_SELN") (class "Default")
      (node (ref "JB2") (pin "74") (pinfunction "B15_L1_N_74") (pintype "passive"))
      (node (ref "R0752") (pin "2") (pinfunction "2_2") (pintype "passive"))
    )
    (net (code "201") (name "TRX_TXCLK_N") (class "Default")
      (node (ref "JB1") (pin "15") (pinfunction "B13_L6_N_15") (pintype "passive"))
      (node (ref "U0701") (pin "25") (pinfunction "TXCLKN_25") (pintype "input"))
    )
    (net (code "202") (name "TRX_TXCLK_P") (class "Default")
      (node (ref "JB1") (pin "17") (pinfunction "B13_L6_P_17") (pintype "passive"))
      (node (ref "U0701") (pin "26") (pinfunction "TXCLKP_26") (pintype "input"))
    )
    (net (code "203") (name "TRX_TXD_N") (class "Default")
      (node (ref "JB1") (pin "21") (pinfunction "B13_L5_N_21") (pintype "passive"))
      (node (ref "U0701") (pin "27") (pinfunction "TXDN_27") (pintype "input"))
    )
    (net (code "204") (name "TRX_TXD_P") (class "Default")
      (node (ref "JB1") (pin "23") (pinfunction "B13_L5_P_23") (pintype "passive"))
      (node (ref "U0701") (pin "28") (pinfunction "TXDP_28") (pintype "input"))
    )
    (net (code "205") (name "TRX_TXD_VOID_N") (class "Default")
      (node (ref "JB3") (pin "49") (pinfunction "B13_L4_N_49") (pintype "passive"))
    )
    (net (code "206") (name "TRX_TXD_VOID_P") (class "Default")
      (node (ref "JB3") (pin "47") (pinfunction "B13_L4_P_47") (pintype "passive"))
    )
    (net (code "207") (name "U1V5") (class "Default")
      (node (ref "JB2") (pin "20") (pinfunction "U1V5_20") (pintype "power_in"))
    )
    (net (code "208") (name "U1V8") (class "Default")
      (node (ref "JB1") (pin "40") (pinfunction "U1V8_40") (pintype "power_in"))
      (node (ref "R0202") (pin "1") (pinfunction "1_1") (pintype "passive"))
      (node (ref "X1381") (pin "2") (pinfunction "2_2") (pintype "passive"))
    )
    (net (code "209") (name "U3V3") (class "Default")
      (node (ref "JB1") (pin "13") (pinfunction "U3V3_13") (pintype "power_in"))
      (node (ref "JB2") (pin "10") (pinfunction "VCCIO15_10") (pintype "power_in"))
      (node (ref "JB2") (pin "11") (pinfunction "U3V3_11") (pintype "power_in"))
      (node (ref "JB2") (pin "8") (pinfunction "VCCIO15_8") (pintype "power_in"))
      (node (ref "JB2") (pin "9") (pinfunction "U3V3_9") (pintype "power_in"))
      (node (ref "R1211") (pin "1") (pinfunction "1_1") (pintype "passive"))
      (node (ref "X1381") (pin "6") (pinfunction "6_6") (pintype "passive"))
    )
    (net (code "210") (name "U3V3_JTAGREF") (class "Default")
      (node (ref "JB2") (pin "92") (pinfunction "U3V3_JTAGREF_92") (pintype "power_in"))
      (node (ref "R1331") (pin "2") (pinfunction "2_2") (pintype "passive"))
    )
    (net (code "211") (name "USB_D_N") (class "Default")
      (node (ref "U0911") (pin "6") (pinfunction "D_M_6") (pintype "passive"))
      (node (ref "X1311") (pin "D-") (pinfunction "J_D-_D-") (pintype "bidirectional"))
    )
    (net (code "212") (name "USB_D_P") (class "Default")
      (node (ref "U0911") (pin "7") (pinfunction "D_P_7") (pintype "passive"))
      (node (ref "X1311") (pin "D+") (pinfunction "J_D+_D+") (pintype "bidirectional"))
    )
    (net (code "213") (name "USB_ID") (class "Default")
      (node (ref "X1311") (pin "ID") (pinfunction "J_ID_ID") (pintype "bidirectional"))
    )
    (net (code "214") (name "VBAT_IN") (class "Default")
      (node (ref "JB1") (pin "80") (pinfunction "VBAT_IN_80") (pintype "power_in"))
    )
    (net (code "215") (name "VCCIO13") (class "Default")
      (node (ref "JB2") (pin "2") (pinfunction "VCCIO13_2") (pintype "power_in"))
      (node (ref "JB2") (pin "4") (pinfunction "VCCIO13_4") (pintype "power_in"))
      (node (ref "R0201") (pin "2") (pinfunction "2_2") (pintype "passive"))
      (node (ref "R0202") (pin "2") (pinfunction "2_2") (pintype "passive"))
      (node (ref "S1321") (pin "2") (pinfunction "S_2") (pintype "passive"))
    )
    (net (code "216") (name "VCCIO16") (class "Default")
      (node (ref "C1381") (pin "2") (pinfunction "2_2") (pintype "passive"))
      (node (ref "JB1") (pin "10") (pinfunction "VCCIO16_10") (pintype "power_in"))
      (node (ref "JB1") (pin "12") (pinfunction "VCCIO16_12") (pintype "power_in"))
      (node (ref "X1381") (pin "1") (pinfunction "1_1") (pintype "passive"))
      (node (ref "X1381") (pin "3") (pinfunction "3_3") (pintype "passive"))
      (node (ref "X1381") (pin "5") (pinfunction "5_5") (pintype "passive"))
    )
    (net (code "217") (name "VCTCXO_VC") (class "Default")
      (node (ref "C0621") (pin "1") (pinfunction "1_1") (pintype "passive"))
      (node (ref "R0621") (pin "2") (pinfunction "2_2") (pintype "passive"))
      (node (ref "U0711") (pin "1") (pinfunction "VC_1") (pintype "input"))
    )
    (net (code "218") (name "VIN_PWR") (class "Default")
      (node (ref "D1111") (pin "A") (pinfunction "A_A") (pintype "passive"))
      (node (ref "X1361") (pin "7") (pinfunction "7_7") (pintype "passive"))
    )
    (net (code "219") (name "unconnected-(J1411-Pad9)") (class "Default")
      (node (ref "J1411") (pin "9") (pinfunction "9_9") (pintype "no_connect"))
    )
    (net (code "220") (name "unconnected-(JB1-B14_L18_MIO_P-Pad88)") (class "Default")
      (node (ref "JB1") (pin "88") (pinfunction "B14_L18_MIO_P_88") (pintype "passive"))
    )
    (net (code "221") (name "unconnected-(JB1-B16_L1_N-Pad97)") (class "Default")
      (node (ref "JB1") (pin "97") (pinfunction "B16_L1_N_97") (pintype "passive"))
    )
    (net (code "222") (name "unconnected-(JB1-B16_L1_P-Pad99)") (class "Default")
      (node (ref "JB1") (pin "99") (pinfunction "B16_L1_P_99") (pintype "passive"))
    )
    (net (code "223") (name "unconnected-(JB1-B16_L3_N-Pad70)") (class "Default")
      (node (ref "JB1") (pin "70") (pinfunction "B16_L3_N_70") (pintype "passive"))
    )
    (net (code "224") (name "unconnected-(JB1-B16_L3_P-Pad72)") (class "Default")
      (node (ref "JB1") (pin "72") (pinfunction "B16_L3_P_72") (pintype "passive"))
    )
    (net (code "225") (name "unconnected-(JB1-B16_L4_N-Pad93)") (class "Default")
      (node (ref "JB1") (pin "93") (pinfunction "B16_L4_N_93") (pintype "passive"))
    )
    (net (code "226") (name "unconnected-(JB1-B16_L4_P-Pad95)") (class "Default")
      (node (ref "JB1") (pin "95") (pinfunction "B16_L4_P_95") (pintype "passive"))
    )
    (net (code "227") (name "unconnected-(JB1-B16_L12_CLK_N-Pad78)") (class "Default")
      (node (ref "JB1") (pin "78") (pinfunction "B16_L12_CLK_N_78") (pintype "passive"))
    )
    (net (code "228") (name "unconnected-(JB1-B16_L12_CLK_P-Pad76)") (class "Default")
      (node (ref "JB1") (pin "76") (pinfunction "B16_L12_CLK_P_76") (pintype "passive"))
    )
    (net (code "229") (name "unconnected-(JB1-B16_L13_CLK_N-Pad62)") (class "Default")
      (node (ref "JB1") (pin "62") (pinfunction "B16_L13_CLK_N_62") (pintype "passive"))
    )
    (net (code "230") (name "unconnected-(JB1-B16_L13_CLK_P-Pad60)") (class "Default")
      (node (ref "JB1") (pin "60") (pinfunction "B16_L13_CLK_P_60") (pintype "passive"))
    )
    (net (code "231") (name "unconnected-(JB1-B16_L14_N-Pad68)") (class "Default")
      (node (ref "JB1") (pin "68") (pinfunction "B16_L14_N_68") (pintype "passive"))
    )
    (net (code "232") (name "unconnected-(JB1-B16_L14_P-Pad66)") (class "Default")
      (node (ref "JB1") (pin "66") (pinfunction "B16_L14_P_66") (pintype "passive"))
    )
    (net (code "233") (name "unconnected-(JB1-B16_L15_N-Pad48)") (class "Default")
      (node (ref "JB1") (pin "48") (pinfunction "B16_L15_N_48") (pintype "passive"))
    )
    (net (code "234") (name "unconnected-(JB1-B16_L15_P-Pad46)") (class "Default")
      (node (ref "JB1") (pin "46") (pinfunction "B16_L15_P_46") (pintype "passive"))
    )
    (net (code "235") (name "unconnected-(JB1-B16_L20_N-Pad52)") (class "Default")
      (node (ref "JB1") (pin "52") (pinfunction "B16_L20_N_52") (pintype "passive"))
    )
    (net (code "236") (name "unconnected-(JB1-B16_L20_P-Pad50)") (class "Default")
      (node (ref "JB1") (pin "50") (pinfunction "B16_L20_P_50") (pintype "passive"))
    )
    (net (code "237") (name "unconnected-(JB1-B16_L21_N-Pad58)") (class "Default")
      (node (ref "JB1") (pin "58") (pinfunction "B16_L21_N_58") (pintype "passive"))
    )
    (net (code "238") (name "unconnected-(JB1-B16_L21_P-Pad56)") (class "Default")
      (node (ref "JB1") (pin "56") (pinfunction "B16_L21_P_56") (pintype "passive"))
    )
    (net (code "239") (name "unconnected-(JB1-B16_L22_N-Pad34)") (class "Default")
      (node (ref "JB1") (pin "34") (pinfunction "B16_L22_N_34") (pintype "passive"))
    )
    (net (code "240") (name "unconnected-(JB1-B16_L22_P-Pad32)") (class "Default")
      (node (ref "JB1") (pin "32") (pinfunction "B16_L22_P_32") (pintype "passive"))
    )
    (net (code "241") (name "unconnected-(JB1-B16_L23_N-Pad44)") (class "Default")
      (node (ref "JB1") (pin "44") (pinfunction "B16_L23_N_44") (pintype "passive"))
    )
    (net (code "242") (name "unconnected-(JB1-B16_L23_P-Pad42)") (class "Default")
      (node (ref "JB1") (pin "42") (pinfunction "B16_L23_P_42") (pintype "passive"))
    )
    (net (code "243") (name "unconnected-(JB1-B16_L24_N-Pad36)") (class "Default")
      (node (ref "JB1") (pin "36") (pinfunction "B16_L24_N_36") (pintype "passive"))
    )
    (net (code "244") (name "unconnected-(JB1-B16_L24_P-Pad38)") (class "Default")
      (node (ref "JB1") (pin "38") (pinfunction "B16_L24_P_38") (pintype "passive"))
    )
    (net (code "245") (name "unconnected-(JB1-NOSEQ-Pad8)") (class "Default")
      (node (ref "JB1") (pin "8") (pinfunction "NOSEQ_8") (pintype "passive"))
    )
    (net (code "246") (name "unconnected-(JB2-B14_L8_N-Pad12)") (class "Default")
      (node (ref "JB2") (pin "12") (pinfunction "B14_L8_N_12") (pintype "passive"))
    )
    (net (code "247") (name "unconnected-(JB2-B14_L10_N-Pad13)") (class "Default")
      (node (ref "JB2") (pin "13") (pinfunction "B14_L10_N_13") (pintype "passive"))
    )
    (net (code "248") (name "unconnected-(JB2-B14_L10_P-Pad15)") (class "Default")
      (node (ref "JB2") (pin "15") (pinfunction "B14_L10_P_15") (pintype "passive"))
    )
    (net (code "249") (name "unconnected-(JB2-B14_L11_N-Pad27)") (class "Default")
      (node (ref "JB2") (pin "27") (pinfunction "B14_L11_N_27") (pintype "passive"))
    )
    (net (code "250") (name "unconnected-(JB2-B14_L11_P-Pad25)") (class "Default")
      (node (ref "JB2") (pin "25") (pinfunction "B14_L11_P_25") (pintype "passive"))
    )
    (net (code "251") (name "unconnected-(JB2-B14_L12_N-Pad23)") (class "Default")
      (node (ref "JB2") (pin "23") (pinfunction "B14_L12_N_23") (pintype "passive"))
    )
    (net (code "252") (name "unconnected-(JB2-B14_L12_P-Pad21)") (class "Default")
      (node (ref "JB2") (pin "21") (pinfunction "B14_L12_P_21") (pintype "passive"))
    )
    (net (code "253") (name "unconnected-(JB2-B14_L13_CLK_N-Pad28)") (class "Default")
      (node (ref "JB2") (pin "28") (pinfunction "B14_L13_CLK_N_28") (pintype "passive"))
    )
    (net (code "254") (name "unconnected-(JB2-B14_L15_N-Pad38)") (class "Default")
      (node (ref "JB2") (pin "38") (pinfunction "B14_L15_N_38") (pintype "passive"))
    )
    (net (code "255") (name "unconnected-(JB2-B14_L15_P-Pad36)") (class "Default")
      (node (ref "JB2") (pin "36") (pinfunction "B14_L15_P_36") (pintype "passive"))
    )
    (net (code "256") (name "unconnected-(JB2-B14_L16_N-Pad34)") (class "Default")
      (node (ref "JB2") (pin "34") (pinfunction "B14_L16_N_34") (pintype "passive"))
    )
    (net (code "257") (name "unconnected-(JB2-B14_L16_P-Pad32)") (class "Default")
      (node (ref "JB2") (pin "32") (pinfunction "B14_L16_P_32") (pintype "passive"))
    )
    (net (code "258") (name "unconnected-(JB2-B15_L3_N-Pad58)") (class "Default")
      (node (ref "JB2") (pin "58") (pinfunction "B15_L3_N_58") (pintype "passive"))
    )
    (net (code "259") (name "unconnected-(JB2-B15_L3_P-Pad56)") (class "Default")
      (node (ref "JB2") (pin "56") (pinfunction "B15_L3_P_56") (pintype "passive"))
    )
    (net (code "260") (name "unconnected-(JB2-B15_L4_N-Pad84)") (class "Default")
      (node (ref "JB2") (pin "84") (pinfunction "B15_L4_N_84") (pintype "passive"))
    )
    (net (code "261") (name "unconnected-(JB2-B15_L4_P-Pad82)") (class "Default")
      (node (ref "JB2") (pin "82") (pinfunction "B15_L4_P_82") (pintype "passive"))
    )
    (net (code "262") (name "unconnected-(JB2-B15_L5_N-Pad86)") (class "Default")
      (node (ref "JB2") (pin "86") (pinfunction "B15_L5_N_86") (pintype "passive"))
    )
    (net (code "263") (name "unconnected-(JB2-B15_L5_P-Pad88)") (class "Default")
      (node (ref "JB2") (pin "88") (pinfunction "B15_L5_P_88") (pintype "passive"))
    )
    (net (code "264") (name "unconnected-(JB2-B15_L6_N-Pad81)") (class "Default")
      (node (ref "JB2") (pin "81") (pinfunction "B15_L6_N_81") (pintype "passive"))
    )
    (net (code "265") (name "unconnected-(JB2-B15_L6_P-Pad83)") (class "Default")
      (node (ref "JB2") (pin "83") (pinfunction "B15_L6_P_83") (pintype "passive"))
    )
    (net (code "266") (name "unconnected-(JB2-B15_L7_N-Pad41)") (class "Default")
      (node (ref "JB2") (pin "41") (pinfunction "B15_L7_N_41") (pintype "passive"))
    )
    (net (code "267") (name "unconnected-(JB2-B15_L7_P-Pad43)") (class "Default")
      (node (ref "JB2") (pin "43") (pinfunction "B15_L7_P_43") (pintype "passive"))
    )
    (net (code "268") (name "unconnected-(JB2-B15_L8_N-Pad35)") (class "Default")
      (node (ref "JB2") (pin "35") (pinfunction "B15_L8_N_35") (pintype "passive"))
    )
    (net (code "269") (name "unconnected-(JB2-B15_L8_P-Pad37)") (class "Default")
      (node (ref "JB2") (pin "37") (pinfunction "B15_L8_P_37") (pintype "passive"))
    )
    (net (code "270") (name "unconnected-(JB2-B15_L9_N-Pad31)") (class "Default")
      (node (ref "JB2") (pin "31") (pinfunction "B15_L9_N_31") (pintype "passive"))
    )
    (net (code "271") (name "unconnected-(JB2-B15_L9_P-Pad33)") (class "Default")
      (node (ref "JB2") (pin "33") (pinfunction "B15_L9_P_33") (pintype "passive"))
    )
    (net (code "272") (name "unconnected-(JB2-B15_L10_N-Pad61)") (class "Default")
      (node (ref "JB2") (pin "61") (pinfunction "B15_L10_N_61") (pintype "passive"))
    )
    (net (code "273") (name "unconnected-(JB2-B15_L10_P-Pad63)") (class "Default")
      (node (ref "JB2") (pin "63") (pinfunction "B15_L10_P_63") (pintype "passive"))
    )
    (net (code "274") (name "unconnected-(JB2-B15_L11_CLK_N-Pad54)") (class "Default")
      (node (ref "JB2") (pin "54") (pinfunction "B15_L11_CLK_N_54") (pintype "passive"))
    )
    (net (code "275") (name "unconnected-(JB2-B15_L12_CLK_N-Pad57)") (class "Default")
      (node (ref "JB2") (pin "57") (pinfunction "B15_L12_CLK_N_57") (pintype "passive"))
    )
    (net (code "276") (name "unconnected-(JB2-B15_L12_CLK_P-Pad55)") (class "Default")
      (node (ref "JB2") (pin "55") (pinfunction "B15_L12_CLK_P_55") (pintype "passive"))
    )
    (net (code "277") (name "unconnected-(JB2-B15_L13_CLK_N-Pad47)") (class "Default")
      (node (ref "JB2") (pin "47") (pinfunction "B15_L13_CLK_N_47") (pintype "passive"))
    )
    (net (code "278") (name "unconnected-(JB2-B15_L13_CLK_P-Pad45)") (class "Default")
      (node (ref "JB2") (pin "45") (pinfunction "B15_L13_CLK_P_45") (pintype "passive"))
    )
    (net (code "279") (name "unconnected-(JB2-B15_L14_CLK_N-Pad53)") (class "Default")
      (node (ref "JB2") (pin "53") (pinfunction "B15_L14_CLK_N_53") (pintype "passive"))
    )
    (net (code "280") (name "unconnected-(JB2-B15_L14_CLK_P-Pad51)") (class "Default")
      (node (ref "JB2") (pin "51") (pinfunction "B15_L14_CLK_P_51") (pintype "passive"))
    )
    (net (code "281") (name "unconnected-(JB2-B15_L17_N-Pad62)") (class "Default")
      (node (ref "JB2") (pin "62") (pinfunction "B15_L17_N_62") (pintype "passive"))
    )
    (net (code "282") (name "unconnected-(JB2-B15_L17_P-Pad64)") (class "Default")
      (node (ref "JB2") (pin "64") (pinfunction "B15_L17_P_64") (pintype "passive"))
    )
    (net (code "283") (name "unconnected-(JB2-B15_L18_N-Pad67)") (class "Default")
      (node (ref "JB2") (pin "67") (pinfunction "B15_L18_N_67") (pintype "passive"))
    )
    (net (code "284") (name "unconnected-(JB2-B15_L18_P-Pad65)") (class "Default")
      (node (ref "JB2") (pin "65") (pinfunction "B15_L18_P_65") (pintype "passive"))
    )
    (net (code "285") (name "unconnected-(JB2-B15_L19_N-Pad48)") (class "Default")
      (node (ref "JB2") (pin "48") (pinfunction "B15_L19_N_48") (pintype "passive"))
    )
    (net (code "286") (name "unconnected-(JB2-B15_L19_P-Pad46)") (class "Default")
      (node (ref "JB2") (pin "46") (pinfunction "B15_L19_P_46") (pintype "passive"))
    )
    (net (code "287") (name "unconnected-(JB2-B15_L20_N-Pad73)") (class "Default")
      (node (ref "JB2") (pin "73") (pinfunction "B15_L20_N_73") (pintype "passive"))
    )
    (net (code "288") (name "unconnected-(JB2-B15_L20_P-Pad71)") (class "Default")
      (node (ref "JB2") (pin "71") (pinfunction "B15_L20_P_71") (pintype "passive"))
    )
    (net (code "289") (name "unconnected-(JB2-B15_L23_N-Pad44)") (class "Default")
      (node (ref "JB2") (pin "44") (pinfunction "B15_L23_N_44") (pintype "passive"))
    )
    (net (code "290") (name "unconnected-(JB2-B15_L23_P-Pad42)") (class "Default")
      (node (ref "JB2") (pin "42") (pinfunction "B15_L23_P_42") (pintype "passive"))
    )
    (net (code "291") (name "unconnected-(JB2-NC-Pad6)") (class "Default")
      (node (ref "JB2") (pin "6") (pinfunction "NC_6") (pintype "no_connect"))
    )
    (net (code "292") (name "unconnected-(JB2-NC-Pad30)") (class "Default")
      (node (ref "JB2") (pin "30") (pinfunction "NC_30") (pintype "no_connect"))
    )
    (net (code "293") (name "unconnected-(JB3-B13_L1_P-Pad41)") (class "Default")
      (node (ref "JB3") (pin "41") (pinfunction "B13_L1_P_41") (pintype "passive"))
    )
    (net (code "294") (name "unconnected-(JB3-B13_L2_N-Pad51)") (class "Default")
      (node (ref "JB3") (pin "51") (pinfunction "B13_L2_N_51") (pintype "passive"))
    )
    (net (code "295") (name "unconnected-(JB3-B13_L2_P-Pad53)") (class "Default")
      (node (ref "JB3") (pin "53") (pinfunction "B13_L2_P_53") (pintype "passive"))
    )
    (net (code "296") (name "unconnected-(JB3-B13_L10_N-Pad40)") (class "Default")
      (node (ref "JB3") (pin "40") (pinfunction "B13_L10_N_40") (pintype "passive"))
    )
    (net (code "297") (name "unconnected-(JB3-B13_L10_P-Pad38)") (class "Default")
      (node (ref "JB3") (pin "38") (pinfunction "B13_L10_P_38") (pintype "passive"))
    )
    (net (code "298") (name "unconnected-(JB3-B13_L12_CLK_N-Pad59)") (class "Default")
      (node (ref "JB3") (pin "59") (pinfunction "B13_L12_CLK_N_59") (pintype "passive"))
    )
    (net (code "299") (name "unconnected-(JB3-B13_L12_CLK_P-Pad57)") (class "Default")
      (node (ref "JB3") (pin "57") (pinfunction "B13_L12_CLK_P_57") (pintype "passive"))
    )
    (net (code "300") (name "unconnected-(JB3-B13_L13_N-Pad60)") (class "Default")
      (node (ref "JB3") (pin "60") (pinfunction "B13_L13_N_60") (pintype "passive"))
    )
    (net (code "301") (name "unconnected-(JB3-B13_L13_P-Pad58)") (class "Default")
      (node (ref "JB3") (pin "58") (pinfunction "B13_L13_P_58") (pintype "passive"))
    )
    (net (code "302") (name "unconnected-(JB3-B13_L14_N-Pad3)") (class "Default")
      (node (ref "JB3") (pin "3") (pinfunction "B13_L14_N_3") (pintype "passive"))
    )
    (net (code "303") (name "unconnected-(JB3-B13_L14_P-Pad1)") (class "Default")
      (node (ref "JB3") (pin "1") (pinfunction "B13_L14_P_1") (pintype "passive"))
    )
    (net (code "304") (name "unconnected-(JB3-B13_L15_N-Pad44)") (class "Default")
      (node (ref "JB3") (pin "44") (pinfunction "B13_L15_N_44") (pintype "passive"))
    )
    (net (code "305") (name "unconnected-(JB3-B13_L15_P-Pad42)") (class "Default")
      (node (ref "JB3") (pin "42") (pinfunction "B13_L15_P_42") (pintype "passive"))
    )
    (net (code "306") (name "unconnected-(JB3-B13_L17_N-Pad4)") (class "Default")
      (node (ref "JB3") (pin "4") (pinfunction "B13_L17_N_4") (pintype "passive"))
    )
    (net (code "307") (name "unconnected-(JB3-B13_L17_P-Pad2)") (class "Default")
      (node (ref "JB3") (pin "2") (pinfunction "B13_L17_P_2") (pintype "passive"))
    )
    (net (code "308") (name "unconnected-(JB3-B14_L5_N-Pad50)") (class "Default")
      (node (ref "JB3") (pin "50") (pinfunction "B14_L5_N_50") (pintype "passive"))
    )
    (net (code "309") (name "unconnected-(JB3-B14_L5_P-Pad48)") (class "Default")
      (node (ref "JB3") (pin "48") (pinfunction "B14_L5_P_48") (pintype "passive"))
    )
    (net (code "310") (name "unconnected-(JB3-B14_L20_N-Pad54)") (class "Default")
      (node (ref "JB3") (pin "54") (pinfunction "B14_L20_N_54") (pintype "passive"))
    )
    (net (code "311") (name "unconnected-(JB3-B14_L20_P-Pad52)") (class "Default")
      (node (ref "JB3") (pin "52") (pinfunction "B14_L20_P_52") (pintype "passive"))
    )
    (net (code "312") (name "unconnected-(JB3-DC-Pad55)") (class "Default")
      (node (ref "JB3") (pin "55") (pinfunction "DC_55") (pintype "no_connect"))
    )
    (net (code "313") (name "unconnected-(JB3-DC-Pad56)") (class "Default")
      (node (ref "JB3") (pin "56") (pinfunction "DC_56") (pintype "no_connect"))
    )
    (net (code "314") (name "unconnected-(JB3-GND-Pad12)") (class "Default")
      (node (ref "JB3") (pin "12") (pinfunction "GND_12") (pintype "passive"))
    )
    (net (code "315") (name "unconnected-(JB3-MGT_CLK1_CLK_N-Pad32)") (class "Default")
      (node (ref "JB3") (pin "32") (pinfunction "MGT_CLK1_CLK_N_32") (pintype "passive"))
    )
    (net (code "316") (name "unconnected-(JB3-MGT_CLK1_CLK_P-Pad34)") (class "Default")
      (node (ref "JB3") (pin "34") (pinfunction "MGT_CLK1_CLK_P_34") (pintype "passive"))
    )
    (net (code "317") (name "unconnected-(JB3-MGT_RX0_N-Pad7)") (class "Default")
      (node (ref "JB3") (pin "7") (pinfunction "MGT_RX0_N_7") (pintype "passive"))
    )
    (net (code "318") (name "unconnected-(JB3-MGT_RX0_P-Pad9)") (class "Default")
      (node (ref "JB3") (pin "9") (pinfunction "MGT_RX0_P_9") (pintype "passive"))
    )
    (net (code "319") (name "unconnected-(JB3-MGT_RX1_N-Pad13)") (class "Default")
      (node (ref "JB3") (pin "13") (pinfunction "MGT_RX1_N_13") (pintype "passive"))
    )
    (net (code "320") (name "unconnected-(JB3-MGT_RX1_P-Pad15)") (class "Default")
      (node (ref "JB3") (pin "15") (pinfunction "MGT_RX1_P_15") (pintype "passive"))
    )
    (net (code "321") (name "unconnected-(JB3-MGT_RX2_N-Pad19)") (class "Default")
      (node (ref "JB3") (pin "19") (pinfunction "MGT_RX2_N_19") (pintype "passive"))
    )
    (net (code "322") (name "unconnected-(JB3-MGT_RX2_P-Pad21)") (class "Default")
      (node (ref "JB3") (pin "21") (pinfunction "MGT_RX2_P_21") (pintype "passive"))
    )
    (net (code "323") (name "unconnected-(JB3-MGT_RX3_N-Pad25)") (class "Default")
      (node (ref "JB3") (pin "25") (pinfunction "MGT_RX3_N_25") (pintype "passive"))
    )
    (net (code "324") (name "unconnected-(JB3-MGT_RX3_P-Pad27)") (class "Default")
      (node (ref "JB3") (pin "27") (pinfunction "MGT_RX3_P_27") (pintype "passive"))
    )
    (net (code "325") (name "unconnected-(JB3-MGT_TX0_N-Pad8)") (class "Default")
      (node (ref "JB3") (pin "8") (pinfunction "MGT_TX0_N_8") (pintype "passive"))
    )
    (net (code "326") (name "unconnected-(JB3-MGT_TX0_P-Pad10)") (class "Default")
      (node (ref "JB3") (pin "10") (pinfunction "MGT_TX0_P_10") (pintype "passive"))
    )
    (net (code "327") (name "unconnected-(JB3-MGT_TX1_N-Pad14)") (class "Default")
      (node (ref "JB3") (pin "14") (pinfunction "MGT_TX1_N_14") (pintype "passive"))
    )
    (net (code "328") (name "unconnected-(JB3-MGT_TX1_P-Pad16)") (class "Default")
      (node (ref "JB3") (pin "16") (pinfunction "MGT_TX1_P_16") (pintype "passive"))
    )
    (net (code "329") (name "unconnected-(JB3-MGT_TX2_N-Pad20)") (class "Default")
      (node (ref "JB3") (pin "20") (pinfunction "MGT_TX2_N_20") (pintype "passive"))
    )
    (net (code "330") (name "unconnected-(JB3-MGT_TX2_P-Pad22)") (class "Default")
      (node (ref "JB3") (pin "22") (pinfunction "MGT_TX2_P_22") (pintype "passive"))
    )
    (net (code "331") (name "unconnected-(JB3-MGT_TX3_N-Pad26)") (class "Default")
      (node (ref "JB3") (pin "26") (pinfunction "MGT_TX3_N_26") (pintype "passive"))
    )
    (net (code "332") (name "unconnected-(JB3-MGT_TX3_P-Pad28)") (class "Default")
      (node (ref "JB3") (pin "28") (pinfunction "MGT_TX3_P_28") (pintype "passive"))
    )
    (net (code "333") (name "unconnected-(U0821-DC-Pad6)") (class "Default")
      (node (ref "U0821") (pin "6") (pinfunction "DC_6") (pintype "no_connect"))
    )
    (net (code "334") (name "unconnected-(U0821-DC-Pad11)") (class "Default")
      (node (ref "U0821") (pin "11") (pinfunction "DC_11") (pintype "no_connect"))
    )
    (net (code "335") (name "unconnected-(U0821-DC-Pad12)") (class "Default")
      (node (ref "U0821") (pin "12") (pinfunction "DC_12") (pintype "no_connect"))
    )
    (net (code "336") (name "unconnected-(U0911-ACBUS1-Pad25)") (class "Default")
      (node (ref "U0911") (pin "25") (pinfunction "ACBUS1_25") (pintype "tri_state"))
    )
    (net (code "337") (name "unconnected-(U0911-ACBUS2-Pad26)") (class "Default")
      (node (ref "U0911") (pin "26") (pinfunction "ACBUS2_26") (pintype "tri_state"))
    )
    (net (code "338") (name "unconnected-(U0911-ACBUS5-Pad29)") (class "Default")
      (node (ref "U0911") (pin "29") (pinfunction "ACBUS5_29") (pintype "tri_state"))
    )
    (net (code "339") (name "unconnected-(U0911-ACBUS6-Pad30)") (class "Default")
      (node (ref "U0911") (pin "30") (pinfunction "ACBUS6_30") (pintype "tri_state"))
    )
    (net (code "340") (name "unconnected-(U0911-ACBUS7-Pad31)") (class "Default")
      (node (ref "U0911") (pin "31") (pinfunction "ACBUS7_31") (pintype "tri_state"))
    )
    (net (code "341") (name "unconnected-(U0911-ACBUS8-Pad32)") (class "Default")
      (node (ref "U0911") (pin "32") (pinfunction "ACBUS8_32") (pintype "tri_state"))
    )
    (net (code "342") (name "unconnected-(U0911-ACBUS9-Pad33)") (class "Default")
      (node (ref "U0911") (pin "33") (pinfunction "ACBUS9_33") (pintype "tri_state"))
    )
    (net (code "343") (name "unconnected-(U0911-EECLK-Pad44)") (class "Default")
      (node (ref "U0911") (pin "44") (pinfunction "EECLK_44") (pintype "output"))
    )
    (net (code "344") (name "unconnected-(U0911-EECS-Pad45)") (class "Default")
      (node (ref "U0911") (pin "45") (pinfunction "EECS_45") (pintype "bidirectional"))
    )
    (net (code "345") (name "unconnected-(U0911-OSCO-Pad2)") (class "Default")
      (node (ref "U0911") (pin "2") (pinfunction "OSCO_2") (pintype "passive"))
    )
    (net (code "346") (name "unconnected-(U1101-DC-Pad5)") (class "Default")
      (node (ref "U1101") (pin "5") (pinfunction "DC_5") (pintype "no_connect"))
    )
    (net (code "347") (name "unconnected-(U1211-PG-Pad7)") (class "Default")
      (node (ref "U1211") (pin "7") (pinfunction "PG_7") (pintype "open_collector"))
    )
    (net (code "348") (name "unconnected-(U1211-VIN_SW-Pad6)") (class "Default")
      (node (ref "U1211") (pin "6") (pinfunction "VIN_SW_6") (pintype "passive"))
    )
    (net (code "349") (name "unconnected-(X1331-Pad12)") (class "Default")
      (node (ref "X1331") (pin "12") (pinfunction "12_12") (pintype "passive"))
    )
  )
)
